# measure_board.net
KiCad netlist of a schematic drawn in EAGLE
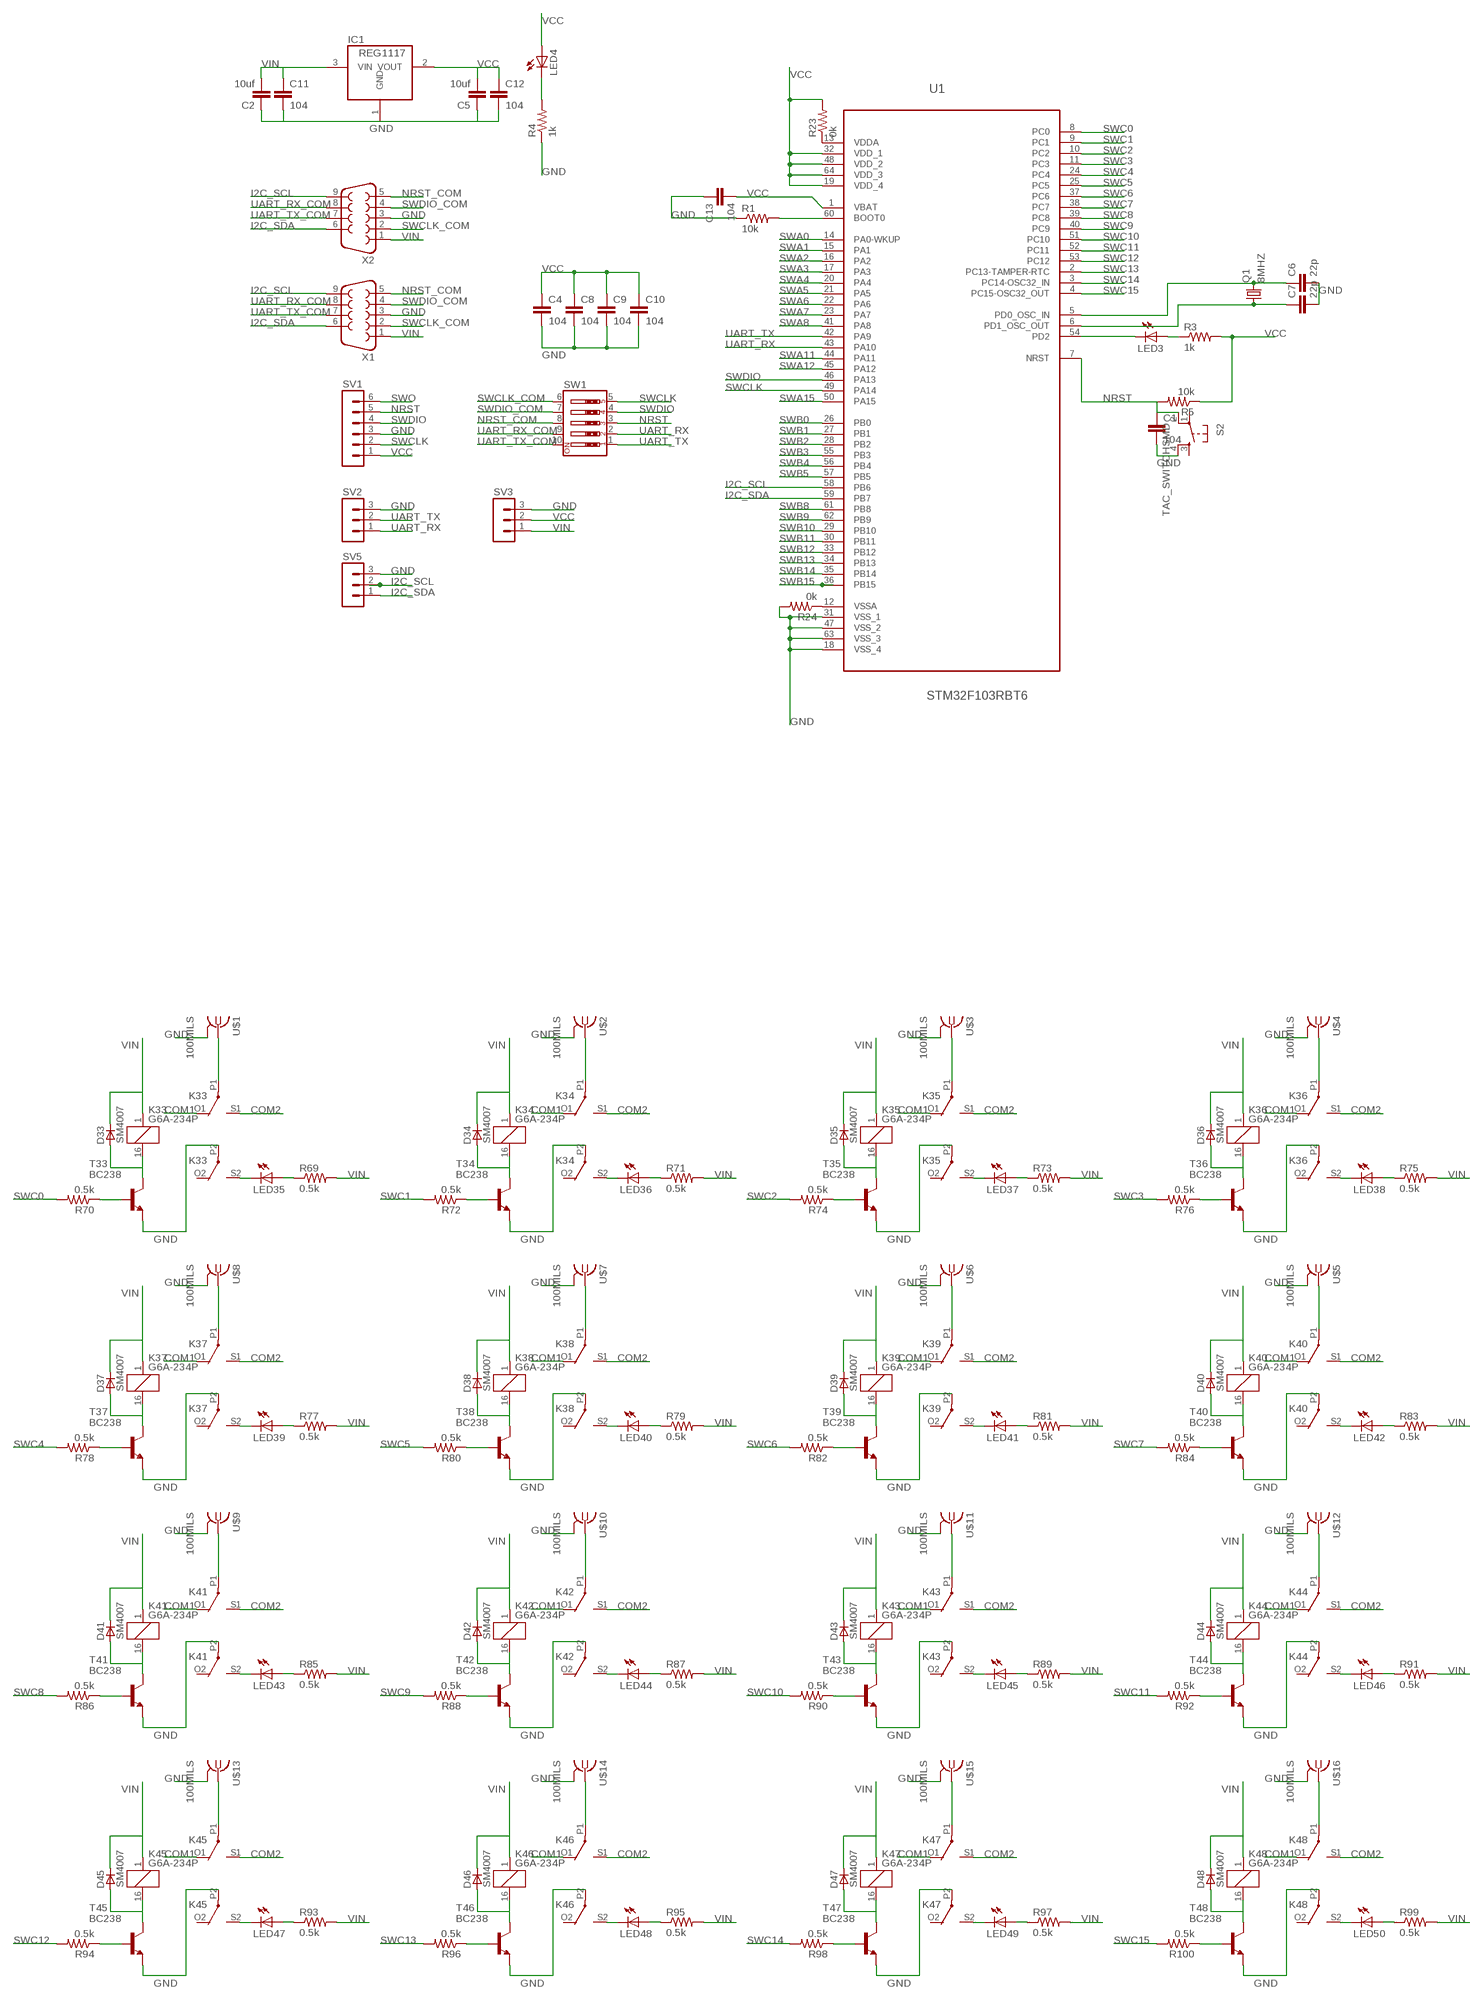
[diagram p0: schematic, sheet 1, part 1 of 2]
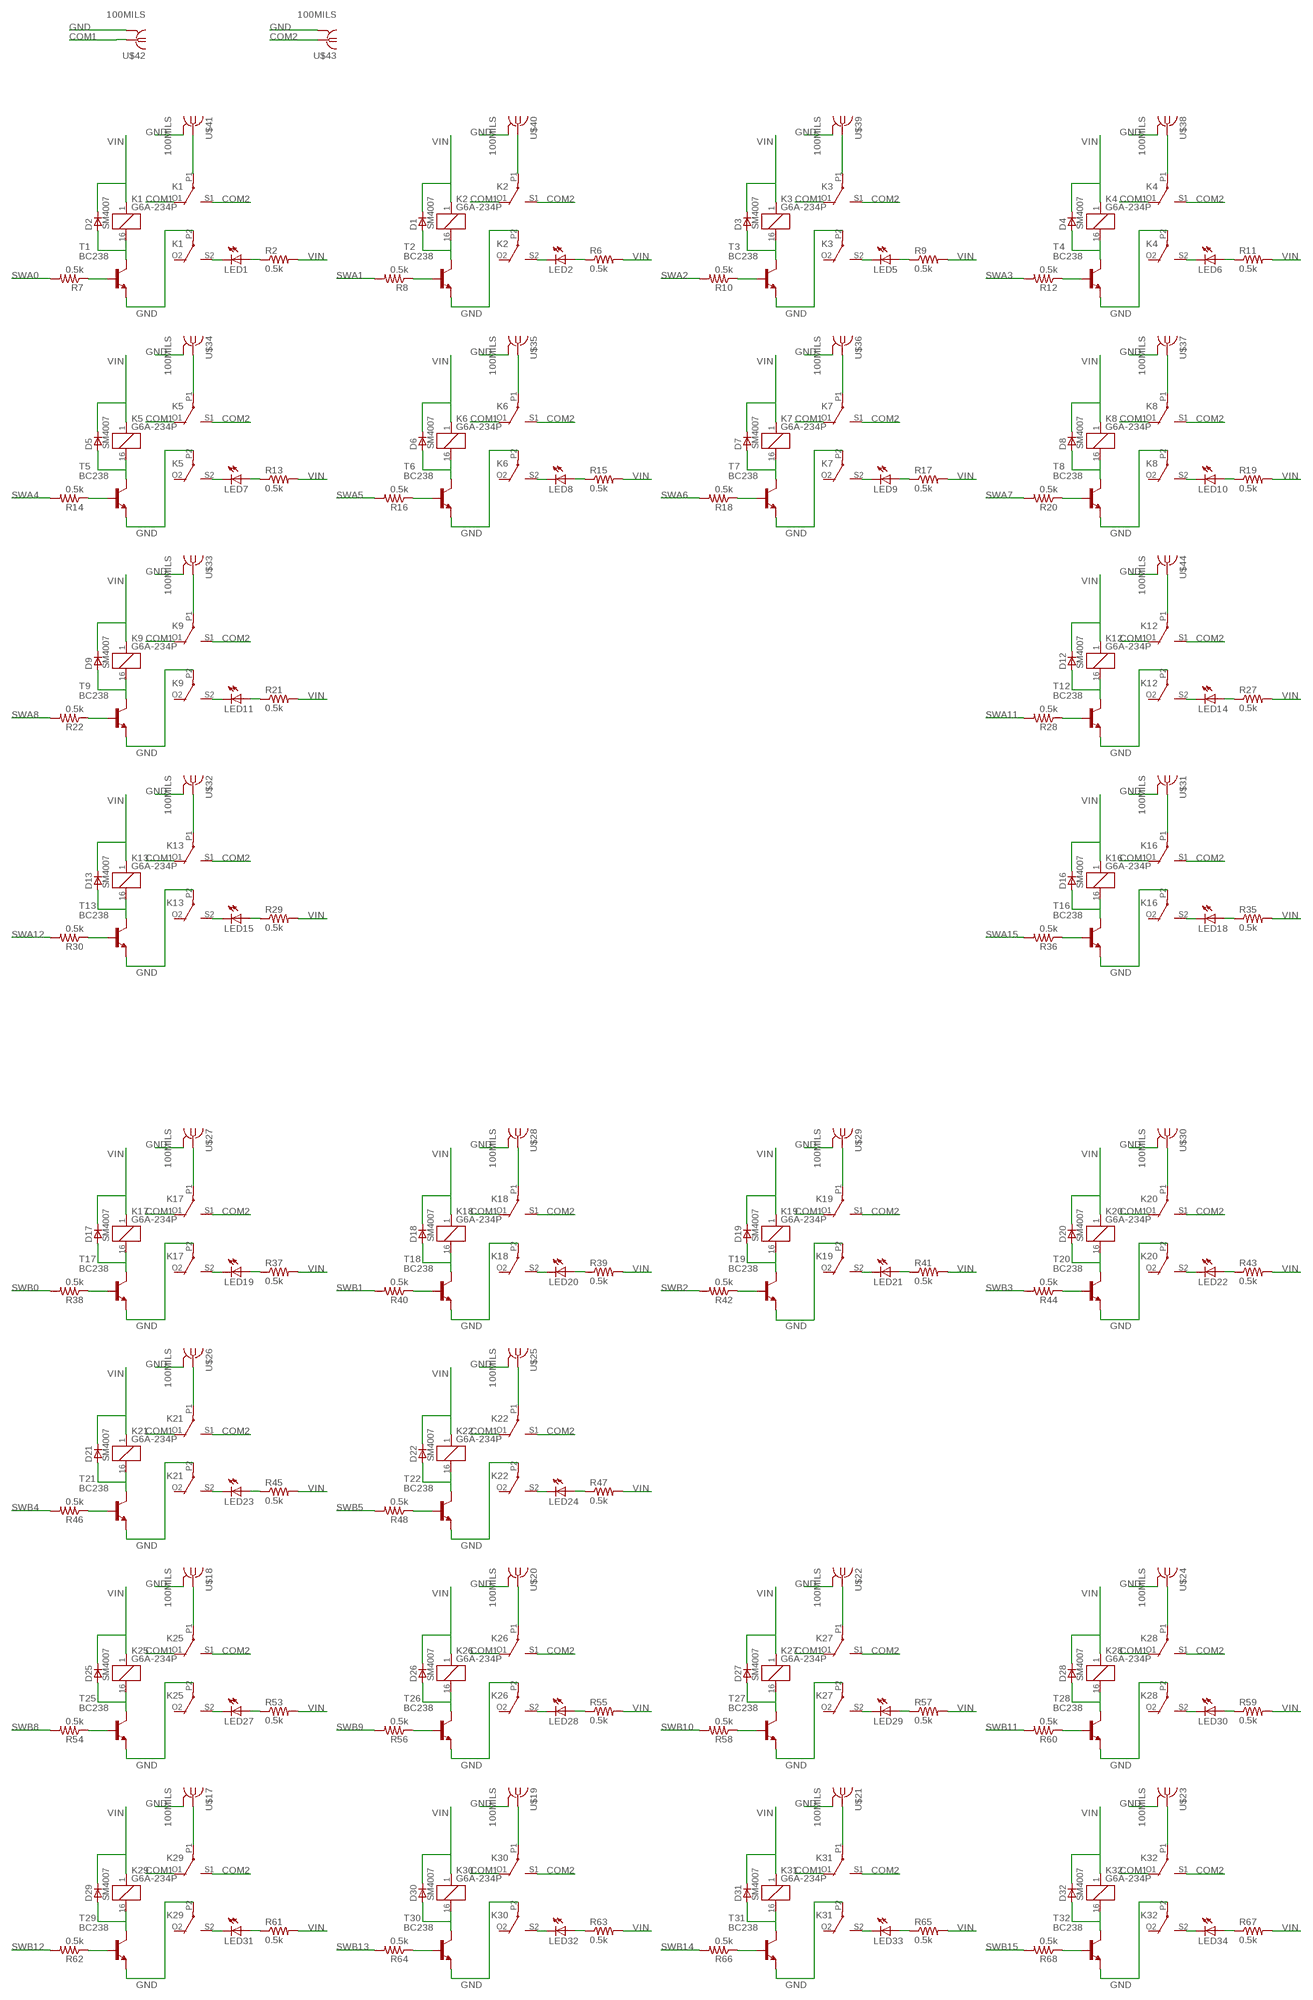
[diagram p1: schematic, sheet 1, part 2 of 2]

(export (version "E")
  (design (tool "Eeschema 10.0.6"))
  (components
    (comp (ref "C1")
      (value "104")
      (footprint "eagle-import:C0805")
      (libsource (lib "eagle-import") (part "resistor_C-EUC0805"))
    )
    (comp (ref "C2")
      (value "10uf")
      (footprint "eagle-import:C1206")
      (libsource (lib "eagle-import") (part "C-EUC1206"))
    )
    (comp (ref "C4")
      (value "104")
      (footprint "eagle-import:C0805")
      (libsource (lib "eagle-import") (part "resistor_C-EUC0805"))
    )
    (comp (ref "C5")
      (value "10uf")
      (footprint "eagle-import:C1206")
      (libsource (lib "eagle-import") (part "C-EUC1206"))
    )
    (comp (ref "C6")
      (value "22p")
      (footprint "eagle-import:C0805")
      (libsource (lib "eagle-import") (part "resistor_C-EUC0805"))
    )
    (comp (ref "C7")
      (value "22p")
      (footprint "eagle-import:C0805")
      (libsource (lib "eagle-import") (part "resistor_C-EUC0805"))
    )
    (comp (ref "C8")
      (value "104")
      (footprint "eagle-import:C0805")
      (libsource (lib "eagle-import") (part "resistor_C-EUC0805"))
    )
    (comp (ref "C9")
      (value "104")
      (footprint "eagle-import:C0805")
      (libsource (lib "eagle-import") (part "resistor_C-EUC0805"))
    )
    (comp (ref "C10")
      (value "104")
      (footprint "eagle-import:C0805")
      (libsource (lib "eagle-import") (part "resistor_C-EUC0805"))
    )
    (comp (ref "C11")
      (value "104")
      (footprint "eagle-import:C0805")
      (libsource (lib "eagle-import") (part "resistor_C-EUC0805"))
    )
    (comp (ref "C12")
      (value "104")
      (footprint "eagle-import:C0805")
      (libsource (lib "eagle-import") (part "resistor_C-EUC0805"))
    )
    (comp (ref "C13")
      (value "104")
      (footprint "eagle-import:C0805")
      (libsource (lib "eagle-import") (part "resistor_C-EUC0805"))
    )
    (comp (ref "D1")
      (value "SM4007")
      (footprint "eagle-import:MELF-MLL41_DO213AB")
      (libsource (lib "eagle-import") (part "SM4007"))
    )
    (comp (ref "D2")
      (value "SM4007")
      (footprint "eagle-import:MELF-MLL41_DO213AB")
      (libsource (lib "eagle-import") (part "SM4007"))
    )
    (comp (ref "D3")
      (value "SM4007")
      (footprint "eagle-import:MELF-MLL41_DO213AB")
      (libsource (lib "eagle-import") (part "SM4007"))
    )
    (comp (ref "D4")
      (value "SM4007")
      (footprint "eagle-import:MELF-MLL41_DO213AB")
      (libsource (lib "eagle-import") (part "SM4007"))
    )
    (comp (ref "D5")
      (value "SM4007")
      (footprint "eagle-import:MELF-MLL41_DO213AB")
      (libsource (lib "eagle-import") (part "SM4007"))
    )
    (comp (ref "D6")
      (value "SM4007")
      (footprint "eagle-import:MELF-MLL41_DO213AB")
      (libsource (lib "eagle-import") (part "SM4007"))
    )
    (comp (ref "D7")
      (value "SM4007")
      (footprint "eagle-import:MELF-MLL41_DO213AB")
      (libsource (lib "eagle-import") (part "SM4007"))
    )
    (comp (ref "D8")
      (value "SM4007")
      (footprint "eagle-import:MELF-MLL41_DO213AB")
      (libsource (lib "eagle-import") (part "SM4007"))
    )
    (comp (ref "D9")
      (value "SM4007")
      (footprint "eagle-import:MELF-MLL41_DO213AB")
      (libsource (lib "eagle-import") (part "SM4007"))
    )
    (comp (ref "D12")
      (value "SM4007")
      (footprint "eagle-import:MELF-MLL41_DO213AB")
      (libsource (lib "eagle-import") (part "SM4007"))
    )
    (comp (ref "D13")
      (value "SM4007")
      (footprint "eagle-import:MELF-MLL41_DO213AB")
      (libsource (lib "eagle-import") (part "SM4007"))
    )
    (comp (ref "D16")
      (value "SM4007")
      (footprint "eagle-import:MELF-MLL41_DO213AB")
      (libsource (lib "eagle-import") (part "SM4007"))
    )
    (comp (ref "D17")
      (value "SM4007")
      (footprint "eagle-import:MELF-MLL41_DO213AB")
      (libsource (lib "eagle-import") (part "SM4007"))
    )
    (comp (ref "D18")
      (value "SM4007")
      (footprint "eagle-import:MELF-MLL41_DO213AB")
      (libsource (lib "eagle-import") (part "SM4007"))
    )
    (comp (ref "D19")
      (value "SM4007")
      (footprint "eagle-import:MELF-MLL41_DO213AB")
      (libsource (lib "eagle-import") (part "SM4007"))
    )
    (comp (ref "D20")
      (value "SM4007")
      (footprint "eagle-import:MELF-MLL41_DO213AB")
      (libsource (lib "eagle-import") (part "SM4007"))
    )
    (comp (ref "D21")
      (value "SM4007")
      (footprint "eagle-import:MELF-MLL41_DO213AB")
      (libsource (lib "eagle-import") (part "SM4007"))
    )
    (comp (ref "D22")
      (value "SM4007")
      (footprint "eagle-import:MELF-MLL41_DO213AB")
      (libsource (lib "eagle-import") (part "SM4007"))
    )
    (comp (ref "D25")
      (value "SM4007")
      (footprint "eagle-import:MELF-MLL41_DO213AB")
      (libsource (lib "eagle-import") (part "SM4007"))
    )
    (comp (ref "D26")
      (value "SM4007")
      (footprint "eagle-import:MELF-MLL41_DO213AB")
      (libsource (lib "eagle-import") (part "SM4007"))
    )
    (comp (ref "D27")
      (value "SM4007")
      (footprint "eagle-import:MELF-MLL41_DO213AB")
      (libsource (lib "eagle-import") (part "SM4007"))
    )
    (comp (ref "D28")
      (value "SM4007")
      (footprint "eagle-import:MELF-MLL41_DO213AB")
      (libsource (lib "eagle-import") (part "SM4007"))
    )
    (comp (ref "D29")
      (value "SM4007")
      (footprint "eagle-import:MELF-MLL41_DO213AB")
      (libsource (lib "eagle-import") (part "SM4007"))
    )
    (comp (ref "D30")
      (value "SM4007")
      (footprint "eagle-import:MELF-MLL41_DO213AB")
      (libsource (lib "eagle-import") (part "SM4007"))
    )
    (comp (ref "D31")
      (value "SM4007")
      (footprint "eagle-import:MELF-MLL41_DO213AB")
      (libsource (lib "eagle-import") (part "SM4007"))
    )
    (comp (ref "D32")
      (value "SM4007")
      (footprint "eagle-import:MELF-MLL41_DO213AB")
      (libsource (lib "eagle-import") (part "SM4007"))
    )
    (comp (ref "D33")
      (value "SM4007")
      (footprint "eagle-import:MELF-MLL41_DO213AB")
      (libsource (lib "eagle-import") (part "SM4007"))
    )
    (comp (ref "D34")
      (value "SM4007")
      (footprint "eagle-import:MELF-MLL41_DO213AB")
      (libsource (lib "eagle-import") (part "SM4007"))
    )
    (comp (ref "D35")
      (value "SM4007")
      (footprint "eagle-import:MELF-MLL41_DO213AB")
      (libsource (lib "eagle-import") (part "SM4007"))
    )
    (comp (ref "D36")
      (value "SM4007")
      (footprint "eagle-import:MELF-MLL41_DO213AB")
      (libsource (lib "eagle-import") (part "SM4007"))
    )
    (comp (ref "D37")
      (value "SM4007")
      (footprint "eagle-import:MELF-MLL41_DO213AB")
      (libsource (lib "eagle-import") (part "SM4007"))
    )
    (comp (ref "D38")
      (value "SM4007")
      (footprint "eagle-import:MELF-MLL41_DO213AB")
      (libsource (lib "eagle-import") (part "SM4007"))
    )
    (comp (ref "D39")
      (value "SM4007")
      (footprint "eagle-import:MELF-MLL41_DO213AB")
      (libsource (lib "eagle-import") (part "SM4007"))
    )
    (comp (ref "D40")
      (value "SM4007")
      (footprint "eagle-import:MELF-MLL41_DO213AB")
      (libsource (lib "eagle-import") (part "SM4007"))
    )
    (comp (ref "D41")
      (value "SM4007")
      (footprint "eagle-import:MELF-MLL41_DO213AB")
      (libsource (lib "eagle-import") (part "SM4007"))
    )
    (comp (ref "D42")
      (value "SM4007")
      (footprint "eagle-import:MELF-MLL41_DO213AB")
      (libsource (lib "eagle-import") (part "SM4007"))
    )
    (comp (ref "D43")
      (value "SM4007")
      (footprint "eagle-import:MELF-MLL41_DO213AB")
      (libsource (lib "eagle-import") (part "SM4007"))
    )
    (comp (ref "D44")
      (value "SM4007")
      (footprint "eagle-import:MELF-MLL41_DO213AB")
      (libsource (lib "eagle-import") (part "SM4007"))
    )
    (comp (ref "D45")
      (value "SM4007")
      (footprint "eagle-import:MELF-MLL41_DO213AB")
      (libsource (lib "eagle-import") (part "SM4007"))
    )
    (comp (ref "D46")
      (value "SM4007")
      (footprint "eagle-import:MELF-MLL41_DO213AB")
      (libsource (lib "eagle-import") (part "SM4007"))
    )
    (comp (ref "D47")
      (value "SM4007")
      (footprint "eagle-import:MELF-MLL41_DO213AB")
      (libsource (lib "eagle-import") (part "SM4007"))
    )
    (comp (ref "D48")
      (value "SM4007")
      (footprint "eagle-import:MELF-MLL41_DO213AB")
      (libsource (lib "eagle-import") (part "SM4007"))
    )
    (comp (ref "IC1")
      (value "REG1117")
      (footprint "eagle-import:SOT223")
      (libsource (lib "eagle-import") (part "REG1117"))
    )
    (comp (ref "K1")
      (value "G6A-234P")
      (footprint "eagle-import:G6A-234P")
      (libsource (lib "eagle-import") (part "G6A-234P"))
    )
    (comp (ref "K2")
      (value "G6A-234P")
      (footprint "eagle-import:G6A-234P")
      (libsource (lib "eagle-import") (part "G6A-234P"))
    )
    (comp (ref "K3")
      (value "G6A-234P")
      (footprint "eagle-import:G6A-234P")
      (libsource (lib "eagle-import") (part "G6A-234P"))
    )
    (comp (ref "K4")
      (value "G6A-234P")
      (footprint "eagle-import:G6A-234P")
      (libsource (lib "eagle-import") (part "G6A-234P"))
    )
    (comp (ref "K5")
      (value "G6A-234P")
      (footprint "eagle-import:G6A-234P")
      (libsource (lib "eagle-import") (part "G6A-234P"))
    )
    (comp (ref "K6")
      (value "G6A-234P")
      (footprint "eagle-import:G6A-234P")
      (libsource (lib "eagle-import") (part "G6A-234P"))
    )
    (comp (ref "K7")
      (value "G6A-234P")
      (footprint "eagle-import:G6A-234P")
      (libsource (lib "eagle-import") (part "G6A-234P"))
    )
    (comp (ref "K8")
      (value "G6A-234P")
      (footprint "eagle-import:G6A-234P")
      (libsource (lib "eagle-import") (part "G6A-234P"))
    )
    (comp (ref "K9")
      (value "G6A-234P")
      (footprint "eagle-import:G6A-234P")
      (libsource (lib "eagle-import") (part "G6A-234P"))
    )
    (comp (ref "K12")
      (value "G6A-234P")
      (footprint "eagle-import:G6A-234P")
      (libsource (lib "eagle-import") (part "G6A-234P"))
    )
    (comp (ref "K13")
      (value "G6A-234P")
      (footprint "eagle-import:G6A-234P")
      (libsource (lib "eagle-import") (part "G6A-234P"))
    )
    (comp (ref "K16")
      (value "G6A-234P")
      (footprint "eagle-import:G6A-234P")
      (libsource (lib "eagle-import") (part "G6A-234P"))
    )
    (comp (ref "K17")
      (value "G6A-234P")
      (footprint "eagle-import:G6A-234P")
      (libsource (lib "eagle-import") (part "G6A-234P"))
    )
    (comp (ref "K18")
      (value "G6A-234P")
      (footprint "eagle-import:G6A-234P")
      (libsource (lib "eagle-import") (part "G6A-234P"))
    )
    (comp (ref "K19")
      (value "G6A-234P")
      (footprint "eagle-import:G6A-234P")
      (libsource (lib "eagle-import") (part "G6A-234P"))
    )
    (comp (ref "K20")
      (value "G6A-234P")
      (footprint "eagle-import:G6A-234P")
      (libsource (lib "eagle-import") (part "G6A-234P"))
    )
    (comp (ref "K21")
      (value "G6A-234P")
      (footprint "eagle-import:G6A-234P")
      (libsource (lib "eagle-import") (part "G6A-234P"))
    )
    (comp (ref "K22")
      (value "G6A-234P")
      (footprint "eagle-import:G6A-234P")
      (libsource (lib "eagle-import") (part "G6A-234P"))
    )
    (comp (ref "K25")
      (value "G6A-234P")
      (footprint "eagle-import:G6A-234P")
      (libsource (lib "eagle-import") (part "G6A-234P"))
    )
    (comp (ref "K26")
      (value "G6A-234P")
      (footprint "eagle-import:G6A-234P")
      (libsource (lib "eagle-import") (part "G6A-234P"))
    )
    (comp (ref "K27")
      (value "G6A-234P")
      (footprint "eagle-import:G6A-234P")
      (libsource (lib "eagle-import") (part "G6A-234P"))
    )
    (comp (ref "K28")
      (value "G6A-234P")
      (footprint "eagle-import:G6A-234P")
      (libsource (lib "eagle-import") (part "G6A-234P"))
    )
    (comp (ref "K29")
      (value "G6A-234P")
      (footprint "eagle-import:G6A-234P")
      (libsource (lib "eagle-import") (part "G6A-234P"))
    )
    (comp (ref "K30")
      (value "G6A-234P")
      (footprint "eagle-import:G6A-234P")
      (libsource (lib "eagle-import") (part "G6A-234P"))
    )
    (comp (ref "K31")
      (value "G6A-234P")
      (footprint "eagle-import:G6A-234P")
      (libsource (lib "eagle-import") (part "G6A-234P"))
    )
    (comp (ref "K32")
      (value "G6A-234P")
      (footprint "eagle-import:G6A-234P")
      (libsource (lib "eagle-import") (part "G6A-234P"))
    )
    (comp (ref "K33")
      (value "G6A-234P")
      (footprint "eagle-import:G6A-234P")
      (libsource (lib "eagle-import") (part "G6A-234P"))
    )
    (comp (ref "K34")
      (value "G6A-234P")
      (footprint "eagle-import:G6A-234P")
      (libsource (lib "eagle-import") (part "G6A-234P"))
    )
    (comp (ref "K35")
      (value "G6A-234P")
      (footprint "eagle-import:G6A-234P")
      (libsource (lib "eagle-import") (part "G6A-234P"))
    )
    (comp (ref "K36")
      (value "G6A-234P")
      (footprint "eagle-import:G6A-234P")
      (libsource (lib "eagle-import") (part "G6A-234P"))
    )
    (comp (ref "K37")
      (value "G6A-234P")
      (footprint "eagle-import:G6A-234P")
      (libsource (lib "eagle-import") (part "G6A-234P"))
    )
    (comp (ref "K38")
      (value "G6A-234P")
      (footprint "eagle-import:G6A-234P")
      (libsource (lib "eagle-import") (part "G6A-234P"))
    )
    (comp (ref "K39")
      (value "G6A-234P")
      (footprint "eagle-import:G6A-234P")
      (libsource (lib "eagle-import") (part "G6A-234P"))
    )
    (comp (ref "K40")
      (value "G6A-234P")
      (footprint "eagle-import:G6A-234P")
      (libsource (lib "eagle-import") (part "G6A-234P"))
    )
    (comp (ref "K41")
      (value "G6A-234P")
      (footprint "eagle-import:G6A-234P")
      (libsource (lib "eagle-import") (part "G6A-234P"))
    )
    (comp (ref "K42")
      (value "G6A-234P")
      (footprint "eagle-import:G6A-234P")
      (libsource (lib "eagle-import") (part "G6A-234P"))
    )
    (comp (ref "K43")
      (value "G6A-234P")
      (footprint "eagle-import:G6A-234P")
      (libsource (lib "eagle-import") (part "G6A-234P"))
    )
    (comp (ref "K44")
      (value "G6A-234P")
      (footprint "eagle-import:G6A-234P")
      (libsource (lib "eagle-import") (part "G6A-234P"))
    )
    (comp (ref "K45")
      (value "G6A-234P")
      (footprint "eagle-import:G6A-234P")
      (libsource (lib "eagle-import") (part "G6A-234P"))
    )
    (comp (ref "K46")
      (value "G6A-234P")
      (footprint "eagle-import:G6A-234P")
      (libsource (lib "eagle-import") (part "G6A-234P"))
    )
    (comp (ref "K47")
      (value "G6A-234P")
      (footprint "eagle-import:G6A-234P")
      (libsource (lib "eagle-import") (part "G6A-234P"))
    )
    (comp (ref "K48")
      (value "G6A-234P")
      (footprint "eagle-import:G6A-234P")
      (libsource (lib "eagle-import") (part "G6A-234P"))
    )
    (comp (ref "LED1")
      (value "LED3MM")
      (footprint "eagle-import:LED3MM")
      (libsource (lib "eagle-import") (part "LED3MM"))
    )
    (comp (ref "LED2")
      (value "LED3MM")
      (footprint "eagle-import:LED3MM")
      (libsource (lib "eagle-import") (part "LED3MM"))
    )
    (comp (ref "LED3")
      (value "LEDSML0805")
      (footprint "eagle-import:SML0805")
      (libsource (lib "eagle-import") (part "LEDSML0805"))
    )
    (comp (ref "LED4")
      (value "LEDSML0805")
      (footprint "eagle-import:SML0805")
      (libsource (lib "eagle-import") (part "LEDSML0805"))
    )
    (comp (ref "LED5")
      (value "LED3MM")
      (footprint "eagle-import:LED3MM")
      (libsource (lib "eagle-import") (part "LED3MM"))
    )
    (comp (ref "LED6")
      (value "LED3MM")
      (footprint "eagle-import:LED3MM")
      (libsource (lib "eagle-import") (part "LED3MM"))
    )
    (comp (ref "LED7")
      (value "LED3MM")
      (footprint "eagle-import:LED3MM")
      (libsource (lib "eagle-import") (part "LED3MM"))
    )
    (comp (ref "LED8")
      (value "LED3MM")
      (footprint "eagle-import:LED3MM")
      (libsource (lib "eagle-import") (part "LED3MM"))
    )
    (comp (ref "LED9")
      (value "LED3MM")
      (footprint "eagle-import:LED3MM")
      (libsource (lib "eagle-import") (part "LED3MM"))
    )
    (comp (ref "LED10")
      (value "LED3MM")
      (footprint "eagle-import:LED3MM")
      (libsource (lib "eagle-import") (part "LED3MM"))
    )
    (comp (ref "LED11")
      (value "LED3MM")
      (footprint "eagle-import:LED3MM")
      (libsource (lib "eagle-import") (part "LED3MM"))
    )
    (comp (ref "LED14")
      (value "LED3MM")
      (footprint "eagle-import:LED3MM")
      (libsource (lib "eagle-import") (part "LED3MM"))
    )
    (comp (ref "LED15")
      (value "LED3MM")
      (footprint "eagle-import:LED3MM")
      (libsource (lib "eagle-import") (part "LED3MM"))
    )
    (comp (ref "LED18")
      (value "LED3MM")
      (footprint "eagle-import:LED3MM")
      (libsource (lib "eagle-import") (part "LED3MM"))
    )
    (comp (ref "LED19")
      (value "LED3MM")
      (footprint "eagle-import:LED3MM")
      (libsource (lib "eagle-import") (part "LED3MM"))
    )
    (comp (ref "LED20")
      (value "LED3MM")
      (footprint "eagle-import:LED3MM")
      (libsource (lib "eagle-import") (part "LED3MM"))
    )
    (comp (ref "LED21")
      (value "LED3MM")
      (footprint "eagle-import:LED3MM")
      (libsource (lib "eagle-import") (part "LED3MM"))
    )
    (comp (ref "LED22")
      (value "LED3MM")
      (footprint "eagle-import:LED3MM")
      (libsource (lib "eagle-import") (part "LED3MM"))
    )
    (comp (ref "LED23")
      (value "LED3MM")
      (footprint "eagle-import:LED3MM")
      (libsource (lib "eagle-import") (part "LED3MM"))
    )
    (comp (ref "LED24")
      (value "LED3MM")
      (footprint "eagle-import:LED3MM")
      (libsource (lib "eagle-import") (part "LED3MM"))
    )
    (comp (ref "LED27")
      (value "LED3MM")
      (footprint "eagle-import:LED3MM")
      (libsource (lib "eagle-import") (part "LED3MM"))
    )
    (comp (ref "LED28")
      (value "LED3MM")
      (footprint "eagle-import:LED3MM")
      (libsource (lib "eagle-import") (part "LED3MM"))
    )
    (comp (ref "LED29")
      (value "LED3MM")
      (footprint "eagle-import:LED3MM")
      (libsource (lib "eagle-import") (part "LED3MM"))
    )
    (comp (ref "LED30")
      (value "LED3MM")
      (footprint "eagle-import:LED3MM")
      (libsource (lib "eagle-import") (part "LED3MM"))
    )
    (comp (ref "LED31")
      (value "LED3MM")
      (footprint "eagle-import:LED3MM")
      (libsource (lib "eagle-import") (part "LED3MM"))
    )
    (comp (ref "LED32")
      (value "LED3MM")
      (footprint "eagle-import:LED3MM")
      (libsource (lib "eagle-import") (part "LED3MM"))
    )
    (comp (ref "LED33")
      (value "LED3MM")
      (footprint "eagle-import:LED3MM")
      (libsource (lib "eagle-import") (part "LED3MM"))
    )
    (comp (ref "LED34")
      (value "LED3MM")
      (footprint "eagle-import:LED3MM")
      (libsource (lib "eagle-import") (part "LED3MM"))
    )
    (comp (ref "LED35")
      (value "LED3MM")
      (footprint "eagle-import:LED3MM")
      (libsource (lib "eagle-import") (part "LED3MM"))
    )
    (comp (ref "LED36")
      (value "LED3MM")
      (footprint "eagle-import:LED3MM")
      (libsource (lib "eagle-import") (part "LED3MM"))
    )
    (comp (ref "LED37")
      (value "LED3MM")
      (footprint "eagle-import:LED3MM")
      (libsource (lib "eagle-import") (part "LED3MM"))
    )
    (comp (ref "LED38")
      (value "LED3MM")
      (footprint "eagle-import:LED3MM")
      (libsource (lib "eagle-import") (part "LED3MM"))
    )
    (comp (ref "LED39")
      (value "LED3MM")
      (footprint "eagle-import:LED3MM")
      (libsource (lib "eagle-import") (part "LED3MM"))
    )
    (comp (ref "LED40")
      (value "LED3MM")
      (footprint "eagle-import:LED3MM")
      (libsource (lib "eagle-import") (part "LED3MM"))
    )
    (comp (ref "LED41")
      (value "LED3MM")
      (footprint "eagle-import:LED3MM")
      (libsource (lib "eagle-import") (part "LED3MM"))
    )
    (comp (ref "LED42")
      (value "LED3MM")
      (footprint "eagle-import:LED3MM")
      (libsource (lib "eagle-import") (part "LED3MM"))
    )
    (comp (ref "LED43")
      (value "LED3MM")
      (footprint "eagle-import:LED3MM")
      (libsource (lib "eagle-import") (part "LED3MM"))
    )
    (comp (ref "LED44")
      (value "LED3MM")
      (footprint "eagle-import:LED3MM")
      (libsource (lib "eagle-import") (part "LED3MM"))
    )
    (comp (ref "LED45")
      (value "LED3MM")
      (footprint "eagle-import:LED3MM")
      (libsource (lib "eagle-import") (part "LED3MM"))
    )
    (comp (ref "LED46")
      (value "LED3MM")
      (footprint "eagle-import:LED3MM")
      (libsource (lib "eagle-import") (part "LED3MM"))
    )
    (comp (ref "LED47")
      (value "LED3MM")
      (footprint "eagle-import:LED3MM")
      (libsource (lib "eagle-import") (part "LED3MM"))
    )
    (comp (ref "LED48")
      (value "LED3MM")
      (footprint "eagle-import:LED3MM")
      (libsource (lib "eagle-import") (part "LED3MM"))
    )
    (comp (ref "LED49")
      (value "LED3MM")
      (footprint "eagle-import:LED3MM")
      (libsource (lib "eagle-import") (part "LED3MM"))
    )
    (comp (ref "LED50")
      (value "LED3MM")
      (footprint "eagle-import:LED3MM")
      (libsource (lib "eagle-import") (part "LED3MM"))
    )
    (comp (ref "Q1")
      (value "8MHZ")
      (footprint "eagle-import:HC49U70")
      (libsource (lib "eagle-import") (part "CRYSTALHC49U70"))
    )
    (comp (ref "R1")
      (value "10k")
      (footprint "eagle-import:M0805")
      (libsource (lib "eagle-import") (part "R-US_M0805"))
    )
    (comp (ref "R2")
      (value "0.5k")
      (footprint "eagle-import:M0805")
      (libsource (lib "eagle-import") (part "R-US_M0805"))
    )
    (comp (ref "R3")
      (value "1k")
      (footprint "eagle-import:M0805")
      (libsource (lib "eagle-import") (part "R-US_M0805"))
    )
    (comp (ref "R4")
      (value "1k")
      (footprint "eagle-import:M0805")
      (libsource (lib "eagle-import") (part "R-US_M0805"))
    )
    (comp (ref "R5")
      (value "10k")
      (footprint "eagle-import:M0805")
      (libsource (lib "eagle-import") (part "R-US_M0805"))
    )
    (comp (ref "R6")
      (value "0.5k")
      (footprint "eagle-import:M0805")
      (libsource (lib "eagle-import") (part "R-US_M0805"))
    )
    (comp (ref "R7")
      (value "0.5k")
      (footprint "eagle-import:M0805")
      (libsource (lib "eagle-import") (part "R-US_M0805"))
    )
    (comp (ref "R8")
      (value "0.5k")
      (footprint "eagle-import:M0805")
      (libsource (lib "eagle-import") (part "R-US_M0805"))
    )
    (comp (ref "R9")
      (value "0.5k")
      (footprint "eagle-import:M0805")
      (libsource (lib "eagle-import") (part "R-US_M0805"))
    )
    (comp (ref "R10")
      (value "0.5k")
      (footprint "eagle-import:M0805")
      (libsource (lib "eagle-import") (part "R-US_M0805"))
    )
    (comp (ref "R11")
      (value "0.5k")
      (footprint "eagle-import:M0805")
      (libsource (lib "eagle-import") (part "R-US_M0805"))
    )
    (comp (ref "R12")
      (value "0.5k")
      (footprint "eagle-import:M0805")
      (libsource (lib "eagle-import") (part "R-US_M0805"))
    )
    (comp (ref "R13")
      (value "0.5k")
      (footprint "eagle-import:M0805")
      (libsource (lib "eagle-import") (part "R-US_M0805"))
    )
    (comp (ref "R14")
      (value "0.5k")
      (footprint "eagle-import:M0805")
      (libsource (lib "eagle-import") (part "R-US_M0805"))
    )
    (comp (ref "R15")
      (value "0.5k")
      (footprint "eagle-import:M0805")
      (libsource (lib "eagle-import") (part "R-US_M0805"))
    )
    (comp (ref "R16")
      (value "0.5k")
      (footprint "eagle-import:M0805")
      (libsource (lib "eagle-import") (part "R-US_M0805"))
    )
    (comp (ref "R17")
      (value "0.5k")
      (footprint "eagle-import:M0805")
      (libsource (lib "eagle-import") (part "R-US_M0805"))
    )
    (comp (ref "R18")
      (value "0.5k")
      (footprint "eagle-import:M0805")
      (libsource (lib "eagle-import") (part "R-US_M0805"))
    )
    (comp (ref "R19")
      (value "0.5k")
      (footprint "eagle-import:M0805")
      (libsource (lib "eagle-import") (part "R-US_M0805"))
    )
    (comp (ref "R20")
      (value "0.5k")
      (footprint "eagle-import:M0805")
      (libsource (lib "eagle-import") (part "R-US_M0805"))
    )
    (comp (ref "R21")
      (value "0.5k")
      (footprint "eagle-import:M0805")
      (libsource (lib "eagle-import") (part "R-US_M0805"))
    )
    (comp (ref "R22")
      (value "0.5k")
      (footprint "eagle-import:M0805")
      (libsource (lib "eagle-import") (part "R-US_M0805"))
    )
    (comp (ref "R23")
      (value "0k")
      (footprint "eagle-import:M0805")
      (libsource (lib "eagle-import") (part "R-US_M0805"))
    )
    (comp (ref "R24")
      (value "0k")
      (footprint "eagle-import:M0805")
      (libsource (lib "eagle-import") (part "R-US_M0805"))
    )
    (comp (ref "R27")
      (value "0.5k")
      (footprint "eagle-import:M0805")
      (libsource (lib "eagle-import") (part "R-US_M0805"))
    )
    (comp (ref "R28")
      (value "0.5k")
      (footprint "eagle-import:M0805")
      (libsource (lib "eagle-import") (part "R-US_M0805"))
    )
    (comp (ref "R29")
      (value "0.5k")
      (footprint "eagle-import:M0805")
      (libsource (lib "eagle-import") (part "R-US_M0805"))
    )
    (comp (ref "R30")
      (value "0.5k")
      (footprint "eagle-import:M0805")
      (libsource (lib "eagle-import") (part "R-US_M0805"))
    )
    (comp (ref "R35")
      (value "0.5k")
      (footprint "eagle-import:M0805")
      (libsource (lib "eagle-import") (part "R-US_M0805"))
    )
    (comp (ref "R36")
      (value "0.5k")
      (footprint "eagle-import:M0805")
      (libsource (lib "eagle-import") (part "R-US_M0805"))
    )
    (comp (ref "R37")
      (value "0.5k")
      (footprint "eagle-import:M0805")
      (libsource (lib "eagle-import") (part "R-US_M0805"))
    )
    (comp (ref "R38")
      (value "0.5k")
      (footprint "eagle-import:M0805")
      (libsource (lib "eagle-import") (part "R-US_M0805"))
    )
    (comp (ref "R39")
      (value "0.5k")
      (footprint "eagle-import:M0805")
      (libsource (lib "eagle-import") (part "R-US_M0805"))
    )
    (comp (ref "R40")
      (value "0.5k")
      (footprint "eagle-import:M0805")
      (libsource (lib "eagle-import") (part "R-US_M0805"))
    )
    (comp (ref "R41")
      (value "0.5k")
      (footprint "eagle-import:M0805")
      (libsource (lib "eagle-import") (part "R-US_M0805"))
    )
    (comp (ref "R42")
      (value "0.5k")
      (footprint "eagle-import:M0805")
      (libsource (lib "eagle-import") (part "R-US_M0805"))
    )
    (comp (ref "R43")
      (value "0.5k")
      (footprint "eagle-import:M0805")
      (libsource (lib "eagle-import") (part "R-US_M0805"))
    )
    (comp (ref "R44")
      (value "0.5k")
      (footprint "eagle-import:M0805")
      (libsource (lib "eagle-import") (part "R-US_M0805"))
    )
    (comp (ref "R45")
      (value "0.5k")
      (footprint "eagle-import:M0805")
      (libsource (lib "eagle-import") (part "R-US_M0805"))
    )
    (comp (ref "R46")
      (value "0.5k")
      (footprint "eagle-import:M0805")
      (libsource (lib "eagle-import") (part "R-US_M0805"))
    )
    (comp (ref "R47")
      (value "0.5k")
      (footprint "eagle-import:M0805")
      (libsource (lib "eagle-import") (part "R-US_M0805"))
    )
    (comp (ref "R48")
      (value "0.5k")
      (footprint "eagle-import:M0805")
      (libsource (lib "eagle-import") (part "R-US_M0805"))
    )
    (comp (ref "R53")
      (value "0.5k")
      (footprint "eagle-import:M0805")
      (libsource (lib "eagle-import") (part "R-US_M0805"))
    )
    (comp (ref "R54")
      (value "0.5k")
      (footprint "eagle-import:M0805")
      (libsource (lib "eagle-import") (part "R-US_M0805"))
    )
    (comp (ref "R55")
      (value "0.5k")
      (footprint "eagle-import:M0805")
      (libsource (lib "eagle-import") (part "R-US_M0805"))
    )
    (comp (ref "R56")
      (value "0.5k")
      (footprint "eagle-import:M0805")
      (libsource (lib "eagle-import") (part "R-US_M0805"))
    )
    (comp (ref "R57")
      (value "0.5k")
      (footprint "eagle-import:M0805")
      (libsource (lib "eagle-import") (part "R-US_M0805"))
    )
    (comp (ref "R58")
      (value "0.5k")
      (footprint "eagle-import:M0805")
      (libsource (lib "eagle-import") (part "R-US_M0805"))
    )
    (comp (ref "R59")
      (value "0.5k")
      (footprint "eagle-import:M0805")
      (libsource (lib "eagle-import") (part "R-US_M0805"))
    )
    (comp (ref "R60")
      (value "0.5k")
      (footprint "eagle-import:M0805")
      (libsource (lib "eagle-import") (part "R-US_M0805"))
    )
    (comp (ref "R61")
      (value "0.5k")
      (footprint "eagle-import:M0805")
      (libsource (lib "eagle-import") (part "R-US_M0805"))
    )
    (comp (ref "R62")
      (value "0.5k")
      (footprint "eagle-import:M0805")
      (libsource (lib "eagle-import") (part "R-US_M0805"))
    )
    (comp (ref "R63")
      (value "0.5k")
      (footprint "eagle-import:M0805")
      (libsource (lib "eagle-import") (part "R-US_M0805"))
    )
    (comp (ref "R64")
      (value "0.5k")
      (footprint "eagle-import:M0805")
      (libsource (lib "eagle-import") (part "R-US_M0805"))
    )
    (comp (ref "R65")
      (value "0.5k")
      (footprint "eagle-import:M0805")
      (libsource (lib "eagle-import") (part "R-US_M0805"))
    )
    (comp (ref "R66")
      (value "0.5k")
      (footprint "eagle-import:M0805")
      (libsource (lib "eagle-import") (part "R-US_M0805"))
    )
    (comp (ref "R67")
      (value "0.5k")
      (footprint "eagle-import:M0805")
      (libsource (lib "eagle-import") (part "R-US_M0805"))
    )
    (comp (ref "R68")
      (value "0.5k")
      (footprint "eagle-import:M0805")
      (libsource (lib "eagle-import") (part "R-US_M0805"))
    )
    (comp (ref "R69")
      (value "0.5k")
      (footprint "eagle-import:M0805")
      (libsource (lib "eagle-import") (part "R-US_M0805"))
    )
    (comp (ref "R70")
      (value "0.5k")
      (footprint "eagle-import:M0805")
      (libsource (lib "eagle-import") (part "R-US_M0805"))
    )
    (comp (ref "R71")
      (value "0.5k")
      (footprint "eagle-import:M0805")
      (libsource (lib "eagle-import") (part "R-US_M0805"))
    )
    (comp (ref "R72")
      (value "0.5k")
      (footprint "eagle-import:M0805")
      (libsource (lib "eagle-import") (part "R-US_M0805"))
    )
    (comp (ref "R73")
      (value "0.5k")
      (footprint "eagle-import:M0805")
      (libsource (lib "eagle-import") (part "R-US_M0805"))
    )
    (comp (ref "R74")
      (value "0.5k")
      (footprint "eagle-import:M0805")
      (libsource (lib "eagle-import") (part "R-US_M0805"))
    )
    (comp (ref "R75")
      (value "0.5k")
      (footprint "eagle-import:M0805")
      (libsource (lib "eagle-import") (part "R-US_M0805"))
    )
    (comp (ref "R76")
      (value "0.5k")
      (footprint "eagle-import:M0805")
      (libsource (lib "eagle-import") (part "R-US_M0805"))
    )
    (comp (ref "R77")
      (value "0.5k")
      (footprint "eagle-import:M0805")
      (libsource (lib "eagle-import") (part "R-US_M0805"))
    )
    (comp (ref "R78")
      (value "0.5k")
      (footprint "eagle-import:M0805")
      (libsource (lib "eagle-import") (part "R-US_M0805"))
    )
    (comp (ref "R79")
      (value "0.5k")
      (footprint "eagle-import:M0805")
      (libsource (lib "eagle-import") (part "R-US_M0805"))
    )
    (comp (ref "R80")
      (value "0.5k")
      (footprint "eagle-import:M0805")
      (libsource (lib "eagle-import") (part "R-US_M0805"))
    )
    (comp (ref "R81")
      (value "0.5k")
      (footprint "eagle-import:M0805")
      (libsource (lib "eagle-import") (part "R-US_M0805"))
    )
    (comp (ref "R82")
      (value "0.5k")
      (footprint "eagle-import:M0805")
      (libsource (lib "eagle-import") (part "R-US_M0805"))
    )
    (comp (ref "R83")
      (value "0.5k")
      (footprint "eagle-import:M0805")
      (libsource (lib "eagle-import") (part "R-US_M0805"))
    )
    (comp (ref "R84")
      (value "0.5k")
      (footprint "eagle-import:M0805")
      (libsource (lib "eagle-import") (part "R-US_M0805"))
    )
    (comp (ref "R85")
      (value "0.5k")
      (footprint "eagle-import:M0805")
      (libsource (lib "eagle-import") (part "R-US_M0805"))
    )
    (comp (ref "R86")
      (value "0.5k")
      (footprint "eagle-import:M0805")
      (libsource (lib "eagle-import") (part "R-US_M0805"))
    )
    (comp (ref "R87")
      (value "0.5k")
      (footprint "eagle-import:M0805")
      (libsource (lib "eagle-import") (part "R-US_M0805"))
    )
    (comp (ref "R88")
      (value "0.5k")
      (footprint "eagle-import:M0805")
      (libsource (lib "eagle-import") (part "R-US_M0805"))
    )
    (comp (ref "R89")
      (value "0.5k")
      (footprint "eagle-import:M0805")
      (libsource (lib "eagle-import") (part "R-US_M0805"))
    )
    (comp (ref "R90")
      (value "0.5k")
      (footprint "eagle-import:M0805")
      (libsource (lib "eagle-import") (part "R-US_M0805"))
    )
    (comp (ref "R91")
      (value "0.5k")
      (footprint "eagle-import:M0805")
      (libsource (lib "eagle-import") (part "R-US_M0805"))
    )
    (comp (ref "R92")
      (value "0.5k")
      (footprint "eagle-import:M0805")
      (libsource (lib "eagle-import") (part "R-US_M0805"))
    )
    (comp (ref "R93")
      (value "0.5k")
      (footprint "eagle-import:M0805")
      (libsource (lib "eagle-import") (part "R-US_M0805"))
    )
    (comp (ref "R94")
      (value "0.5k")
      (footprint "eagle-import:M0805")
      (libsource (lib "eagle-import") (part "R-US_M0805"))
    )
    (comp (ref "R95")
      (value "0.5k")
      (footprint "eagle-import:M0805")
      (libsource (lib "eagle-import") (part "R-US_M0805"))
    )
    (comp (ref "R96")
      (value "0.5k")
      (footprint "eagle-import:M0805")
      (libsource (lib "eagle-import") (part "R-US_M0805"))
    )
    (comp (ref "R97")
      (value "0.5k")
      (footprint "eagle-import:M0805")
      (libsource (lib "eagle-import") (part "R-US_M0805"))
    )
    (comp (ref "R98")
      (value "0.5k")
      (footprint "eagle-import:M0805")
      (libsource (lib "eagle-import") (part "R-US_M0805"))
    )
    (comp (ref "R99")
      (value "0.5k")
      (footprint "eagle-import:M0805")
      (libsource (lib "eagle-import") (part "R-US_M0805"))
    )
    (comp (ref "R100")
      (value "0.5k")
      (footprint "eagle-import:M0805")
      (libsource (lib "eagle-import") (part "R-US_M0805"))
    )
    (comp (ref "S2")
      (value "TAC_SWITCHSMD")
      (footprint "eagle-import:TACTILE-SWITCH-SMD")
      (libsource (lib "eagle-import") (part "TAC_SWITCHSMD"))
    )
    (comp (ref "SV1")
      (value "MA06-1")
      (footprint "eagle-import:MA06-1")
      (libsource (lib "eagle-import") (part "MA06-1"))
    )
    (comp (ref "SV2")
      (value "MA03-1")
      (footprint "eagle-import:MA03-1")
      (libsource (lib "eagle-import") (part "MA03-1"))
    )
    (comp (ref "SV3")
      (value "MA03-1")
      (footprint "eagle-import:MA03-1")
      (libsource (lib "eagle-import") (part "MA03-1"))
    )
    (comp (ref "SV5")
      (value "MA03-1")
      (footprint "eagle-import:MA03-1")
      (libsource (lib "eagle-import") (part "MA03-1"))
    )
    (comp (ref "SW1")
      (value "SW_DIP-5")
      (footprint "eagle-import:EDG-05")
      (libsource (lib "eagle-import") (part "SW_DIP-5"))
    )
    (comp (ref "T1")
      (value "BC238")
      (footprint "eagle-import:TO92")
      (libsource (lib "eagle-import") (part "BC238"))
    )
    (comp (ref "T2")
      (value "BC238")
      (footprint "eagle-import:TO92")
      (libsource (lib "eagle-import") (part "BC238"))
    )
    (comp (ref "T3")
      (value "BC238")
      (footprint "eagle-import:TO92")
      (libsource (lib "eagle-import") (part "BC238"))
    )
    (comp (ref "T4")
      (value "BC238")
      (footprint "eagle-import:TO92")
      (libsource (lib "eagle-import") (part "BC238"))
    )
    (comp (ref "T5")
      (value "BC238")
      (footprint "eagle-import:TO92")
      (libsource (lib "eagle-import") (part "BC238"))
    )
    (comp (ref "T6")
      (value "BC238")
      (footprint "eagle-import:TO92")
      (libsource (lib "eagle-import") (part "BC238"))
    )
    (comp (ref "T7")
      (value "BC238")
      (footprint "eagle-import:TO92")
      (libsource (lib "eagle-import") (part "BC238"))
    )
    (comp (ref "T8")
      (value "BC238")
      (footprint "eagle-import:TO92")
      (libsource (lib "eagle-import") (part "BC238"))
    )
    (comp (ref "T9")
      (value "BC238")
      (footprint "eagle-import:TO92")
      (libsource (lib "eagle-import") (part "BC238"))
    )
    (comp (ref "T12")
      (value "BC238")
      (footprint "eagle-import:TO92")
      (libsource (lib "eagle-import") (part "BC238"))
    )
    (comp (ref "T13")
      (value "BC238")
      (footprint "eagle-import:TO92")
      (libsource (lib "eagle-import") (part "BC238"))
    )
    (comp (ref "T16")
      (value "BC238")
      (footprint "eagle-import:TO92")
      (libsource (lib "eagle-import") (part "BC238"))
    )
    (comp (ref "T17")
      (value "BC238")
      (footprint "eagle-import:TO92")
      (libsource (lib "eagle-import") (part "BC238"))
    )
    (comp (ref "T18")
      (value "BC238")
      (footprint "eagle-import:TO92")
      (libsource (lib "eagle-import") (part "BC238"))
    )
    (comp (ref "T19")
      (value "BC238")
      (footprint "eagle-import:TO92")
      (libsource (lib "eagle-import") (part "BC238"))
    )
    (comp (ref "T20")
      (value "BC238")
      (footprint "eagle-import:TO92")
      (libsource (lib "eagle-import") (part "BC238"))
    )
    (comp (ref "T21")
      (value "BC238")
      (footprint "eagle-import:TO92")
      (libsource (lib "eagle-import") (part "BC238"))
    )
    (comp (ref "T22")
      (value "BC238")
      (footprint "eagle-import:TO92")
      (libsource (lib "eagle-import") (part "BC238"))
    )
    (comp (ref "T25")
      (value "BC238")
      (footprint "eagle-import:TO92")
      (libsource (lib "eagle-import") (part "BC238"))
    )
    (comp (ref "T26")
      (value "BC238")
      (footprint "eagle-import:TO92")
      (libsource (lib "eagle-import") (part "BC238"))
    )
    (comp (ref "T27")
      (value "BC238")
      (footprint "eagle-import:TO92")
      (libsource (lib "eagle-import") (part "BC238"))
    )
    (comp (ref "T28")
      (value "BC238")
      (footprint "eagle-import:TO92")
      (libsource (lib "eagle-import") (part "BC238"))
    )
    (comp (ref "T29")
      (value "BC238")
      (footprint "eagle-import:TO92")
      (libsource (lib "eagle-import") (part "BC238"))
    )
    (comp (ref "T30")
      (value "BC238")
      (footprint "eagle-import:TO92")
      (libsource (lib "eagle-import") (part "BC238"))
    )
    (comp (ref "T31")
      (value "BC238")
      (footprint "eagle-import:TO92")
      (libsource (lib "eagle-import") (part "BC238"))
    )
    (comp (ref "T32")
      (value "BC238")
      (footprint "eagle-import:TO92")
      (libsource (lib "eagle-import") (part "BC238"))
    )
    (comp (ref "T33")
      (value "BC238")
      (footprint "eagle-import:TO92")
      (libsource (lib "eagle-import") (part "BC238"))
    )
    (comp (ref "T34")
      (value "BC238")
      (footprint "eagle-import:TO92")
      (libsource (lib "eagle-import") (part "BC238"))
    )
    (comp (ref "T35")
      (value "BC238")
      (footprint "eagle-import:TO92")
      (libsource (lib "eagle-import") (part "BC238"))
    )
    (comp (ref "T36")
      (value "BC238")
      (footprint "eagle-import:TO92")
      (libsource (lib "eagle-import") (part "BC238"))
    )
    (comp (ref "T37")
      (value "BC238")
      (footprint "eagle-import:TO92")
      (libsource (lib "eagle-import") (part "BC238"))
    )
    (comp (ref "T38")
      (value "BC238")
      (footprint "eagle-import:TO92")
      (libsource (lib "eagle-import") (part "BC238"))
    )
    (comp (ref "T39")
      (value "BC238")
      (footprint "eagle-import:TO92")
      (libsource (lib "eagle-import") (part "BC238"))
    )
    (comp (ref "T40")
      (value "BC238")
      (footprint "eagle-import:TO92")
      (libsource (lib "eagle-import") (part "BC238"))
    )
    (comp (ref "T41")
      (value "BC238")
      (footprint "eagle-import:TO92")
      (libsource (lib "eagle-import") (part "BC238"))
    )
    (comp (ref "T42")
      (value "BC238")
      (footprint "eagle-import:TO92")
      (libsource (lib "eagle-import") (part "BC238"))
    )
    (comp (ref "T43")
      (value "BC238")
      (footprint "eagle-import:TO92")
      (libsource (lib "eagle-import") (part "BC238"))
    )
    (comp (ref "T44")
      (value "BC238")
      (footprint "eagle-import:TO92")
      (libsource (lib "eagle-import") (part "BC238"))
    )
    (comp (ref "T45")
      (value "BC238")
      (footprint "eagle-import:TO92")
      (libsource (lib "eagle-import") (part "BC238"))
    )
    (comp (ref "T46")
      (value "BC238")
      (footprint "eagle-import:TO92")
      (libsource (lib "eagle-import") (part "BC238"))
    )
    (comp (ref "T47")
      (value "BC238")
      (footprint "eagle-import:TO92")
      (libsource (lib "eagle-import") (part "BC238"))
    )
    (comp (ref "T48")
      (value "BC238")
      (footprint "eagle-import:TO92")
      (libsource (lib "eagle-import") (part "BC238"))
    )
    (comp (ref "U$1")
      (value "100MILS")
      (footprint "eagle-import:100MIL")
      (libsource (lib "eagle-import") (part "100MILS"))
    )
    (comp (ref "U$2")
      (value "100MILS")
      (footprint "eagle-import:100MIL")
      (libsource (lib "eagle-import") (part "100MILS"))
    )
    (comp (ref "U$3")
      (value "100MILS")
      (footprint "eagle-import:100MIL")
      (libsource (lib "eagle-import") (part "100MILS"))
    )
    (comp (ref "U$4")
      (value "100MILS")
      (footprint "eagle-import:100MIL")
      (libsource (lib "eagle-import") (part "100MILS"))
    )
    (comp (ref "U$5")
      (value "100MILS")
      (footprint "eagle-import:100MIL")
      (libsource (lib "eagle-import") (part "100MILS"))
    )
    (comp (ref "U$6")
      (value "100MILS")
      (footprint "eagle-import:100MIL")
      (libsource (lib "eagle-import") (part "100MILS"))
    )
    (comp (ref "U$7")
      (value "100MILS")
      (footprint "eagle-import:100MIL")
      (libsource (lib "eagle-import") (part "100MILS"))
    )
    (comp (ref "U$8")
      (value "100MILS")
      (footprint "eagle-import:100MIL")
      (libsource (lib "eagle-import") (part "100MILS"))
    )
    (comp (ref "U$9")
      (value "100MILS")
      (footprint "eagle-import:100MIL")
      (libsource (lib "eagle-import") (part "100MILS"))
    )
    (comp (ref "U$10")
      (value "100MILS")
      (footprint "eagle-import:100MIL")
      (libsource (lib "eagle-import") (part "100MILS"))
    )
    (comp (ref "U$11")
      (value "100MILS")
      (footprint "eagle-import:100MIL")
      (libsource (lib "eagle-import") (part "100MILS"))
    )
    (comp (ref "U$12")
      (value "100MILS")
      (footprint "eagle-import:100MIL")
      (libsource (lib "eagle-import") (part "100MILS"))
    )
    (comp (ref "U$13")
      (value "100MILS")
      (footprint "eagle-import:100MIL")
      (libsource (lib "eagle-import") (part "100MILS"))
    )
    (comp (ref "U$14")
      (value "100MILS")
      (footprint "eagle-import:100MIL")
      (libsource (lib "eagle-import") (part "100MILS"))
    )
    (comp (ref "U$15")
      (value "100MILS")
      (footprint "eagle-import:100MIL")
      (libsource (lib "eagle-import") (part "100MILS"))
    )
    (comp (ref "U$16")
      (value "100MILS")
      (footprint "eagle-import:100MIL")
      (libsource (lib "eagle-import") (part "100MILS"))
    )
    (comp (ref "U$17")
      (value "100MILS")
      (footprint "eagle-import:100MIL")
      (libsource (lib "eagle-import") (part "100MILS"))
    )
    (comp (ref "U$18")
      (value "100MILS")
      (footprint "eagle-import:100MIL")
      (libsource (lib "eagle-import") (part "100MILS"))
    )
    (comp (ref "U$19")
      (value "100MILS")
      (footprint "eagle-import:100MIL")
      (libsource (lib "eagle-import") (part "100MILS"))
    )
    (comp (ref "U$20")
      (value "100MILS")
      (footprint "eagle-import:100MIL")
      (libsource (lib "eagle-import") (part "100MILS"))
    )
    (comp (ref "U$21")
      (value "100MILS")
      (footprint "eagle-import:100MIL")
      (libsource (lib "eagle-import") (part "100MILS"))
    )
    (comp (ref "U$22")
      (value "100MILS")
      (footprint "eagle-import:100MIL")
      (libsource (lib "eagle-import") (part "100MILS"))
    )
    (comp (ref "U$23")
      (value "100MILS")
      (footprint "eagle-import:100MIL")
      (libsource (lib "eagle-import") (part "100MILS"))
    )
    (comp (ref "U$24")
      (value "100MILS")
      (footprint "eagle-import:100MIL")
      (libsource (lib "eagle-import") (part "100MILS"))
    )
    (comp (ref "U$25")
      (value "100MILS")
      (footprint "eagle-import:100MIL")
      (libsource (lib "eagle-import") (part "100MILS"))
    )
    (comp (ref "U$26")
      (value "100MILS")
      (footprint "eagle-import:100MIL")
      (libsource (lib "eagle-import") (part "100MILS"))
    )
    (comp (ref "U$27")
      (value "100MILS")
      (footprint "eagle-import:100MIL")
      (libsource (lib "eagle-import") (part "100MILS"))
    )
    (comp (ref "U$28")
      (value "100MILS")
      (footprint "eagle-import:100MIL")
      (libsource (lib "eagle-import") (part "100MILS"))
    )
    (comp (ref "U$29")
      (value "100MILS")
      (footprint "eagle-import:100MIL")
      (libsource (lib "eagle-import") (part "100MILS"))
    )
    (comp (ref "U$30")
      (value "100MILS")
      (footprint "eagle-import:100MIL")
      (libsource (lib "eagle-import") (part "100MILS"))
    )
    (comp (ref "U$31")
      (value "100MILS")
      (footprint "eagle-import:100MIL")
      (libsource (lib "eagle-import") (part "100MILS"))
    )
    (comp (ref "U$32")
      (value "100MILS")
      (footprint "eagle-import:100MIL")
      (libsource (lib "eagle-import") (part "100MILS"))
    )
    (comp (ref "U$33")
      (value "100MILS")
      (footprint "eagle-import:100MIL")
      (libsource (lib "eagle-import") (part "100MILS"))
    )
    (comp (ref "U$34")
      (value "100MILS")
      (footprint "eagle-import:100MIL")
      (libsource (lib "eagle-import") (part "100MILS"))
    )
    (comp (ref "U$35")
      (value "100MILS")
      (footprint "eagle-import:100MIL")
      (libsource (lib "eagle-import") (part "100MILS"))
    )
    (comp (ref "U$36")
      (value "100MILS")
      (footprint "eagle-import:100MIL")
      (libsource (lib "eagle-import") (part "100MILS"))
    )
    (comp (ref "U$37")
      (value "100MILS")
      (footprint "eagle-import:100MIL")
      (libsource (lib "eagle-import") (part "100MILS"))
    )
    (comp (ref "U$38")
      (value "100MILS")
      (footprint "eagle-import:100MIL")
      (libsource (lib "eagle-import") (part "100MILS"))
    )
    (comp (ref "U$39")
      (value "100MILS")
      (footprint "eagle-import:100MIL")
      (libsource (lib "eagle-import") (part "100MILS"))
    )
    (comp (ref "U$40")
      (value "100MILS")
      (footprint "eagle-import:100MIL")
      (libsource (lib "eagle-import") (part "100MILS"))
    )
    (comp (ref "U$41")
      (value "100MILS")
      (footprint "eagle-import:100MIL")
      (libsource (lib "eagle-import") (part "100MILS"))
    )
    (comp (ref "U$42")
      (value "100MILS")
      (footprint "eagle-import:100MIL")
      (libsource (lib "eagle-import") (part "100MILS"))
    )
    (comp (ref "U$43")
      (value "100MILS")
      (footprint "eagle-import:100MIL")
      (libsource (lib "eagle-import") (part "100MILS"))
    )
    (comp (ref "U$44")
      (value "100MILS")
      (footprint "eagle-import:100MIL")
      (libsource (lib "eagle-import") (part "100MILS"))
    )
    (comp (ref "U1")
      (value "STM32F103RBT6")
      (footprint "eagle-import:QFP50P1200X1200X160-64N")
      (libsource (lib "eagle-import") (part "STM32F103RBT6"))
    )
    (comp (ref "X1")
      (value "F09HP")
      (footprint "eagle-import:F09HP")
      (libsource (lib "eagle-import") (part "F09HP"))
    )
    (comp (ref "X2")
      (value "F09HP")
      (footprint "eagle-import:F09HP")
      (libsource (lib "eagle-import") (part "F09HP"))
    )
  )
  (nets
    (net (code "1") (name "/COM1") (class "Default")
      (node (ref "K1") (pin "O1") (pinfunction "O_O1") (pintype "passive"))
      (node (ref "K12") (pin "O1") (pinfunction "O_O1") (pintype "passive"))
      (node (ref "K13") (pin "O1") (pinfunction "O_O1") (pintype "passive"))
      (node (ref "K16") (pin "O1") (pinfunction "O_O1") (pintype "passive"))
      (node (ref "K17") (pin "O1") (pinfunction "O_O1") (pintype "passive"))
      (node (ref "K18") (pin "O1") (pinfunction "O_O1") (pintype "passive"))
      (node (ref "K19") (pin "O1") (pinfunction "O_O1") (pintype "passive"))
      (node (ref "K2") (pin "O1") (pinfunction "O_O1") (pintype "passive"))
      (node (ref "K20") (pin "O1") (pinfunction "O_O1") (pintype "passive"))
      (node (ref "K21") (pin "O1") (pinfunction "O_O1") (pintype "passive"))
      (node (ref "K22") (pin "O1") (pinfunction "O_O1") (pintype "passive"))
      (node (ref "K25") (pin "O1") (pinfunction "O_O1") (pintype "passive"))
      (node (ref "K26") (pin "O1") (pinfunction "O_O1") (pintype "passive"))
      (node (ref "K27") (pin "O1") (pinfunction "O_O1") (pintype "passive"))
      (node (ref "K28") (pin "O1") (pinfunction "O_O1") (pintype "passive"))
      (node (ref "K29") (pin "O1") (pinfunction "O_O1") (pintype "passive"))
      (node (ref "K3") (pin "O1") (pinfunction "O_O1") (pintype "passive"))
      (node (ref "K30") (pin "O1") (pinfunction "O_O1") (pintype "passive"))
      (node (ref "K31") (pin "O1") (pinfunction "O_O1") (pintype "passive"))
      (node (ref "K32") (pin "O1") (pinfunction "O_O1") (pintype "passive"))
      (node (ref "K33") (pin "O1") (pinfunction "O_O1") (pintype "passive"))
      (node (ref "K34") (pin "O1") (pinfunction "O_O1") (pintype "passive"))
      (node (ref "K35") (pin "O1") (pinfunction "O_O1") (pintype "passive"))
      (node (ref "K36") (pin "O1") (pinfunction "O_O1") (pintype "passive"))
      (node (ref "K37") (pin "O1") (pinfunction "O_O1") (pintype "passive"))
      (node (ref "K38") (pin "O1") (pinfunction "O_O1") (pintype "passive"))
      (node (ref "K39") (pin "O1") (pinfunction "O_O1") (pintype "passive"))
      (node (ref "K4") (pin "O1") (pinfunction "O_O1") (pintype "passive"))
      (node (ref "K40") (pin "O1") (pinfunction "O_O1") (pintype "passive"))
      (node (ref "K41") (pin "O1") (pinfunction "O_O1") (pintype "passive"))
      (node (ref "K42") (pin "O1") (pinfunction "O_O1") (pintype "passive"))
      (node (ref "K43") (pin "O1") (pinfunction "O_O1") (pintype "passive"))
      (node (ref "K44") (pin "O1") (pinfunction "O_O1") (pintype "passive"))
      (node (ref "K45") (pin "O1") (pinfunction "O_O1") (pintype "passive"))
      (node (ref "K46") (pin "O1") (pinfunction "O_O1") (pintype "passive"))
      (node (ref "K47") (pin "O1") (pinfunction "O_O1") (pintype "passive"))
      (node (ref "K48") (pin "O1") (pinfunction "O_O1") (pintype "passive"))
      (node (ref "K5") (pin "O1") (pinfunction "O_O1") (pintype "passive"))
      (node (ref "K6") (pin "O1") (pinfunction "O_O1") (pintype "passive"))
      (node (ref "K7") (pin "O1") (pinfunction "O_O1") (pintype "passive"))
      (node (ref "K8") (pin "O1") (pinfunction "O_O1") (pintype "passive"))
      (node (ref "K9") (pin "O1") (pinfunction "O_O1") (pintype "passive"))
      (node (ref "U$42") (pin "P$1") (pinfunction "1_P$1") (pintype "passive"))
    )
    (net (code "2") (name "/COM2") (class "Default")
      (node (ref "K1") (pin "S1") (pinfunction "S_S1") (pintype "passive"))
      (node (ref "K12") (pin "S1") (pinfunction "S_S1") (pintype "passive"))
      (node (ref "K13") (pin "S1") (pinfunction "S_S1") (pintype "passive"))
      (node (ref "K16") (pin "S1") (pinfunction "S_S1") (pintype "passive"))
      (node (ref "K17") (pin "S1") (pinfunction "S_S1") (pintype "passive"))
      (node (ref "K18") (pin "S1") (pinfunction "S_S1") (pintype "passive"))
      (node (ref "K19") (pin "S1") (pinfunction "S_S1") (pintype "passive"))
      (node (ref "K2") (pin "S1") (pinfunction "S_S1") (pintype "passive"))
      (node (ref "K20") (pin "S1") (pinfunction "S_S1") (pintype "passive"))
      (node (ref "K21") (pin "S1") (pinfunction "S_S1") (pintype "passive"))
      (node (ref "K22") (pin "S1") (pinfunction "S_S1") (pintype "passive"))
      (node (ref "K25") (pin "S1") (pinfunction "S_S1") (pintype "passive"))
      (node (ref "K26") (pin "S1") (pinfunction "S_S1") (pintype "passive"))
      (node (ref "K27") (pin "S1") (pinfunction "S_S1") (pintype "passive"))
      (node (ref "K28") (pin "S1") (pinfunction "S_S1") (pintype "passive"))
      (node (ref "K29") (pin "S1") (pinfunction "S_S1") (pintype "passive"))
      (node (ref "K3") (pin "S1") (pinfunction "S_S1") (pintype "passive"))
      (node (ref "K30") (pin "S1") (pinfunction "S_S1") (pintype "passive"))
      (node (ref "K31") (pin "S1") (pinfunction "S_S1") (pintype "passive"))
      (node (ref "K32") (pin "S1") (pinfunction "S_S1") (pintype "passive"))
      (node (ref "K33") (pin "S1") (pinfunction "S_S1") (pintype "passive"))
      (node (ref "K34") (pin "S1") (pinfunction "S_S1") (pintype "passive"))
      (node (ref "K35") (pin "S1") (pinfunction "S_S1") (pintype "passive"))
      (node (ref "K36") (pin "S1") (pinfunction "S_S1") (pintype "passive"))
      (node (ref "K37") (pin "S1") (pinfunction "S_S1") (pintype "passive"))
      (node (ref "K38") (pin "S1") (pinfunction "S_S1") (pintype "passive"))
      (node (ref "K39") (pin "S1") (pinfunction "S_S1") (pintype "passive"))
      (node (ref "K4") (pin "S1") (pinfunction "S_S1") (pintype "passive"))
      (node (ref "K40") (pin "S1") (pinfunction "S_S1") (pintype "passive"))
      (node (ref "K41") (pin "S1") (pinfunction "S_S1") (pintype "passive"))
      (node (ref "K42") (pin "S1") (pinfunction "S_S1") (pintype "passive"))
      (node (ref "K43") (pin "S1") (pinfunction "S_S1") (pintype "passive"))
      (node (ref "K44") (pin "S1") (pinfunction "S_S1") (pintype "passive"))
      (node (ref "K45") (pin "S1") (pinfunction "S_S1") (pintype "passive"))
      (node (ref "K46") (pin "S1") (pinfunction "S_S1") (pintype "passive"))
      (node (ref "K47") (pin "S1") (pinfunction "S_S1") (pintype "passive"))
      (node (ref "K48") (pin "S1") (pinfunction "S_S1") (pintype "passive"))
      (node (ref "K5") (pin "S1") (pinfunction "S_S1") (pintype "passive"))
      (node (ref "K6") (pin "S1") (pinfunction "S_S1") (pintype "passive"))
      (node (ref "K7") (pin "S1") (pinfunction "S_S1") (pintype "passive"))
      (node (ref "K8") (pin "S1") (pinfunction "S_S1") (pintype "passive"))
      (node (ref "K9") (pin "S1") (pinfunction "S_S1") (pintype "passive"))
      (node (ref "U$43") (pin "P$1") (pinfunction "1_P$1") (pintype "passive"))
    )
    (net (code "3") (name "/GND") (class "Default")
      (node (ref "C1") (pin "2") (pinfunction "2_2") (pintype "passive"))
      (node (ref "C10") (pin "2") (pinfunction "2_2") (pintype "passive"))
      (node (ref "C11") (pin "2") (pinfunction "2_2") (pintype "passive"))
      (node (ref "C12") (pin "2") (pinfunction "2_2") (pintype "passive"))
      (node (ref "C13") (pin "1") (pinfunction "1_1") (pintype "passive"))
      (node (ref "C2") (pin "1") (pinfunction "1_1") (pintype "passive"))
      (node (ref "C4") (pin "2") (pinfunction "2_2") (pintype "passive"))
      (node (ref "C5") (pin "1") (pinfunction "1_1") (pintype "passive"))
      (node (ref "C6") (pin "2") (pinfunction "2_2") (pintype "passive"))
      (node (ref "C7") (pin "2") (pinfunction "2_2") (pintype "passive"))
      (node (ref "C8") (pin "2") (pinfunction "2_2") (pintype "passive"))
      (node (ref "C9") (pin "2") (pinfunction "2_2") (pintype "passive"))
      (node (ref "IC1") (pin "1") (pinfunction "GND_1") (pintype "power_in"))
      (node (ref "K1") (pin "P2") (pinfunction "P_P2") (pintype "passive"))
      (node (ref "K12") (pin "P2") (pinfunction "P_P2") (pintype "passive"))
      (node (ref "K13") (pin "P2") (pinfunction "P_P2") (pintype "passive"))
      (node (ref "K16") (pin "P2") (pinfunction "P_P2") (pintype "passive"))
      (node (ref "K17") (pin "P2") (pinfunction "P_P2") (pintype "passive"))
      (node (ref "K18") (pin "P2") (pinfunction "P_P2") (pintype "passive"))
      (node (ref "K19") (pin "P2") (pinfunction "P_P2") (pintype "passive"))
      (node (ref "K2") (pin "P2") (pinfunction "P_P2") (pintype "passive"))
      (node (ref "K20") (pin "P2") (pinfunction "P_P2") (pintype "passive"))
      (node (ref "K21") (pin "P2") (pinfunction "P_P2") (pintype "passive"))
      (node (ref "K22") (pin "P2") (pinfunction "P_P2") (pintype "passive"))
      (node (ref "K25") (pin "P2") (pinfunction "P_P2") (pintype "passive"))
      (node (ref "K26") (pin "P2") (pinfunction "P_P2") (pintype "passive"))
      (node (ref "K27") (pin "P2") (pinfunction "P_P2") (pintype "passive"))
      (node (ref "K28") (pin "P2") (pinfunction "P_P2") (pintype "passive"))
      (node (ref "K29") (pin "P2") (pinfunction "P_P2") (pintype "passive"))
      (node (ref "K3") (pin "P2") (pinfunction "P_P2") (pintype "passive"))
      (node (ref "K30") (pin "P2") (pinfunction "P_P2") (pintype "passive"))
      (node (ref "K31") (pin "P2") (pinfunction "P_P2") (pintype "passive"))
      (node (ref "K32") (pin "P2") (pinfunction "P_P2") (pintype "passive"))
      (node (ref "K33") (pin "P2") (pinfunction "P_P2") (pintype "passive"))
      (node (ref "K34") (pin "P2") (pinfunction "P_P2") (pintype "passive"))
      (node (ref "K35") (pin "P2") (pinfunction "P_P2") (pintype "passive"))
      (node (ref "K36") (pin "P2") (pinfunction "P_P2") (pintype "passive"))
      (node (ref "K37") (pin "P2") (pinfunction "P_P2") (pintype "passive"))
      (node (ref "K38") (pin "P2") (pinfunction "P_P2") (pintype "passive"))
      (node (ref "K39") (pin "P2") (pinfunction "P_P2") (pintype "passive"))
      (node (ref "K4") (pin "P2") (pinfunction "P_P2") (pintype "passive"))
      (node (ref "K40") (pin "P2") (pinfunction "P_P2") (pintype "passive"))
      (node (ref "K41") (pin "P2") (pinfunction "P_P2") (pintype "passive"))
      (node (ref "K42") (pin "P2") (pinfunction "P_P2") (pintype "passive"))
      (node (ref "K43") (pin "P2") (pinfunction "P_P2") (pintype "passive"))
      (node (ref "K44") (pin "P2") (pinfunction "P_P2") (pintype "passive"))
      (node (ref "K45") (pin "P2") (pinfunction "P_P2") (pintype "passive"))
      (node (ref "K46") (pin "P2") (pinfunction "P_P2") (pintype "passive"))
      (node (ref "K47") (pin "P2") (pinfunction "P_P2") (pintype "passive"))
      (node (ref "K48") (pin "P2") (pinfunction "P_P2") (pintype "passive"))
      (node (ref "K5") (pin "P2") (pinfunction "P_P2") (pintype "passive"))
      (node (ref "K6") (pin "P2") (pinfunction "P_P2") (pintype "passive"))
      (node (ref "K7") (pin "P2") (pinfunction "P_P2") (pintype "passive"))
      (node (ref "K8") (pin "P2") (pinfunction "P_P2") (pintype "passive"))
      (node (ref "K9") (pin "P2") (pinfunction "P_P2") (pintype "passive"))
      (node (ref "R1") (pin "1") (pinfunction "1_1") (pintype "passive"))
      (node (ref "R24") (pin "2") (pinfunction "2_2") (pintype "passive"))
      (node (ref "R4") (pin "1") (pinfunction "1_1") (pintype "passive"))
      (node (ref "S2") (pin "4") (pinfunction "4_4") (pintype "passive"))
      (node (ref "SV1") (pin "3") (pinfunction "3_3") (pintype "passive"))
      (node (ref "SV2") (pin "3") (pinfunction "3_3") (pintype "passive"))
      (node (ref "SV3") (pin "3") (pinfunction "3_3") (pintype "passive"))
      (node (ref "SV5") (pin "3") (pinfunction "3_3") (pintype "passive"))
      (node (ref "T1") (pin "1") (pinfunction "E_1") (pintype "passive"))
      (node (ref "T12") (pin "1") (pinfunction "E_1") (pintype "passive"))
      (node (ref "T13") (pin "1") (pinfunction "E_1") (pintype "passive"))
      (node (ref "T16") (pin "1") (pinfunction "E_1") (pintype "passive"))
      (node (ref "T17") (pin "1") (pinfunction "E_1") (pintype "passive"))
      (node (ref "T18") (pin "1") (pinfunction "E_1") (pintype "passive"))
      (node (ref "T19") (pin "1") (pinfunction "E_1") (pintype "passive"))
      (node (ref "T2") (pin "1") (pinfunction "E_1") (pintype "passive"))
      (node (ref "T20") (pin "1") (pinfunction "E_1") (pintype "passive"))
      (node (ref "T21") (pin "1") (pinfunction "E_1") (pintype "passive"))
      (node (ref "T22") (pin "1") (pinfunction "E_1") (pintype "passive"))
      (node (ref "T25") (pin "1") (pinfunction "E_1") (pintype "passive"))
      (node (ref "T26") (pin "1") (pinfunction "E_1") (pintype "passive"))
      (node (ref "T27") (pin "1") (pinfunction "E_1") (pintype "passive"))
      (node (ref "T28") (pin "1") (pinfunction "E_1") (pintype "passive"))
      (node (ref "T29") (pin "1") (pinfunction "E_1") (pintype "passive"))
      (node (ref "T3") (pin "1") (pinfunction "E_1") (pintype "passive"))
      (node (ref "T30") (pin "1") (pinfunction "E_1") (pintype "passive"))
      (node (ref "T31") (pin "1") (pinfunction "E_1") (pintype "passive"))
      (node (ref "T32") (pin "1") (pinfunction "E_1") (pintype "passive"))
      (node (ref "T33") (pin "1") (pinfunction "E_1") (pintype "passive"))
      (node (ref "T34") (pin "1") (pinfunction "E_1") (pintype "passive"))
      (node (ref "T35") (pin "1") (pinfunction "E_1") (pintype "passive"))
      (node (ref "T36") (pin "1") (pinfunction "E_1") (pintype "passive"))
      (node (ref "T37") (pin "1") (pinfunction "E_1") (pintype "passive"))
      (node (ref "T38") (pin "1") (pinfunction "E_1") (pintype "passive"))
      (node (ref "T39") (pin "1") (pinfunction "E_1") (pintype "passive"))
      (node (ref "T4") (pin "1") (pinfunction "E_1") (pintype "passive"))
      (node (ref "T40") (pin "1") (pinfunction "E_1") (pintype "passive"))
      (node (ref "T41") (pin "1") (pinfunction "E_1") (pintype "passive"))
      (node (ref "T42") (pin "1") (pinfunction "E_1") (pintype "passive"))
      (node (ref "T43") (pin "1") (pinfunction "E_1") (pintype "passive"))
      (node (ref "T44") (pin "1") (pinfunction "E_1") (pintype "passive"))
      (node (ref "T45") (pin "1") (pinfunction "E_1") (pintype "passive"))
      (node (ref "T46") (pin "1") (pinfunction "E_1") (pintype "passive"))
      (node (ref "T47") (pin "1") (pinfunction "E_1") (pintype "passive"))
      (node (ref "T48") (pin "1") (pinfunction "E_1") (pintype "passive"))
      (node (ref "T5") (pin "1") (pinfunction "E_1") (pintype "passive"))
      (node (ref "T6") (pin "1") (pinfunction "E_1") (pintype "passive"))
      (node (ref "T7") (pin "1") (pinfunction "E_1") (pintype "passive"))
      (node (ref "T8") (pin "1") (pinfunction "E_1") (pintype "passive"))
      (node (ref "T9") (pin "1") (pinfunction "E_1") (pintype "passive"))
      (node (ref "U$1") (pin "P$2") (pinfunction "GND_P$2") (pintype "passive"))
      (node (ref "U$1") (pin "P$3") (pinfunction "GND_P$3") (pintype "passive"))
      (node (ref "U$1") (pin "P$4") (pinfunction "GND_P$4") (pintype "passive"))
      (node (ref "U$1") (pin "P$5") (pinfunction "GND_P$5") (pintype "passive"))
      (node (ref "U$10") (pin "P$2") (pinfunction "GND_P$2") (pintype "passive"))
      (node (ref "U$10") (pin "P$3") (pinfunction "GND_P$3") (pintype "passive"))
      (node (ref "U$10") (pin "P$4") (pinfunction "GND_P$4") (pintype "passive"))
      (node (ref "U$10") (pin "P$5") (pinfunction "GND_P$5") (pintype "passive"))
      (node (ref "U$11") (pin "P$2") (pinfunction "GND_P$2") (pintype "passive"))
      (node (ref "U$11") (pin "P$3") (pinfunction "GND_P$3") (pintype "passive"))
      (node (ref "U$11") (pin "P$4") (pinfunction "GND_P$4") (pintype "passive"))
      (node (ref "U$11") (pin "P$5") (pinfunction "GND_P$5") (pintype "passive"))
      (node (ref "U$12") (pin "P$2") (pinfunction "GND_P$2") (pintype "passive"))
      (node (ref "U$12") (pin "P$3") (pinfunction "GND_P$3") (pintype "passive"))
      (node (ref "U$12") (pin "P$4") (pinfunction "GND_P$4") (pintype "passive"))
      (node (ref "U$12") (pin "P$5") (pinfunction "GND_P$5") (pintype "passive"))
      (node (ref "U$13") (pin "P$2") (pinfunction "GND_P$2") (pintype "passive"))
      (node (ref "U$13") (pin "P$3") (pinfunction "GND_P$3") (pintype "passive"))
      (node (ref "U$13") (pin "P$4") (pinfunction "GND_P$4") (pintype "passive"))
      (node (ref "U$13") (pin "P$5") (pinfunction "GND_P$5") (pintype "passive"))
      (node (ref "U$14") (pin "P$2") (pinfunction "GND_P$2") (pintype "passive"))
      (node (ref "U$14") (pin "P$3") (pinfunction "GND_P$3") (pintype "passive"))
      (node (ref "U$14") (pin "P$4") (pinfunction "GND_P$4") (pintype "passive"))
      (node (ref "U$14") (pin "P$5") (pinfunction "GND_P$5") (pintype "passive"))
      (node (ref "U$15") (pin "P$2") (pinfunction "GND_P$2") (pintype "passive"))
      (node (ref "U$15") (pin "P$3") (pinfunction "GND_P$3") (pintype "passive"))
      (node (ref "U$15") (pin "P$4") (pinfunction "GND_P$4") (pintype "passive"))
      (node (ref "U$15") (pin "P$5") (pinfunction "GND_P$5") (pintype "passive"))
      (node (ref "U$16") (pin "P$2") (pinfunction "GND_P$2") (pintype "passive"))
      (node (ref "U$16") (pin "P$3") (pinfunction "GND_P$3") (pintype "passive"))
      (node (ref "U$16") (pin "P$4") (pinfunction "GND_P$4") (pintype "passive"))
      (node (ref "U$16") (pin "P$5") (pinfunction "GND_P$5") (pintype "passive"))
      (node (ref "U$17") (pin "P$2") (pinfunction "GND_P$2") (pintype "passive"))
      (node (ref "U$17") (pin "P$3") (pinfunction "GND_P$3") (pintype "passive"))
      (node (ref "U$17") (pin "P$4") (pinfunction "GND_P$4") (pintype "passive"))
      (node (ref "U$17") (pin "P$5") (pinfunction "GND_P$5") (pintype "passive"))
      (node (ref "U$18") (pin "P$2") (pinfunction "GND_P$2") (pintype "passive"))
      (node (ref "U$18") (pin "P$3") (pinfunction "GND_P$3") (pintype "passive"))
      (node (ref "U$18") (pin "P$4") (pinfunction "GND_P$4") (pintype "passive"))
      (node (ref "U$18") (pin "P$5") (pinfunction "GND_P$5") (pintype "passive"))
      (node (ref "U$19") (pin "P$2") (pinfunction "GND_P$2") (pintype "passive"))
      (node (ref "U$19") (pin "P$3") (pinfunction "GND_P$3") (pintype "passive"))
      (node (ref "U$19") (pin "P$4") (pinfunction "GND_P$4") (pintype "passive"))
      (node (ref "U$19") (pin "P$5") (pinfunction "GND_P$5") (pintype "passive"))
      (node (ref "U$2") (pin "P$2") (pinfunction "GND_P$2") (pintype "passive"))
      (node (ref "U$2") (pin "P$3") (pinfunction "GND_P$3") (pintype "passive"))
      (node (ref "U$2") (pin "P$4") (pinfunction "GND_P$4") (pintype "passive"))
      (node (ref "U$2") (pin "P$5") (pinfunction "GND_P$5") (pintype "passive"))
      (node (ref "U$20") (pin "P$2") (pinfunction "GND_P$2") (pintype "passive"))
      (node (ref "U$20") (pin "P$3") (pinfunction "GND_P$3") (pintype "passive"))
      (node (ref "U$20") (pin "P$4") (pinfunction "GND_P$4") (pintype "passive"))
      (node (ref "U$20") (pin "P$5") (pinfunction "GND_P$5") (pintype "passive"))
      (node (ref "U$21") (pin "P$2") (pinfunction "GND_P$2") (pintype "passive"))
      (node (ref "U$21") (pin "P$3") (pinfunction "GND_P$3") (pintype "passive"))
      (node (ref "U$21") (pin "P$4") (pinfunction "GND_P$4") (pintype "passive"))
      (node (ref "U$21") (pin "P$5") (pinfunction "GND_P$5") (pintype "passive"))
      (node (ref "U$22") (pin "P$2") (pinfunction "GND_P$2") (pintype "passive"))
      (node (ref "U$22") (pin "P$3") (pinfunction "GND_P$3") (pintype "passive"))
      (node (ref "U$22") (pin "P$4") (pinfunction "GND_P$4") (pintype "passive"))
      (node (ref "U$22") (pin "P$5") (pinfunction "GND_P$5") (pintype "passive"))
      (node (ref "U$23") (pin "P$2") (pinfunction "GND_P$2") (pintype "passive"))
      (node (ref "U$23") (pin "P$3") (pinfunction "GND_P$3") (pintype "passive"))
      (node (ref "U$23") (pin "P$4") (pinfunction "GND_P$4") (pintype "passive"))
      (node (ref "U$23") (pin "P$5") (pinfunction "GND_P$5") (pintype "passive"))
      (node (ref "U$24") (pin "P$2") (pinfunction "GND_P$2") (pintype "passive"))
      (node (ref "U$24") (pin "P$3") (pinfunction "GND_P$3") (pintype "passive"))
      (node (ref "U$24") (pin "P$4") (pinfunction "GND_P$4") (pintype "passive"))
      (node (ref "U$24") (pin "P$5") (pinfunction "GND_P$5") (pintype "passive"))
      (node (ref "U$25") (pin "P$2") (pinfunction "GND_P$2") (pintype "passive"))
      (node (ref "U$25") (pin "P$3") (pinfunction "GND_P$3") (pintype "passive"))
      (node (ref "U$25") (pin "P$4") (pinfunction "GND_P$4") (pintype "passive"))
      (node (ref "U$25") (pin "P$5") (pinfunction "GND_P$5") (pintype "passive"))
      (node (ref "U$26") (pin "P$2") (pinfunction "GND_P$2") (pintype "passive"))
      (node (ref "U$26") (pin "P$3") (pinfunction "GND_P$3") (pintype "passive"))
      (node (ref "U$26") (pin "P$4") (pinfunction "GND_P$4") (pintype "passive"))
      (node (ref "U$26") (pin "P$5") (pinfunction "GND_P$5") (pintype "passive"))
      (node (ref "U$27") (pin "P$2") (pinfunction "GND_P$2") (pintype "passive"))
      (node (ref "U$27") (pin "P$3") (pinfunction "GND_P$3") (pintype "passive"))
      (node (ref "U$27") (pin "P$4") (pinfunction "GND_P$4") (pintype "passive"))
      (node (ref "U$27") (pin "P$5") (pinfunction "GND_P$5") (pintype "passive"))
      (node (ref "U$28") (pin "P$2") (pinfunction "GND_P$2") (pintype "passive"))
      (node (ref "U$28") (pin "P$3") (pinfunction "GND_P$3") (pintype "passive"))
      (node (ref "U$28") (pin "P$4") (pinfunction "GND_P$4") (pintype "passive"))
      (node (ref "U$28") (pin "P$5") (pinfunction "GND_P$5") (pintype "passive"))
      (node (ref "U$29") (pin "P$2") (pinfunction "GND_P$2") (pintype "passive"))
      (node (ref "U$29") (pin "P$3") (pinfunction "GND_P$3") (pintype "passive"))
      (node (ref "U$29") (pin "P$4") (pinfunction "GND_P$4") (pintype "passive"))
      (node (ref "U$29") (pin "P$5") (pinfunction "GND_P$5") (pintype "passive"))
      (node (ref "U$3") (pin "P$2") (pinfunction "GND_P$2") (pintype "passive"))
      (node (ref "U$3") (pin "P$3") (pinfunction "GND_P$3") (pintype "passive"))
      (node (ref "U$3") (pin "P$4") (pinfunction "GND_P$4") (pintype "passive"))
      (node (ref "U$3") (pin "P$5") (pinfunction "GND_P$5") (pintype "passive"))
      (node (ref "U$30") (pin "P$2") (pinfunction "GND_P$2") (pintype "passive"))
      (node (ref "U$30") (pin "P$3") (pinfunction "GND_P$3") (pintype "passive"))
      (node (ref "U$30") (pin "P$4") (pinfunction "GND_P$4") (pintype "passive"))
      (node (ref "U$30") (pin "P$5") (pinfunction "GND_P$5") (pintype "passive"))
      (node (ref "U$31") (pin "P$2") (pinfunction "GND_P$2") (pintype "passive"))
      (node (ref "U$31") (pin "P$3") (pinfunction "GND_P$3") (pintype "passive"))
      (node (ref "U$31") (pin "P$4") (pinfunction "GND_P$4") (pintype "passive"))
      (node (ref "U$31") (pin "P$5") (pinfunction "GND_P$5") (pintype "passive"))
      (node (ref "U$32") (pin "P$2") (pinfunction "GND_P$2") (pintype "passive"))
      (node (ref "U$32") (pin "P$3") (pinfunction "GND_P$3") (pintype "passive"))
      (node (ref "U$32") (pin "P$4") (pinfunction "GND_P$4") (pintype "passive"))
      (node (ref "U$32") (pin "P$5") (pinfunction "GND_P$5") (pintype "passive"))
      (node (ref "U$33") (pin "P$2") (pinfunction "GND_P$2") (pintype "passive"))
      (node (ref "U$33") (pin "P$3") (pinfunction "GND_P$3") (pintype "passive"))
      (node (ref "U$33") (pin "P$4") (pinfunction "GND_P$4") (pintype "passive"))
      (node (ref "U$33") (pin "P$5") (pinfunction "GND_P$5") (pintype "passive"))
      (node (ref "U$34") (pin "P$2") (pinfunction "GND_P$2") (pintype "passive"))
      (node (ref "U$34") (pin "P$3") (pinfunction "GND_P$3") (pintype "passive"))
      (node (ref "U$34") (pin "P$4") (pinfunction "GND_P$4") (pintype "passive"))
      (node (ref "U$34") (pin "P$5") (pinfunction "GND_P$5") (pintype "passive"))
      (node (ref "U$35") (pin "P$2") (pinfunction "GND_P$2") (pintype "passive"))
      (node (ref "U$35") (pin "P$3") (pinfunction "GND_P$3") (pintype "passive"))
      (node (ref "U$35") (pin "P$4") (pinfunction "GND_P$4") (pintype "passive"))
      (node (ref "U$35") (pin "P$5") (pinfunction "GND_P$5") (pintype "passive"))
      (node (ref "U$36") (pin "P$2") (pinfunction "GND_P$2") (pintype "passive"))
      (node (ref "U$36") (pin "P$3") (pinfunction "GND_P$3") (pintype "passive"))
      (node (ref "U$36") (pin "P$4") (pinfunction "GND_P$4") (pintype "passive"))
      (node (ref "U$36") (pin "P$5") (pinfunction "GND_P$5") (pintype "passive"))
      (node (ref "U$37") (pin "P$2") (pinfunction "GND_P$2") (pintype "passive"))
      (node (ref "U$37") (pin "P$3") (pinfunction "GND_P$3") (pintype "passive"))
      (node (ref "U$37") (pin "P$4") (pinfunction "GND_P$4") (pintype "passive"))
      (node (ref "U$37") (pin "P$5") (pinfunction "GND_P$5") (pintype "passive"))
      (node (ref "U$38") (pin "P$2") (pinfunction "GND_P$2") (pintype "passive"))
      (node (ref "U$38") (pin "P$3") (pinfunction "GND_P$3") (pintype "passive"))
      (node (ref "U$38") (pin "P$4") (pinfunction "GND_P$4") (pintype "passive"))
      (node (ref "U$38") (pin "P$5") (pinfunction "GND_P$5") (pintype "passive"))
      (node (ref "U$39") (pin "P$2") (pinfunction "GND_P$2") (pintype "passive"))
      (node (ref "U$39") (pin "P$3") (pinfunction "GND_P$3") (pintype "passive"))
      (node (ref "U$39") (pin "P$4") (pinfunction "GND_P$4") (pintype "passive"))
      (node (ref "U$39") (pin "P$5") (pinfunction "GND_P$5") (pintype "passive"))
      (node (ref "U$4") (pin "P$2") (pinfunction "GND_P$2") (pintype "passive"))
      (node (ref "U$4") (pin "P$3") (pinfunction "GND_P$3") (pintype "passive"))
      (node (ref "U$4") (pin "P$4") (pinfunction "GND_P$4") (pintype "passive"))
      (node (ref "U$4") (pin "P$5") (pinfunction "GND_P$5") (pintype "passive"))
      (node (ref "U$40") (pin "P$2") (pinfunction "GND_P$2") (pintype "passive"))
      (node (ref "U$40") (pin "P$3") (pinfunction "GND_P$3") (pintype "passive"))
      (node (ref "U$40") (pin "P$4") (pinfunction "GND_P$4") (pintype "passive"))
      (node (ref "U$40") (pin "P$5") (pinfunction "GND_P$5") (pintype "passive"))
      (node (ref "U$41") (pin "P$2") (pinfunction "GND_P$2") (pintype "passive"))
      (node (ref "U$41") (pin "P$3") (pinfunction "GND_P$3") (pintype "passive"))
      (node (ref "U$41") (pin "P$4") (pinfunction "GND_P$4") (pintype "passive"))
      (node (ref "U$41") (pin "P$5") (pinfunction "GND_P$5") (pintype "passive"))
      (node (ref "U$42") (pin "P$2") (pinfunction "GND_P$2") (pintype "passive"))
      (node (ref "U$42") (pin "P$3") (pinfunction "GND_P$3") (pintype "passive"))
      (node (ref "U$42") (pin "P$4") (pinfunction "GND_P$4") (pintype "passive"))
      (node (ref "U$42") (pin "P$5") (pinfunction "GND_P$5") (pintype "passive"))
      (node (ref "U$43") (pin "P$2") (pinfunction "GND_P$2") (pintype "passive"))
      (node (ref "U$43") (pin "P$3") (pinfunction "GND_P$3") (pintype "passive"))
      (node (ref "U$43") (pin "P$4") (pinfunction "GND_P$4") (pintype "passive"))
      (node (ref "U$43") (pin "P$5") (pinfunction "GND_P$5") (pintype "passive"))
      (node (ref "U$44") (pin "P$2") (pinfunction "GND_P$2") (pintype "passive"))
      (node (ref "U$44") (pin "P$3") (pinfunction "GND_P$3") (pintype "passive"))
      (node (ref "U$44") (pin "P$4") (pinfunction "GND_P$4") (pintype "passive"))
      (node (ref "U$44") (pin "P$5") (pinfunction "GND_P$5") (pintype "passive"))
      (node (ref "U$5") (pin "P$2") (pinfunction "GND_P$2") (pintype "passive"))
      (node (ref "U$5") (pin "P$3") (pinfunction "GND_P$3") (pintype "passive"))
      (node (ref "U$5") (pin "P$4") (pinfunction "GND_P$4") (pintype "passive"))
      (node (ref "U$5") (pin "P$5") (pinfunction "GND_P$5") (pintype "passive"))
      (node (ref "U$6") (pin "P$2") (pinfunction "GND_P$2") (pintype "passive"))
      (node (ref "U$6") (pin "P$3") (pinfunction "GND_P$3") (pintype "passive"))
      (node (ref "U$6") (pin "P$4") (pinfunction "GND_P$4") (pintype "passive"))
      (node (ref "U$6") (pin "P$5") (pinfunction "GND_P$5") (pintype "passive"))
      (node (ref "U$7") (pin "P$2") (pinfunction "GND_P$2") (pintype "passive"))
      (node (ref "U$7") (pin "P$3") (pinfunction "GND_P$3") (pintype "passive"))
      (node (ref "U$7") (pin "P$4") (pinfunction "GND_P$4") (pintype "passive"))
      (node (ref "U$7") (pin "P$5") (pinfunction "GND_P$5") (pintype "passive"))
      (node (ref "U$8") (pin "P$2") (pinfunction "GND_P$2") (pintype "passive"))
      (node (ref "U$8") (pin "P$3") (pinfunction "GND_P$3") (pintype "passive"))
      (node (ref "U$8") (pin "P$4") (pinfunction "GND_P$4") (pintype "passive"))
      (node (ref "U$8") (pin "P$5") (pinfunction "GND_P$5") (pintype "passive"))
      (node (ref "U$9") (pin "P$2") (pinfunction "GND_P$2") (pintype "passive"))
      (node (ref "U$9") (pin "P$3") (pinfunction "GND_P$3") (pintype "passive"))
      (node (ref "U$9") (pin "P$4") (pinfunction "GND_P$4") (pintype "passive"))
      (node (ref "U$9") (pin "P$5") (pinfunction "GND_P$5") (pintype "passive"))
      (node (ref "U1") (pin "18") (pinfunction "VSS_4_18") (pintype "passive"))
      (node (ref "U1") (pin "31") (pinfunction "VSS_1_31") (pintype "passive"))
      (node (ref "U1") (pin "47") (pinfunction "VSS_2_47") (pintype "passive"))
      (node (ref "U1") (pin "63") (pinfunction "VSS_3_63") (pintype "passive"))
      (node (ref "X1") (pin "3") (pinfunction "3_3") (pintype "passive"))
      (node (ref "X2") (pin "3") (pinfunction "3_3") (pintype "passive"))
    )
    (net (code "4") (name "/I2C_SCL") (class "Default")
      (node (ref "SV5") (pin "2") (pinfunction "2_2") (pintype "passive"))
      (node (ref "U1") (pin "58") (pinfunction "PB6_58") (pintype "bidirectional"))
      (node (ref "X1") (pin "9") (pinfunction "9_9") (pintype "passive"))
      (node (ref "X2") (pin "9") (pinfunction "9_9") (pintype "passive"))
    )
    (net (code "5") (name "/I2C_SDA") (class "Default")
      (node (ref "SV5") (pin "1") (pinfunction "1_1") (pintype "passive"))
      (node (ref "U1") (pin "59") (pinfunction "PB7_59") (pintype "bidirectional"))
      (node (ref "X1") (pin "6") (pinfunction "6_6") (pintype "passive"))
      (node (ref "X2") (pin "6") (pinfunction "6_6") (pintype "passive"))
    )
    (net (code "6") (name "/NRST") (class "Default")
      (node (ref "C1") (pin "1") (pinfunction "1_1") (pintype "passive"))
      (node (ref "R5") (pin "2") (pinfunction "2_2") (pintype "passive"))
      (node (ref "S2") (pin "2") (pinfunction "2_2") (pintype "passive"))
      (node (ref "SV1") (pin "5") (pinfunction "5_5") (pintype "passive"))
      (node (ref "SW1") (pin "3") (pinfunction "3_3") (pintype "passive"))
      (node (ref "U1") (pin "7") (pinfunction "NRST_7") (pintype "bidirectional"))
    )
    (net (code "7") (name "/NRST_COM") (class "Default")
      (node (ref "SW1") (pin "8") (pinfunction "8_8") (pintype "passive"))
      (node (ref "X1") (pin "5") (pinfunction "5_5") (pintype "passive"))
      (node (ref "X2") (pin "5") (pinfunction "5_5") (pintype "passive"))
    )
    (net (code "8") (name "/SWA0") (class "Default")
      (node (ref "R7") (pin "2") (pinfunction "2_2") (pintype "passive"))
      (node (ref "U1") (pin "14") (pinfunction "PA0-WKUP_14") (pintype "bidirectional"))
    )
    (net (code "9") (name "/SWA1") (class "Default")
      (node (ref "R8") (pin "2") (pinfunction "2_2") (pintype "passive"))
      (node (ref "U1") (pin "15") (pinfunction "PA1_15") (pintype "bidirectional"))
    )
    (net (code "10") (name "/SWA2") (class "Default")
      (node (ref "R10") (pin "2") (pinfunction "2_2") (pintype "passive"))
      (node (ref "U1") (pin "16") (pinfunction "PA2_16") (pintype "bidirectional"))
    )
    (net (code "11") (name "/SWA3") (class "Default")
      (node (ref "R12") (pin "2") (pinfunction "2_2") (pintype "passive"))
      (node (ref "U1") (pin "17") (pinfunction "PA3_17") (pintype "bidirectional"))
    )
    (net (code "12") (name "/SWA4") (class "Default")
      (node (ref "R14") (pin "2") (pinfunction "2_2") (pintype "passive"))
      (node (ref "U1") (pin "20") (pinfunction "PA4_20") (pintype "bidirectional"))
    )
    (net (code "13") (name "/SWA5") (class "Default")
      (node (ref "R16") (pin "2") (pinfunction "2_2") (pintype "passive"))
      (node (ref "U1") (pin "21") (pinfunction "PA5_21") (pintype "bidirectional"))
    )
    (net (code "14") (name "/SWA6") (class "Default")
      (node (ref "R18") (pin "2") (pinfunction "2_2") (pintype "passive"))
      (node (ref "U1") (pin "22") (pinfunction "PA6_22") (pintype "bidirectional"))
    )
    (net (code "15") (name "/SWA7") (class "Default")
      (node (ref "R20") (pin "2") (pinfunction "2_2") (pintype "passive"))
      (node (ref "U1") (pin "23") (pinfunction "PA7_23") (pintype "bidirectional"))
    )
    (net (code "16") (name "/SWA8") (class "Default")
      (node (ref "R22") (pin "2") (pinfunction "2_2") (pintype "passive"))
      (node (ref "U1") (pin "41") (pinfunction "PA8_41") (pintype "bidirectional"))
    )
    (net (code "17") (name "/SWA11") (class "Default")
      (node (ref "R28") (pin "2") (pinfunction "2_2") (pintype "passive"))
      (node (ref "U1") (pin "44") (pinfunction "PA11_44") (pintype "bidirectional"))
    )
    (net (code "18") (name "/SWA12") (class "Default")
      (node (ref "R30") (pin "2") (pinfunction "2_2") (pintype "passive"))
      (node (ref "U1") (pin "45") (pinfunction "PA12_45") (pintype "bidirectional"))
    )
    (net (code "19") (name "/SWA15") (class "Default")
      (node (ref "R36") (pin "2") (pinfunction "2_2") (pintype "passive"))
      (node (ref "U1") (pin "50") (pinfunction "PA15_50") (pintype "bidirectional"))
    )
    (net (code "20") (name "/SWB0") (class "Default")
      (node (ref "R38") (pin "2") (pinfunction "2_2") (pintype "passive"))
      (node (ref "U1") (pin "26") (pinfunction "PB0_26") (pintype "bidirectional"))
    )
    (net (code "21") (name "/SWB1") (class "Default")
      (node (ref "R40") (pin "2") (pinfunction "2_2") (pintype "passive"))
      (node (ref "U1") (pin "27") (pinfunction "PB1_27") (pintype "bidirectional"))
    )
    (net (code "22") (name "/SWB2") (class "Default")
      (node (ref "R42") (pin "2") (pinfunction "2_2") (pintype "passive"))
      (node (ref "U1") (pin "28") (pinfunction "PB2_28") (pintype "bidirectional"))
    )
    (net (code "23") (name "/SWB3") (class "Default")
      (node (ref "R44") (pin "2") (pinfunction "2_2") (pintype "passive"))
      (node (ref "U1") (pin "55") (pinfunction "PB3_55") (pintype "bidirectional"))
    )
    (net (code "24") (name "/SWB4") (class "Default")
      (node (ref "R46") (pin "2") (pinfunction "2_2") (pintype "passive"))
      (node (ref "U1") (pin "56") (pinfunction "PB4_56") (pintype "bidirectional"))
    )
    (net (code "25") (name "/SWB5") (class "Default")
      (node (ref "R48") (pin "2") (pinfunction "2_2") (pintype "passive"))
      (node (ref "U1") (pin "57") (pinfunction "PB5_57") (pintype "bidirectional"))
    )
    (net (code "26") (name "/SWB8") (class "Default")
      (node (ref "R54") (pin "2") (pinfunction "2_2") (pintype "passive"))
      (node (ref "U1") (pin "61") (pinfunction "PB8_61") (pintype "bidirectional"))
    )
    (net (code "27") (name "/SWB9") (class "Default")
      (node (ref "R56") (pin "2") (pinfunction "2_2") (pintype "passive"))
      (node (ref "U1") (pin "62") (pinfunction "PB9_62") (pintype "bidirectional"))
    )
    (net (code "28") (name "/SWB10") (class "Default")
      (node (ref "R58") (pin "2") (pinfunction "2_2") (pintype "passive"))
      (node (ref "U1") (pin "29") (pinfunction "PB10_29") (pintype "bidirectional"))
    )
    (net (code "29") (name "/SWB11") (class "Default")
      (node (ref "R60") (pin "2") (pinfunction "2_2") (pintype "passive"))
      (node (ref "U1") (pin "30") (pinfunction "PB11_30") (pintype "bidirectional"))
    )
    (net (code "30") (name "/SWB12") (class "Default")
      (node (ref "R62") (pin "2") (pinfunction "2_2") (pintype "passive"))
      (node (ref "U1") (pin "33") (pinfunction "PB12_33") (pintype "bidirectional"))
    )
    (net (code "31") (name "/SWB13") (class "Default")
      (node (ref "R64") (pin "2") (pinfunction "2_2") (pintype "passive"))
      (node (ref "U1") (pin "34") (pinfunction "PB13_34") (pintype "bidirectional"))
    )
    (net (code "32") (name "/SWB14") (class "Default")
      (node (ref "R66") (pin "2") (pinfunction "2_2") (pintype "passive"))
      (node (ref "U1") (pin "35") (pinfunction "PB14_35") (pintype "bidirectional"))
    )
    (net (code "33") (name "/SWB15") (class "Default")
      (node (ref "R68") (pin "2") (pinfunction "2_2") (pintype "passive"))
      (node (ref "U1") (pin "36") (pinfunction "PB15_36") (pintype "bidirectional"))
    )
    (net (code "34") (name "/SWC0") (class "Default")
      (node (ref "R70") (pin "2") (pinfunction "2_2") (pintype "passive"))
      (node (ref "U1") (pin "8") (pinfunction "PC0_8") (pintype "bidirectional"))
    )
    (net (code "35") (name "/SWC1") (class "Default")
      (node (ref "R72") (pin "2") (pinfunction "2_2") (pintype "passive"))
      (node (ref "U1") (pin "9") (pinfunction "PC1_9") (pintype "bidirectional"))
    )
    (net (code "36") (name "/SWC2") (class "Default")
      (node (ref "R74") (pin "2") (pinfunction "2_2") (pintype "passive"))
      (node (ref "U1") (pin "10") (pinfunction "PC2_10") (pintype "bidirectional"))
    )
    (net (code "37") (name "/SWC3") (class "Default")
      (node (ref "R76") (pin "2") (pinfunction "2_2") (pintype "passive"))
      (node (ref "U1") (pin "11") (pinfunction "PC3_11") (pintype "bidirectional"))
    )
    (net (code "38") (name "/SWC4") (class "Default")
      (node (ref "R78") (pin "2") (pinfunction "2_2") (pintype "passive"))
      (node (ref "U1") (pin "24") (pinfunction "PC4_24") (pintype "bidirectional"))
    )
    (net (code "39") (name "/SWC5") (class "Default")
      (node (ref "R80") (pin "2") (pinfunction "2_2") (pintype "passive"))
      (node (ref "U1") (pin "25") (pinfunction "PC5_25") (pintype "bidirectional"))
    )
    (net (code "40") (name "/SWC6") (class "Default")
      (node (ref "R82") (pin "2") (pinfunction "2_2") (pintype "passive"))
      (node (ref "U1") (pin "37") (pinfunction "PC6_37") (pintype "bidirectional"))
    )
    (net (code "41") (name "/SWC7") (class "Default")
      (node (ref "R84") (pin "2") (pinfunction "2_2") (pintype "passive"))
      (node (ref "U1") (pin "38") (pinfunction "PC7_38") (pintype "bidirectional"))
    )
    (net (code "42") (name "/SWC8") (class "Default")
      (node (ref "R86") (pin "2") (pinfunction "2_2") (pintype "passive"))
      (node (ref "U1") (pin "39") (pinfunction "PC8_39") (pintype "bidirectional"))
    )
    (net (code "43") (name "/SWC9") (class "Default")
      (node (ref "R88") (pin "2") (pinfunction "2_2") (pintype "passive"))
      (node (ref "U1") (pin "40") (pinfunction "PC9_40") (pintype "bidirectional"))
    )
    (net (code "44") (name "/SWC10") (class "Default")
      (node (ref "R90") (pin "2") (pinfunction "2_2") (pintype "passive"))
      (node (ref "U1") (pin "51") (pinfunction "PC10_51") (pintype "bidirectional"))
    )
    (net (code "45") (name "/SWC11") (class "Default")
      (node (ref "R92") (pin "2") (pinfunction "2_2") (pintype "passive"))
      (node (ref "U1") (pin "52") (pinfunction "PC11_52") (pintype "bidirectional"))
    )
    (net (code "46") (name "/SWC12") (class "Default")
      (node (ref "R94") (pin "2") (pinfunction "2_2") (pintype "passive"))
      (node (ref "U1") (pin "53") (pinfunction "PC12_53") (pintype "bidirectional"))
    )
    (net (code "47") (name "/SWC13") (class "Default")
      (node (ref "R96") (pin "2") (pinfunction "2_2") (pintype "passive"))
      (node (ref "U1") (pin "2") (pinfunction "PC13-TAMPER-RTC_2") (pintype "bidirectional"))
    )
    (net (code "48") (name "/SWC14") (class "Default")
      (node (ref "R98") (pin "2") (pinfunction "2_2") (pintype "passive"))
      (node (ref "U1") (pin "3") (pinfunction "PC14-OSC32_IN_3") (pintype "bidirectional"))
    )
    (net (code "49") (name "/SWC15") (class "Default")
      (node (ref "R100") (pin "2") (pinfunction "2_2") (pintype "passive"))
      (node (ref "U1") (pin "4") (pinfunction "PC15-OSC32_OUT_4") (pintype "bidirectional"))
    )
    (net (code "50") (name "/SWCLK") (class "Default")
      (node (ref "SV1") (pin "2") (pinfunction "2_2") (pintype "passive"))
      (node (ref "SW1") (pin "5") (pinfunction "5_5") (pintype "passive"))
      (node (ref "U1") (pin "49") (pinfunction "PA14_49") (pintype "bidirectional"))
    )
    (net (code "51") (name "/SWCLK_COM") (class "Default")
      (node (ref "SW1") (pin "6") (pinfunction "6_6") (pintype "passive"))
      (node (ref "X1") (pin "2") (pinfunction "2_2") (pintype "passive"))
      (node (ref "X2") (pin "2") (pinfunction "2_2") (pintype "passive"))
    )
    (net (code "52") (name "/SWDIO") (class "Default")
      (node (ref "SV1") (pin "4") (pinfunction "4_4") (pintype "passive"))
      (node (ref "SW1") (pin "4") (pinfunction "4_4") (pintype "passive"))
      (node (ref "U1") (pin "46") (pinfunction "PA13_46") (pintype "bidirectional"))
    )
    (net (code "53") (name "/SWDIO_COM") (class "Default")
      (node (ref "SW1") (pin "7") (pinfunction "7_7") (pintype "passive"))
      (node (ref "X1") (pin "4") (pinfunction "4_4") (pintype "passive"))
      (node (ref "X2") (pin "4") (pinfunction "4_4") (pintype "passive"))
    )
    (net (code "54") (name "/SWO") (class "Default")
      (node (ref "SV1") (pin "6") (pinfunction "6_6") (pintype "passive"))
    )
    (net (code "55") (name "/UART_RX") (class "Default")
      (node (ref "SV2") (pin "1") (pinfunction "1_1") (pintype "passive"))
      (node (ref "SW1") (pin "2") (pinfunction "2_2") (pintype "passive"))
      (node (ref "U1") (pin "43") (pinfunction "PA10_43") (pintype "bidirectional"))
    )
    (net (code "56") (name "/UART_RX_COM") (class "Default")
      (node (ref "SW1") (pin "9") (pinfunction "9_9") (pintype "passive"))
      (node (ref "X1") (pin "8") (pinfunction "8_8") (pintype "passive"))
      (node (ref "X2") (pin "8") (pinfunction "8_8") (pintype "passive"))
    )
    (net (code "57") (name "/UART_TX") (class "Default")
      (node (ref "SV2") (pin "2") (pinfunction "2_2") (pintype "passive"))
      (node (ref "SW1") (pin "1") (pinfunction "1_1") (pintype "passive"))
      (node (ref "U1") (pin "42") (pinfunction "PA9_42") (pintype "bidirectional"))
    )
    (net (code "58") (name "/UART_TX_COM") (class "Default")
      (node (ref "SW1") (pin "10") (pinfunction "10_10") (pintype "passive"))
      (node (ref "X1") (pin "7") (pinfunction "7_7") (pintype "passive"))
      (node (ref "X2") (pin "7") (pinfunction "7_7") (pintype "passive"))
    )
    (net (code "59") (name "/VCC") (class "Default")
      (node (ref "C10") (pin "1") (pinfunction "1_1") (pintype "passive"))
      (node (ref "C12") (pin "1") (pinfunction "1_1") (pintype "passive"))
      (node (ref "C13") (pin "2") (pinfunction "2_2") (pintype "passive"))
      (node (ref "C4") (pin "1") (pinfunction "1_1") (pintype "passive"))
      (node (ref "C5") (pin "2") (pinfunction "2_2") (pintype "passive"))
      (node (ref "C8") (pin "1") (pinfunction "1_1") (pintype "passive"))
      (node (ref "C9") (pin "1") (pinfunction "1_1") (pintype "passive"))
      (node (ref "IC1") (pin "2") (pinfunction "VOUT_2") (pintype "output"))
      (node (ref "LED4") (pin "A") (pinfunction "A_A") (pintype "passive"))
      (node (ref "R23") (pin "2") (pinfunction "2_2") (pintype "passive"))
      (node (ref "R3") (pin "2") (pinfunction "2_2") (pintype "passive"))
      (node (ref "R5") (pin "1") (pinfunction "1_1") (pintype "passive"))
      (node (ref "SV1") (pin "1") (pinfunction "1_1") (pintype "passive"))
      (node (ref "SV3") (pin "2") (pinfunction "2_2") (pintype "passive"))
      (node (ref "U1") (pin "1") (pinfunction "VBAT_1") (pintype "input"))
      (node (ref "U1") (pin "19") (pinfunction "VDD_4_19") (pintype "power_in"))
      (node (ref "U1") (pin "32") (pinfunction "VDD_1_32") (pintype "power_in"))
      (node (ref "U1") (pin "48") (pinfunction "VDD_2_48") (pintype "power_in"))
      (node (ref "U1") (pin "64") (pinfunction "VDD_3_64") (pintype "power_in"))
    )
    (net (code "60") (name "/VIN") (class "Default")
      (node (ref "C11") (pin "1") (pinfunction "1_1") (pintype "passive"))
      (node (ref "C2") (pin "2") (pinfunction "2_2") (pintype "passive"))
      (node (ref "D1") (pin "C") (pinfunction "C_C") (pintype "passive"))
      (node (ref "D12") (pin "C") (pinfunction "C_C") (pintype "passive"))
      (node (ref "D13") (pin "C") (pinfunction "C_C") (pintype "passive"))
      (node (ref "D16") (pin "C") (pinfunction "C_C") (pintype "passive"))
      (node (ref "D17") (pin "C") (pinfunction "C_C") (pintype "passive"))
      (node (ref "D18") (pin "C") (pinfunction "C_C") (pintype "passive"))
      (node (ref "D19") (pin "C") (pinfunction "C_C") (pintype "passive"))
      (node (ref "D2") (pin "C") (pinfunction "C_C") (pintype "passive"))
      (node (ref "D20") (pin "C") (pinfunction "C_C") (pintype "passive"))
      (node (ref "D21") (pin "C") (pinfunction "C_C") (pintype "passive"))
      (node (ref "D22") (pin "C") (pinfunction "C_C") (pintype "passive"))
      (node (ref "D25") (pin "C") (pinfunction "C_C") (pintype "passive"))
      (node (ref "D26") (pin "C") (pinfunction "C_C") (pintype "passive"))
      (node (ref "D27") (pin "C") (pinfunction "C_C") (pintype "passive"))
      (node (ref "D28") (pin "C") (pinfunction "C_C") (pintype "passive"))
      (node (ref "D29") (pin "C") (pinfunction "C_C") (pintype "passive"))
      (node (ref "D3") (pin "C") (pinfunction "C_C") (pintype "passive"))
      (node (ref "D30") (pin "C") (pinfunction "C_C") (pintype "passive"))
      (node (ref "D31") (pin "C") (pinfunction "C_C") (pintype "passive"))
      (node (ref "D32") (pin "C") (pinfunction "C_C") (pintype "passive"))
      (node (ref "D33") (pin "C") (pinfunction "C_C") (pintype "passive"))
      (node (ref "D34") (pin "C") (pinfunction "C_C") (pintype "passive"))
      (node (ref "D35") (pin "C") (pinfunction "C_C") (pintype "passive"))
      (node (ref "D36") (pin "C") (pinfunction "C_C") (pintype "passive"))
      (node (ref "D37") (pin "C") (pinfunction "C_C") (pintype "passive"))
      (node (ref "D38") (pin "C") (pinfunction "C_C") (pintype "passive"))
      (node (ref "D39") (pin "C") (pinfunction "C_C") (pintype "passive"))
      (node (ref "D4") (pin "C") (pinfunction "C_C") (pintype "passive"))
      (node (ref "D40") (pin "C") (pinfunction "C_C") (pintype "passive"))
      (node (ref "D41") (pin "C") (pinfunction "C_C") (pintype "passive"))
      (node (ref "D42") (pin "C") (pinfunction "C_C") (pintype "passive"))
      (node (ref "D43") (pin "C") (pinfunction "C_C") (pintype "passive"))
      (node (ref "D44") (pin "C") (pinfunction "C_C") (pintype "passive"))
      (node (ref "D45") (pin "C") (pinfunction "C_C") (pintype "passive"))
      (node (ref "D46") (pin "C") (pinfunction "C_C") (pintype "passive"))
      (node (ref "D47") (pin "C") (pinfunction "C_C") (pintype "passive"))
      (node (ref "D48") (pin "C") (pinfunction "C_C") (pintype "passive"))
      (node (ref "D5") (pin "C") (pinfunction "C_C") (pintype "passive"))
      (node (ref "D6") (pin "C") (pinfunction "C_C") (pintype "passive"))
      (node (ref "D7") (pin "C") (pinfunction "C_C") (pintype "passive"))
      (node (ref "D8") (pin "C") (pinfunction "C_C") (pintype "passive"))
      (node (ref "D9") (pin "C") (pinfunction "C_C") (pintype "passive"))
      (node (ref "IC1") (pin "3") (pinfunction "VIN_3") (pintype "input"))
      (node (ref "K1") (pin "1") (pinfunction "1_1") (pintype "passive"))
      (node (ref "K12") (pin "1") (pinfunction "1_1") (pintype "passive"))
      (node (ref "K13") (pin "1") (pinfunction "1_1") (pintype "passive"))
      (node (ref "K16") (pin "1") (pinfunction "1_1") (pintype "passive"))
      (node (ref "K17") (pin "1") (pinfunction "1_1") (pintype "passive"))
      (node (ref "K18") (pin "1") (pinfunction "1_1") (pintype "passive"))
      (node (ref "K19") (pin "1") (pinfunction "1_1") (pintype "passive"))
      (node (ref "K2") (pin "1") (pinfunction "1_1") (pintype "passive"))
      (node (ref "K20") (pin "1") (pinfunction "1_1") (pintype "passive"))
      (node (ref "K21") (pin "1") (pinfunction "1_1") (pintype "passive"))
      (node (ref "K22") (pin "1") (pinfunction "1_1") (pintype "passive"))
      (node (ref "K25") (pin "1") (pinfunction "1_1") (pintype "passive"))
      (node (ref "K26") (pin "1") (pinfunction "1_1") (pintype "passive"))
      (node (ref "K27") (pin "1") (pinfunction "1_1") (pintype "passive"))
      (node (ref "K28") (pin "1") (pinfunction "1_1") (pintype "passive"))
      (node (ref "K29") (pin "1") (pinfunction "1_1") (pintype "passive"))
      (node (ref "K3") (pin "1") (pinfunction "1_1") (pintype "passive"))
      (node (ref "K30") (pin "1") (pinfunction "1_1") (pintype "passive"))
      (node (ref "K31") (pin "1") (pinfunction "1_1") (pintype "passive"))
      (node (ref "K32") (pin "1") (pinfunction "1_1") (pintype "passive"))
      (node (ref "K33") (pin "1") (pinfunction "1_1") (pintype "passive"))
      (node (ref "K34") (pin "1") (pinfunction "1_1") (pintype "passive"))
      (node (ref "K35") (pin "1") (pinfunction "1_1") (pintype "passive"))
      (node (ref "K36") (pin "1") (pinfunction "1_1") (pintype "passive"))
      (node (ref "K37") (pin "1") (pinfunction "1_1") (pintype "passive"))
      (node (ref "K38") (pin "1") (pinfunction "1_1") (pintype "passive"))
      (node (ref "K39") (pin "1") (pinfunction "1_1") (pintype "passive"))
      (node (ref "K4") (pin "1") (pinfunction "1_1") (pintype "passive"))
      (node (ref "K40") (pin "1") (pinfunction "1_1") (pintype "passive"))
      (node (ref "K41") (pin "1") (pinfunction "1_1") (pintype "passive"))
      (node (ref "K42") (pin "1") (pinfunction "1_1") (pintype "passive"))
      (node (ref "K43") (pin "1") (pinfunction "1_1") (pintype "passive"))
      (node (ref "K44") (pin "1") (pinfunction "1_1") (pintype "passive"))
      (node (ref "K45") (pin "1") (pinfunction "1_1") (pintype "passive"))
      (node (ref "K46") (pin "1") (pinfunction "1_1") (pintype "passive"))
      (node (ref "K47") (pin "1") (pinfunction "1_1") (pintype "passive"))
      (node (ref "K48") (pin "1") (pinfunction "1_1") (pintype "passive"))
      (node (ref "K5") (pin "1") (pinfunction "1_1") (pintype "passive"))
      (node (ref "K6") (pin "1") (pinfunction "1_1") (pintype "passive"))
      (node (ref "K7") (pin "1") (pinfunction "1_1") (pintype "passive"))
      (node (ref "K8") (pin "1") (pinfunction "1_1") (pintype "passive"))
      (node (ref "K9") (pin "1") (pinfunction "1_1") (pintype "passive"))
      (node (ref "R11") (pin "2") (pinfunction "2_2") (pintype "passive"))
      (node (ref "R13") (pin "2") (pinfunction "2_2") (pintype "passive"))
      (node (ref "R15") (pin "2") (pinfunction "2_2") (pintype "passive"))
      (node (ref "R17") (pin "2") (pinfunction "2_2") (pintype "passive"))
      (node (ref "R19") (pin "2") (pinfunction "2_2") (pintype "passive"))
      (node (ref "R2") (pin "2") (pinfunction "2_2") (pintype "passive"))
      (node (ref "R21") (pin "2") (pinfunction "2_2") (pintype "passive"))
      (node (ref "R27") (pin "2") (pinfunction "2_2") (pintype "passive"))
      (node (ref "R29") (pin "2") (pinfunction "2_2") (pintype "passive"))
      (node (ref "R35") (pin "2") (pinfunction "2_2") (pintype "passive"))
      (node (ref "R37") (pin "2") (pinfunction "2_2") (pintype "passive"))
      (node (ref "R39") (pin "2") (pinfunction "2_2") (pintype "passive"))
      (node (ref "R41") (pin "2") (pinfunction "2_2") (pintype "passive"))
      (node (ref "R43") (pin "2") (pinfunction "2_2") (pintype "passive"))
      (node (ref "R45") (pin "2") (pinfunction "2_2") (pintype "passive"))
      (node (ref "R47") (pin "2") (pinfunction "2_2") (pintype "passive"))
      (node (ref "R53") (pin "2") (pinfunction "2_2") (pintype "passive"))
      (node (ref "R55") (pin "2") (pinfunction "2_2") (pintype "passive"))
      (node (ref "R57") (pin "2") (pinfunction "2_2") (pintype "passive"))
      (node (ref "R59") (pin "2") (pinfunction "2_2") (pintype "passive"))
      (node (ref "R6") (pin "2") (pinfunction "2_2") (pintype "passive"))
      (node (ref "R61") (pin "2") (pinfunction "2_2") (pintype "passive"))
      (node (ref "R63") (pin "2") (pinfunction "2_2") (pintype "passive"))
      (node (ref "R65") (pin "2") (pinfunction "2_2") (pintype "passive"))
      (node (ref "R67") (pin "2") (pinfunction "2_2") (pintype "passive"))
      (node (ref "R69") (pin "2") (pinfunction "2_2") (pintype "passive"))
      (node (ref "R71") (pin "2") (pinfunction "2_2") (pintype "passive"))
      (node (ref "R73") (pin "2") (pinfunction "2_2") (pintype "passive"))
      (node (ref "R75") (pin "2") (pinfunction "2_2") (pintype "passive"))
      (node (ref "R77") (pin "2") (pinfunction "2_2") (pintype "passive"))
      (node (ref "R79") (pin "2") (pinfunction "2_2") (pintype "passive"))
      (node (ref "R81") (pin "2") (pinfunction "2_2") (pintype "passive"))
      (node (ref "R83") (pin "2") (pinfunction "2_2") (pintype "passive"))
      (node (ref "R85") (pin "2") (pinfunction "2_2") (pintype "passive"))
      (node (ref "R87") (pin "2") (pinfunction "2_2") (pintype "passive"))
      (node (ref "R89") (pin "2") (pinfunction "2_2") (pintype "passive"))
      (node (ref "R9") (pin "2") (pinfunction "2_2") (pintype "passive"))
      (node (ref "R91") (pin "2") (pinfunction "2_2") (pintype "passive"))
      (node (ref "R93") (pin "2") (pinfunction "2_2") (pintype "passive"))
      (node (ref "R95") (pin "2") (pinfunction "2_2") (pintype "passive"))
      (node (ref "R97") (pin "2") (pinfunction "2_2") (pintype "passive"))
      (node (ref "R99") (pin "2") (pinfunction "2_2") (pintype "passive"))
      (node (ref "SV3") (pin "1") (pinfunction "1_1") (pintype "passive"))
      (node (ref "X1") (pin "1") (pinfunction "1_1") (pintype "passive"))
      (node (ref "X2") (pin "1") (pinfunction "1_1") (pintype "passive"))
    )
    (net (code "61") (name "Net-(K1A-2)") (class "Default")
      (node (ref "D2") (pin "A") (pinfunction "A_A") (pintype "passive"))
      (node (ref "K1") (pin "16") (pinfunction "2_16") (pintype "passive"))
      (node (ref "T1") (pin "3") (pinfunction "C_3") (pintype "passive"))
    )
    (net (code "62") (name "Net-(K1B-P)") (class "Default")
      (node (ref "K1") (pin "P1") (pinfunction "P_P1") (pintype "passive"))
      (node (ref "U$41") (pin "P$1") (pinfunction "1_P$1") (pintype "passive"))
    )
    (net (code "63") (name "Net-(K1C-S)") (class "Default")
      (node (ref "K1") (pin "S2") (pinfunction "S_S2") (pintype "passive"))
      (node (ref "LED1") (pin "K") (pinfunction "C_K") (pintype "passive"))
    )
    (net (code "64") (name "Net-(K2A-2)") (class "Default")
      (node (ref "D1") (pin "A") (pinfunction "A_A") (pintype "passive"))
      (node (ref "K2") (pin "16") (pinfunction "2_16") (pintype "passive"))
      (node (ref "T2") (pin "3") (pinfunction "C_3") (pintype "passive"))
    )
    (net (code "65") (name "Net-(K2B-P)") (class "Default")
      (node (ref "K2") (pin "P1") (pinfunction "P_P1") (pintype "passive"))
      (node (ref "U$40") (pin "P$1") (pinfunction "1_P$1") (pintype "passive"))
    )
    (net (code "66") (name "Net-(K2C-S)") (class "Default")
      (node (ref "K2") (pin "S2") (pinfunction "S_S2") (pintype "passive"))
      (node (ref "LED2") (pin "K") (pinfunction "C_K") (pintype "passive"))
    )
    (net (code "67") (name "Net-(K3A-2)") (class "Default")
      (node (ref "D3") (pin "A") (pinfunction "A_A") (pintype "passive"))
      (node (ref "K3") (pin "16") (pinfunction "2_16") (pintype "passive"))
      (node (ref "T3") (pin "3") (pinfunction "C_3") (pintype "passive"))
    )
    (net (code "68") (name "Net-(K3B-P)") (class "Default")
      (node (ref "K3") (pin "P1") (pinfunction "P_P1") (pintype "passive"))
      (node (ref "U$39") (pin "P$1") (pinfunction "1_P$1") (pintype "passive"))
    )
    (net (code "69") (name "Net-(K3C-S)") (class "Default")
      (node (ref "K3") (pin "S2") (pinfunction "S_S2") (pintype "passive"))
      (node (ref "LED5") (pin "K") (pinfunction "C_K") (pintype "passive"))
    )
    (net (code "70") (name "Net-(K4A-2)") (class "Default")
      (node (ref "D4") (pin "A") (pinfunction "A_A") (pintype "passive"))
      (node (ref "K4") (pin "16") (pinfunction "2_16") (pintype "passive"))
      (node (ref "T4") (pin "3") (pinfunction "C_3") (pintype "passive"))
    )
    (net (code "71") (name "Net-(K4B-P)") (class "Default")
      (node (ref "K4") (pin "P1") (pinfunction "P_P1") (pintype "passive"))
      (node (ref "U$38") (pin "P$1") (pinfunction "1_P$1") (pintype "passive"))
    )
    (net (code "72") (name "Net-(K4C-S)") (class "Default")
      (node (ref "K4") (pin "S2") (pinfunction "S_S2") (pintype "passive"))
      (node (ref "LED6") (pin "K") (pinfunction "C_K") (pintype "passive"))
    )
    (net (code "73") (name "Net-(K5A-2)") (class "Default")
      (node (ref "D5") (pin "A") (pinfunction "A_A") (pintype "passive"))
      (node (ref "K5") (pin "16") (pinfunction "2_16") (pintype "passive"))
      (node (ref "T5") (pin "3") (pinfunction "C_3") (pintype "passive"))
    )
    (net (code "74") (name "Net-(K5B-P)") (class "Default")
      (node (ref "K5") (pin "P1") (pinfunction "P_P1") (pintype "passive"))
      (node (ref "U$34") (pin "P$1") (pinfunction "1_P$1") (pintype "passive"))
    )
    (net (code "75") (name "Net-(K5C-S)") (class "Default")
      (node (ref "K5") (pin "S2") (pinfunction "S_S2") (pintype "passive"))
      (node (ref "LED7") (pin "K") (pinfunction "C_K") (pintype "passive"))
    )
    (net (code "76") (name "Net-(K6A-2)") (class "Default")
      (node (ref "D6") (pin "A") (pinfunction "A_A") (pintype "passive"))
      (node (ref "K6") (pin "16") (pinfunction "2_16") (pintype "passive"))
      (node (ref "T6") (pin "3") (pinfunction "C_3") (pintype "passive"))
    )
    (net (code "77") (name "Net-(K6B-P)") (class "Default")
      (node (ref "K6") (pin "P1") (pinfunction "P_P1") (pintype "passive"))
      (node (ref "U$35") (pin "P$1") (pinfunction "1_P$1") (pintype "passive"))
    )
    (net (code "78") (name "Net-(K6C-S)") (class "Default")
      (node (ref "K6") (pin "S2") (pinfunction "S_S2") (pintype "passive"))
      (node (ref "LED8") (pin "K") (pinfunction "C_K") (pintype "passive"))
    )
    (net (code "79") (name "Net-(K7A-2)") (class "Default")
      (node (ref "D7") (pin "A") (pinfunction "A_A") (pintype "passive"))
      (node (ref "K7") (pin "16") (pinfunction "2_16") (pintype "passive"))
      (node (ref "T7") (pin "3") (pinfunction "C_3") (pintype "passive"))
    )
    (net (code "80") (name "Net-(K7B-P)") (class "Default")
      (node (ref "K7") (pin "P1") (pinfunction "P_P1") (pintype "passive"))
      (node (ref "U$36") (pin "P$1") (pinfunction "1_P$1") (pintype "passive"))
    )
    (net (code "81") (name "Net-(K7C-S)") (class "Default")
      (node (ref "K7") (pin "S2") (pinfunction "S_S2") (pintype "passive"))
      (node (ref "LED9") (pin "K") (pinfunction "C_K") (pintype "passive"))
    )
    (net (code "82") (name "Net-(K8A-2)") (class "Default")
      (node (ref "D8") (pin "A") (pinfunction "A_A") (pintype "passive"))
      (node (ref "K8") (pin "16") (pinfunction "2_16") (pintype "passive"))
      (node (ref "T8") (pin "3") (pinfunction "C_3") (pintype "passive"))
    )
    (net (code "83") (name "Net-(K8B-P)") (class "Default")
      (node (ref "K8") (pin "P1") (pinfunction "P_P1") (pintype "passive"))
      (node (ref "U$37") (pin "P$1") (pinfunction "1_P$1") (pintype "passive"))
    )
    (net (code "84") (name "Net-(K8C-S)") (class "Default")
      (node (ref "K8") (pin "S2") (pinfunction "S_S2") (pintype "passive"))
      (node (ref "LED10") (pin "K") (pinfunction "C_K") (pintype "passive"))
    )
    (net (code "85") (name "Net-(K9A-2)") (class "Default")
      (node (ref "D9") (pin "A") (pinfunction "A_A") (pintype "passive"))
      (node (ref "K9") (pin "16") (pinfunction "2_16") (pintype "passive"))
      (node (ref "T9") (pin "3") (pinfunction "C_3") (pintype "passive"))
    )
    (net (code "86") (name "Net-(K9B-P)") (class "Default")
      (node (ref "K9") (pin "P1") (pinfunction "P_P1") (pintype "passive"))
      (node (ref "U$33") (pin "P$1") (pinfunction "1_P$1") (pintype "passive"))
    )
    (net (code "87") (name "Net-(K9C-S)") (class "Default")
      (node (ref "K9") (pin "S2") (pinfunction "S_S2") (pintype "passive"))
      (node (ref "LED11") (pin "K") (pinfunction "C_K") (pintype "passive"))
    )
    (net (code "88") (name "Net-(K12A-2)") (class "Default")
      (node (ref "D12") (pin "A") (pinfunction "A_A") (pintype "passive"))
      (node (ref "K12") (pin "16") (pinfunction "2_16") (pintype "passive"))
      (node (ref "T12") (pin "3") (pinfunction "C_3") (pintype "passive"))
    )
    (net (code "89") (name "Net-(K12B-P)") (class "Default")
      (node (ref "K12") (pin "P1") (pinfunction "P_P1") (pintype "passive"))
      (node (ref "U$44") (pin "P$1") (pinfunction "1_P$1") (pintype "passive"))
    )
    (net (code "90") (name "Net-(K12C-S)") (class "Default")
      (node (ref "K12") (pin "S2") (pinfunction "S_S2") (pintype "passive"))
      (node (ref "LED14") (pin "K") (pinfunction "C_K") (pintype "passive"))
    )
    (net (code "91") (name "Net-(K13A-2)") (class "Default")
      (node (ref "D13") (pin "A") (pinfunction "A_A") (pintype "passive"))
      (node (ref "K13") (pin "16") (pinfunction "2_16") (pintype "passive"))
      (node (ref "T13") (pin "3") (pinfunction "C_3") (pintype "passive"))
    )
    (net (code "92") (name "Net-(K13B-P)") (class "Default")
      (node (ref "K13") (pin "P1") (pinfunction "P_P1") (pintype "passive"))
      (node (ref "U$32") (pin "P$1") (pinfunction "1_P$1") (pintype "passive"))
    )
    (net (code "93") (name "Net-(K13C-S)") (class "Default")
      (node (ref "K13") (pin "S2") (pinfunction "S_S2") (pintype "passive"))
      (node (ref "LED15") (pin "K") (pinfunction "C_K") (pintype "passive"))
    )
    (net (code "94") (name "Net-(K16A-2)") (class "Default")
      (node (ref "D16") (pin "A") (pinfunction "A_A") (pintype "passive"))
      (node (ref "K16") (pin "16") (pinfunction "2_16") (pintype "passive"))
      (node (ref "T16") (pin "3") (pinfunction "C_3") (pintype "passive"))
    )
    (net (code "95") (name "Net-(K16B-P)") (class "Default")
      (node (ref "K16") (pin "P1") (pinfunction "P_P1") (pintype "passive"))
      (node (ref "U$31") (pin "P$1") (pinfunction "1_P$1") (pintype "passive"))
    )
    (net (code "96") (name "Net-(K16C-S)") (class "Default")
      (node (ref "K16") (pin "S2") (pinfunction "S_S2") (pintype "passive"))
      (node (ref "LED18") (pin "K") (pinfunction "C_K") (pintype "passive"))
    )
    (net (code "97") (name "Net-(K17A-2)") (class "Default")
      (node (ref "D17") (pin "A") (pinfunction "A_A") (pintype "passive"))
      (node (ref "K17") (pin "16") (pinfunction "2_16") (pintype "passive"))
      (node (ref "T17") (pin "3") (pinfunction "C_3") (pintype "passive"))
    )
    (net (code "98") (name "Net-(K17B-P)") (class "Default")
      (node (ref "K17") (pin "P1") (pinfunction "P_P1") (pintype "passive"))
      (node (ref "U$27") (pin "P$1") (pinfunction "1_P$1") (pintype "passive"))
    )
    (net (code "99") (name "Net-(K17C-S)") (class "Default")
      (node (ref "K17") (pin "S2") (pinfunction "S_S2") (pintype "passive"))
      (node (ref "LED19") (pin "K") (pinfunction "C_K") (pintype "passive"))
    )
    (net (code "100") (name "Net-(K18A-2)") (class "Default")
      (node (ref "D18") (pin "A") (pinfunction "A_A") (pintype "passive"))
      (node (ref "K18") (pin "16") (pinfunction "2_16") (pintype "passive"))
      (node (ref "T18") (pin "3") (pinfunction "C_3") (pintype "passive"))
    )
    (net (code "101") (name "Net-(K18B-P)") (class "Default")
      (node (ref "K18") (pin "P1") (pinfunction "P_P1") (pintype "passive"))
      (node (ref "U$28") (pin "P$1") (pinfunction "1_P$1") (pintype "passive"))
    )
    (net (code "102") (name "Net-(K18C-S)") (class "Default")
      (node (ref "K18") (pin "S2") (pinfunction "S_S2") (pintype "passive"))
      (node (ref "LED20") (pin "K") (pinfunction "C_K") (pintype "passive"))
    )
    (net (code "103") (name "Net-(K19A-2)") (class "Default")
      (node (ref "D19") (pin "A") (pinfunction "A_A") (pintype "passive"))
      (node (ref "K19") (pin "16") (pinfunction "2_16") (pintype "passive"))
      (node (ref "T19") (pin "3") (pinfunction "C_3") (pintype "passive"))
    )
    (net (code "104") (name "Net-(K19B-P)") (class "Default")
      (node (ref "K19") (pin "P1") (pinfunction "P_P1") (pintype "passive"))
      (node (ref "U$29") (pin "P$1") (pinfunction "1_P$1") (pintype "passive"))
    )
    (net (code "105") (name "Net-(K19C-S)") (class "Default")
      (node (ref "K19") (pin "S2") (pinfunction "S_S2") (pintype "passive"))
      (node (ref "LED21") (pin "K") (pinfunction "C_K") (pintype "passive"))
    )
    (net (code "106") (name "Net-(K20A-2)") (class "Default")
      (node (ref "D20") (pin "A") (pinfunction "A_A") (pintype "passive"))
      (node (ref "K20") (pin "16") (pinfunction "2_16") (pintype "passive"))
      (node (ref "T20") (pin "3") (pinfunction "C_3") (pintype "passive"))
    )
    (net (code "107") (name "Net-(K20B-P)") (class "Default")
      (node (ref "K20") (pin "P1") (pinfunction "P_P1") (pintype "passive"))
      (node (ref "U$30") (pin "P$1") (pinfunction "1_P$1") (pintype "passive"))
    )
    (net (code "108") (name "Net-(K20C-S)") (class "Default")
      (node (ref "K20") (pin "S2") (pinfunction "S_S2") (pintype "passive"))
      (node (ref "LED22") (pin "K") (pinfunction "C_K") (pintype "passive"))
    )
    (net (code "109") (name "Net-(K21A-2)") (class "Default")
      (node (ref "D21") (pin "A") (pinfunction "A_A") (pintype "passive"))
      (node (ref "K21") (pin "16") (pinfunction "2_16") (pintype "passive"))
      (node (ref "T21") (pin "3") (pinfunction "C_3") (pintype "passive"))
    )
    (net (code "110") (name "Net-(K21B-P)") (class "Default")
      (node (ref "K21") (pin "P1") (pinfunction "P_P1") (pintype "passive"))
      (node (ref "U$26") (pin "P$1") (pinfunction "1_P$1") (pintype "passive"))
    )
    (net (code "111") (name "Net-(K21C-S)") (class "Default")
      (node (ref "K21") (pin "S2") (pinfunction "S_S2") (pintype "passive"))
      (node (ref "LED23") (pin "K") (pinfunction "C_K") (pintype "passive"))
    )
    (net (code "112") (name "Net-(K22A-2)") (class "Default")
      (node (ref "D22") (pin "A") (pinfunction "A_A") (pintype "passive"))
      (node (ref "K22") (pin "16") (pinfunction "2_16") (pintype "passive"))
      (node (ref "T22") (pin "3") (pinfunction "C_3") (pintype "passive"))
    )
    (net (code "113") (name "Net-(K22B-P)") (class "Default")
      (node (ref "K22") (pin "P1") (pinfunction "P_P1") (pintype "passive"))
      (node (ref "U$25") (pin "P$1") (pinfunction "1_P$1") (pintype "passive"))
    )
    (net (code "114") (name "Net-(K22C-S)") (class "Default")
      (node (ref "K22") (pin "S2") (pinfunction "S_S2") (pintype "passive"))
      (node (ref "LED24") (pin "K") (pinfunction "C_K") (pintype "passive"))
    )
    (net (code "115") (name "Net-(K25A-2)") (class "Default")
      (node (ref "D25") (pin "A") (pinfunction "A_A") (pintype "passive"))
      (node (ref "K25") (pin "16") (pinfunction "2_16") (pintype "passive"))
      (node (ref "T25") (pin "3") (pinfunction "C_3") (pintype "passive"))
    )
    (net (code "116") (name "Net-(K25B-P)") (class "Default")
      (node (ref "K25") (pin "P1") (pinfunction "P_P1") (pintype "passive"))
      (node (ref "U$18") (pin "P$1") (pinfunction "1_P$1") (pintype "passive"))
    )
    (net (code "117") (name "Net-(K25C-S)") (class "Default")
      (node (ref "K25") (pin "S2") (pinfunction "S_S2") (pintype "passive"))
      (node (ref "LED27") (pin "K") (pinfunction "C_K") (pintype "passive"))
    )
    (net (code "118") (name "Net-(K26A-2)") (class "Default")
      (node (ref "D26") (pin "A") (pinfunction "A_A") (pintype "passive"))
      (node (ref "K26") (pin "16") (pinfunction "2_16") (pintype "passive"))
      (node (ref "T26") (pin "3") (pinfunction "C_3") (pintype "passive"))
    )
    (net (code "119") (name "Net-(K26B-P)") (class "Default")
      (node (ref "K26") (pin "P1") (pinfunction "P_P1") (pintype "passive"))
      (node (ref "U$20") (pin "P$1") (pinfunction "1_P$1") (pintype "passive"))
    )
    (net (code "120") (name "Net-(K26C-S)") (class "Default")
      (node (ref "K26") (pin "S2") (pinfunction "S_S2") (pintype "passive"))
      (node (ref "LED28") (pin "K") (pinfunction "C_K") (pintype "passive"))
    )
    (net (code "121") (name "Net-(K27A-2)") (class "Default")
      (node (ref "D27") (pin "A") (pinfunction "A_A") (pintype "passive"))
      (node (ref "K27") (pin "16") (pinfunction "2_16") (pintype "passive"))
      (node (ref "T27") (pin "3") (pinfunction "C_3") (pintype "passive"))
    )
    (net (code "122") (name "Net-(K27B-P)") (class "Default")
      (node (ref "K27") (pin "P1") (pinfunction "P_P1") (pintype "passive"))
      (node (ref "U$22") (pin "P$1") (pinfunction "1_P$1") (pintype "passive"))
    )
    (net (code "123") (name "Net-(K27C-S)") (class "Default")
      (node (ref "K27") (pin "S2") (pinfunction "S_S2") (pintype "passive"))
      (node (ref "LED29") (pin "K") (pinfunction "C_K") (pintype "passive"))
    )
    (net (code "124") (name "Net-(K28A-2)") (class "Default")
      (node (ref "D28") (pin "A") (pinfunction "A_A") (pintype "passive"))
      (node (ref "K28") (pin "16") (pinfunction "2_16") (pintype "passive"))
      (node (ref "T28") (pin "3") (pinfunction "C_3") (pintype "passive"))
    )
    (net (code "125") (name "Net-(K28B-P)") (class "Default")
      (node (ref "K28") (pin "P1") (pinfunction "P_P1") (pintype "passive"))
      (node (ref "U$24") (pin "P$1") (pinfunction "1_P$1") (pintype "passive"))
    )
    (net (code "126") (name "Net-(K28C-S)") (class "Default")
      (node (ref "K28") (pin "S2") (pinfunction "S_S2") (pintype "passive"))
      (node (ref "LED30") (pin "K") (pinfunction "C_K") (pintype "passive"))
    )
    (net (code "127") (name "Net-(K29A-2)") (class "Default")
      (node (ref "D29") (pin "A") (pinfunction "A_A") (pintype "passive"))
      (node (ref "K29") (pin "16") (pinfunction "2_16") (pintype "passive"))
      (node (ref "T29") (pin "3") (pinfunction "C_3") (pintype "passive"))
    )
    (net (code "128") (name "Net-(K29B-P)") (class "Default")
      (node (ref "K29") (pin "P1") (pinfunction "P_P1") (pintype "passive"))
      (node (ref "U$17") (pin "P$1") (pinfunction "1_P$1") (pintype "passive"))
    )
    (net (code "129") (name "Net-(K29C-S)") (class "Default")
      (node (ref "K29") (pin "S2") (pinfunction "S_S2") (pintype "passive"))
      (node (ref "LED31") (pin "K") (pinfunction "C_K") (pintype "passive"))
    )
    (net (code "130") (name "Net-(K30A-2)") (class "Default")
      (node (ref "D30") (pin "A") (pinfunction "A_A") (pintype "passive"))
      (node (ref "K30") (pin "16") (pinfunction "2_16") (pintype "passive"))
      (node (ref "T30") (pin "3") (pinfunction "C_3") (pintype "passive"))
    )
    (net (code "131") (name "Net-(K30B-P)") (class "Default")
      (node (ref "K30") (pin "P1") (pinfunction "P_P1") (pintype "passive"))
      (node (ref "U$19") (pin "P$1") (pinfunction "1_P$1") (pintype "passive"))
    )
    (net (code "132") (name "Net-(K30C-S)") (class "Default")
      (node (ref "K30") (pin "S2") (pinfunction "S_S2") (pintype "passive"))
      (node (ref "LED32") (pin "K") (pinfunction "C_K") (pintype "passive"))
    )
    (net (code "133") (name "Net-(K31A-2)") (class "Default")
      (node (ref "D31") (pin "A") (pinfunction "A_A") (pintype "passive"))
      (node (ref "K31") (pin "16") (pinfunction "2_16") (pintype "passive"))
      (node (ref "T31") (pin "3") (pinfunction "C_3") (pintype "passive"))
    )
    (net (code "134") (name "Net-(K31B-P)") (class "Default")
      (node (ref "K31") (pin "P1") (pinfunction "P_P1") (pintype "passive"))
      (node (ref "U$21") (pin "P$1") (pinfunction "1_P$1") (pintype "passive"))
    )
    (net (code "135") (name "Net-(K31C-S)") (class "Default")
      (node (ref "K31") (pin "S2") (pinfunction "S_S2") (pintype "passive"))
      (node (ref "LED33") (pin "K") (pinfunction "C_K") (pintype "passive"))
    )
    (net (code "136") (name "Net-(K32A-2)") (class "Default")
      (node (ref "D32") (pin "A") (pinfunction "A_A") (pintype "passive"))
      (node (ref "K32") (pin "16") (pinfunction "2_16") (pintype "passive"))
      (node (ref "T32") (pin "3") (pinfunction "C_3") (pintype "passive"))
    )
    (net (code "137") (name "Net-(K32B-P)") (class "Default")
      (node (ref "K32") (pin "P1") (pinfunction "P_P1") (pintype "passive"))
      (node (ref "U$23") (pin "P$1") (pinfunction "1_P$1") (pintype "passive"))
    )
    (net (code "138") (name "Net-(K32C-S)") (class "Default")
      (node (ref "K32") (pin "S2") (pinfunction "S_S2") (pintype "passive"))
      (node (ref "LED34") (pin "K") (pinfunction "C_K") (pintype "passive"))
    )
    (net (code "139") (name "Net-(K33A-2)") (class "Default")
      (node (ref "D33") (pin "A") (pinfunction "A_A") (pintype "passive"))
      (node (ref "K33") (pin "16") (pinfunction "2_16") (pintype "passive"))
      (node (ref "T33") (pin "3") (pinfunction "C_3") (pintype "passive"))
    )
    (net (code "140") (name "Net-(K33B-P)") (class "Default")
      (node (ref "K33") (pin "P1") (pinfunction "P_P1") (pintype "passive"))
      (node (ref "U$1") (pin "P$1") (pinfunction "1_P$1") (pintype "passive"))
    )
    (net (code "141") (name "Net-(K33C-S)") (class "Default")
      (node (ref "K33") (pin "S2") (pinfunction "S_S2") (pintype "passive"))
      (node (ref "LED35") (pin "K") (pinfunction "C_K") (pintype "passive"))
    )
    (net (code "142") (name "Net-(K34A-2)") (class "Default")
      (node (ref "D34") (pin "A") (pinfunction "A_A") (pintype "passive"))
      (node (ref "K34") (pin "16") (pinfunction "2_16") (pintype "passive"))
      (node (ref "T34") (pin "3") (pinfunction "C_3") (pintype "passive"))
    )
    (net (code "143") (name "Net-(K34B-P)") (class "Default")
      (node (ref "K34") (pin "P1") (pinfunction "P_P1") (pintype "passive"))
      (node (ref "U$2") (pin "P$1") (pinfunction "1_P$1") (pintype "passive"))
    )
    (net (code "144") (name "Net-(K34C-S)") (class "Default")
      (node (ref "K34") (pin "S2") (pinfunction "S_S2") (pintype "passive"))
      (node (ref "LED36") (pin "K") (pinfunction "C_K") (pintype "passive"))
    )
    (net (code "145") (name "Net-(K35A-2)") (class "Default")
      (node (ref "D35") (pin "A") (pinfunction "A_A") (pintype "passive"))
      (node (ref "K35") (pin "16") (pinfunction "2_16") (pintype "passive"))
      (node (ref "T35") (pin "3") (pinfunction "C_3") (pintype "passive"))
    )
    (net (code "146") (name "Net-(K35B-P)") (class "Default")
      (node (ref "K35") (pin "P1") (pinfunction "P_P1") (pintype "passive"))
      (node (ref "U$3") (pin "P$1") (pinfunction "1_P$1") (pintype "passive"))
    )
    (net (code "147") (name "Net-(K35C-S)") (class "Default")
      (node (ref "K35") (pin "S2") (pinfunction "S_S2") (pintype "passive"))
      (node (ref "LED37") (pin "K") (pinfunction "C_K") (pintype "passive"))
    )
    (net (code "148") (name "Net-(K36A-2)") (class "Default")
      (node (ref "D36") (pin "A") (pinfunction "A_A") (pintype "passive"))
      (node (ref "K36") (pin "16") (pinfunction "2_16") (pintype "passive"))
      (node (ref "T36") (pin "3") (pinfunction "C_3") (pintype "passive"))
    )
    (net (code "149") (name "Net-(K36B-P)") (class "Default")
      (node (ref "K36") (pin "P1") (pinfunction "P_P1") (pintype "passive"))
      (node (ref "U$4") (pin "P$1") (pinfunction "1_P$1") (pintype "passive"))
    )
    (net (code "150") (name "Net-(K36C-S)") (class "Default")
      (node (ref "K36") (pin "S2") (pinfunction "S_S2") (pintype "passive"))
      (node (ref "LED38") (pin "K") (pinfunction "C_K") (pintype "passive"))
    )
    (net (code "151") (name "Net-(K37A-2)") (class "Default")
      (node (ref "D37") (pin "A") (pinfunction "A_A") (pintype "passive"))
      (node (ref "K37") (pin "16") (pinfunction "2_16") (pintype "passive"))
      (node (ref "T37") (pin "3") (pinfunction "C_3") (pintype "passive"))
    )
    (net (code "152") (name "Net-(K37B-P)") (class "Default")
      (node (ref "K37") (pin "P1") (pinfunction "P_P1") (pintype "passive"))
      (node (ref "U$8") (pin "P$1") (pinfunction "1_P$1") (pintype "passive"))
    )
    (net (code "153") (name "Net-(K37C-S)") (class "Default")
      (node (ref "K37") (pin "S2") (pinfunction "S_S2") (pintype "passive"))
      (node (ref "LED39") (pin "K") (pinfunction "C_K") (pintype "passive"))
    )
    (net (code "154") (name "Net-(K38A-2)") (class "Default")
      (node (ref "D38") (pin "A") (pinfunction "A_A") (pintype "passive"))
      (node (ref "K38") (pin "16") (pinfunction "2_16") (pintype "passive"))
      (node (ref "T38") (pin "3") (pinfunction "C_3") (pintype "passive"))
    )
    (net (code "155") (name "Net-(K38B-P)") (class "Default")
      (node (ref "K38") (pin "P1") (pinfunction "P_P1") (pintype "passive"))
      (node (ref "U$7") (pin "P$1") (pinfunction "1_P$1") (pintype "passive"))
    )
    (net (code "156") (name "Net-(K38C-S)") (class "Default")
      (node (ref "K38") (pin "S2") (pinfunction "S_S2") (pintype "passive"))
      (node (ref "LED40") (pin "K") (pinfunction "C_K") (pintype "passive"))
    )
    (net (code "157") (name "Net-(K39A-2)") (class "Default")
      (node (ref "D39") (pin "A") (pinfunction "A_A") (pintype "passive"))
      (node (ref "K39") (pin "16") (pinfunction "2_16") (pintype "passive"))
      (node (ref "T39") (pin "3") (pinfunction "C_3") (pintype "passive"))
    )
    (net (code "158") (name "Net-(K39B-P)") (class "Default")
      (node (ref "K39") (pin "P1") (pinfunction "P_P1") (pintype "passive"))
      (node (ref "U$6") (pin "P$1") (pinfunction "1_P$1") (pintype "passive"))
    )
    (net (code "159") (name "Net-(K39C-S)") (class "Default")
      (node (ref "K39") (pin "S2") (pinfunction "S_S2") (pintype "passive"))
      (node (ref "LED41") (pin "K") (pinfunction "C_K") (pintype "passive"))
    )
    (net (code "160") (name "Net-(K40A-2)") (class "Default")
      (node (ref "D40") (pin "A") (pinfunction "A_A") (pintype "passive"))
      (node (ref "K40") (pin "16") (pinfunction "2_16") (pintype "passive"))
      (node (ref "T40") (pin "3") (pinfunction "C_3") (pintype "passive"))
    )
    (net (code "161") (name "Net-(K40B-P)") (class "Default")
      (node (ref "K40") (pin "P1") (pinfunction "P_P1") (pintype "passive"))
      (node (ref "U$5") (pin "P$1") (pinfunction "1_P$1") (pintype "passive"))
    )
    (net (code "162") (name "Net-(K40C-S)") (class "Default")
      (node (ref "K40") (pin "S2") (pinfunction "S_S2") (pintype "passive"))
      (node (ref "LED42") (pin "K") (pinfunction "C_K") (pintype "passive"))
    )
    (net (code "163") (name "Net-(K41A-2)") (class "Default")
      (node (ref "D41") (pin "A") (pinfunction "A_A") (pintype "passive"))
      (node (ref "K41") (pin "16") (pinfunction "2_16") (pintype "passive"))
      (node (ref "T41") (pin "3") (pinfunction "C_3") (pintype "passive"))
    )
    (net (code "164") (name "Net-(K41B-P)") (class "Default")
      (node (ref "K41") (pin "P1") (pinfunction "P_P1") (pintype "passive"))
      (node (ref "U$9") (pin "P$1") (pinfunction "1_P$1") (pintype "passive"))
    )
    (net (code "165") (name "Net-(K41C-S)") (class "Default")
      (node (ref "K41") (pin "S2") (pinfunction "S_S2") (pintype "passive"))
      (node (ref "LED43") (pin "K") (pinfunction "C_K") (pintype "passive"))
    )
    (net (code "166") (name "Net-(K42A-2)") (class "Default")
      (node (ref "D42") (pin "A") (pinfunction "A_A") (pintype "passive"))
      (node (ref "K42") (pin "16") (pinfunction "2_16") (pintype "passive"))
      (node (ref "T42") (pin "3") (pinfunction "C_3") (pintype "passive"))
    )
    (net (code "167") (name "Net-(K42B-P)") (class "Default")
      (node (ref "K42") (pin "P1") (pinfunction "P_P1") (pintype "passive"))
      (node (ref "U$10") (pin "P$1") (pinfunction "1_P$1") (pintype "passive"))
    )
    (net (code "168") (name "Net-(K42C-S)") (class "Default")
      (node (ref "K42") (pin "S2") (pinfunction "S_S2") (pintype "passive"))
      (node (ref "LED44") (pin "K") (pinfunction "C_K") (pintype "passive"))
    )
    (net (code "169") (name "Net-(K43A-2)") (class "Default")
      (node (ref "D43") (pin "A") (pinfunction "A_A") (pintype "passive"))
      (node (ref "K43") (pin "16") (pinfunction "2_16") (pintype "passive"))
      (node (ref "T43") (pin "3") (pinfunction "C_3") (pintype "passive"))
    )
    (net (code "170") (name "Net-(K43B-P)") (class "Default")
      (node (ref "K43") (pin "P1") (pinfunction "P_P1") (pintype "passive"))
      (node (ref "U$11") (pin "P$1") (pinfunction "1_P$1") (pintype "passive"))
    )
    (net (code "171") (name "Net-(K43C-S)") (class "Default")
      (node (ref "K43") (pin "S2") (pinfunction "S_S2") (pintype "passive"))
      (node (ref "LED45") (pin "K") (pinfunction "C_K") (pintype "passive"))
    )
    (net (code "172") (name "Net-(K44A-2)") (class "Default")
      (node (ref "D44") (pin "A") (pinfunction "A_A") (pintype "passive"))
      (node (ref "K44") (pin "16") (pinfunction "2_16") (pintype "passive"))
      (node (ref "T44") (pin "3") (pinfunction "C_3") (pintype "passive"))
    )
    (net (code "173") (name "Net-(K44B-P)") (class "Default")
      (node (ref "K44") (pin "P1") (pinfunction "P_P1") (pintype "passive"))
      (node (ref "U$12") (pin "P$1") (pinfunction "1_P$1") (pintype "passive"))
    )
    (net (code "174") (name "Net-(K44C-S)") (class "Default")
      (node (ref "K44") (pin "S2") (pinfunction "S_S2") (pintype "passive"))
      (node (ref "LED46") (pin "K") (pinfunction "C_K") (pintype "passive"))
    )
    (net (code "175") (name "Net-(K45A-2)") (class "Default")
      (node (ref "D45") (pin "A") (pinfunction "A_A") (pintype "passive"))
      (node (ref "K45") (pin "16") (pinfunction "2_16") (pintype "passive"))
      (node (ref "T45") (pin "3") (pinfunction "C_3") (pintype "passive"))
    )
    (net (code "176") (name "Net-(K45B-P)") (class "Default")
      (node (ref "K45") (pin "P1") (pinfunction "P_P1") (pintype "passive"))
      (node (ref "U$13") (pin "P$1") (pinfunction "1_P$1") (pintype "passive"))
    )
    (net (code "177") (name "Net-(K45C-S)") (class "Default")
      (node (ref "K45") (pin "S2") (pinfunction "S_S2") (pintype "passive"))
      (node (ref "LED47") (pin "K") (pinfunction "C_K") (pintype "passive"))
    )
    (net (code "178") (name "Net-(K46A-2)") (class "Default")
      (node (ref "D46") (pin "A") (pinfunction "A_A") (pintype "passive"))
      (node (ref "K46") (pin "16") (pinfunction "2_16") (pintype "passive"))
      (node (ref "T46") (pin "3") (pinfunction "C_3") (pintype "passive"))
    )
    (net (code "179") (name "Net-(K46B-P)") (class "Default")
      (node (ref "K46") (pin "P1") (pinfunction "P_P1") (pintype "passive"))
      (node (ref "U$14") (pin "P$1") (pinfunction "1_P$1") (pintype "passive"))
    )
    (net (code "180") (name "Net-(K46C-S)") (class "Default")
      (node (ref "K46") (pin "S2") (pinfunction "S_S2") (pintype "passive"))
      (node (ref "LED48") (pin "K") (pinfunction "C_K") (pintype "passive"))
    )
    (net (code "181") (name "Net-(K47A-2)") (class "Default")
      (node (ref "D47") (pin "A") (pinfunction "A_A") (pintype "passive"))
      (node (ref "K47") (pin "16") (pinfunction "2_16") (pintype "passive"))
      (node (ref "T47") (pin "3") (pinfunction "C_3") (pintype "passive"))
    )
    (net (code "182") (name "Net-(K47B-P)") (class "Default")
      (node (ref "K47") (pin "P1") (pinfunction "P_P1") (pintype "passive"))
      (node (ref "U$15") (pin "P$1") (pinfunction "1_P$1") (pintype "passive"))
    )
    (net (code "183") (name "Net-(K47C-S)") (class "Default")
      (node (ref "K47") (pin "S2") (pinfunction "S_S2") (pintype "passive"))
      (node (ref "LED49") (pin "K") (pinfunction "C_K") (pintype "passive"))
    )
    (net (code "184") (name "Net-(K48A-2)") (class "Default")
      (node (ref "D48") (pin "A") (pinfunction "A_A") (pintype "passive"))
      (node (ref "K48") (pin "16") (pinfunction "2_16") (pintype "passive"))
      (node (ref "T48") (pin "3") (pinfunction "C_3") (pintype "passive"))
    )
    (net (code "185") (name "Net-(K48B-P)") (class "Default")
      (node (ref "K48") (pin "P1") (pinfunction "P_P1") (pintype "passive"))
      (node (ref "U$16") (pin "P$1") (pinfunction "1_P$1") (pintype "passive"))
    )
    (net (code "186") (name "Net-(K48C-S)") (class "Default")
      (node (ref "K48") (pin "S2") (pinfunction "S_S2") (pintype "passive"))
      (node (ref "LED50") (pin "K") (pinfunction "C_K") (pintype "passive"))
    )
    (net (code "187") (name "Net-(LED1-PadA)") (class "Default")
      (node (ref "LED1") (pin "A") (pinfunction "A_A") (pintype "passive"))
      (node (ref "R2") (pin "1") (pinfunction "1_1") (pintype "passive"))
    )
    (net (code "188") (name "Net-(LED2-PadA)") (class "Default")
      (node (ref "LED2") (pin "A") (pinfunction "A_A") (pintype "passive"))
      (node (ref "R6") (pin "1") (pinfunction "1_1") (pintype "passive"))
    )
    (net (code "189") (name "Net-(LED3-PadA)") (class "Default")
      (node (ref "LED3") (pin "A") (pinfunction "A_A") (pintype "passive"))
      (node (ref "R3") (pin "1") (pinfunction "1_1") (pintype "passive"))
    )
    (net (code "190") (name "Net-(LED4-PadC)") (class "Default")
      (node (ref "LED4") (pin "C") (pinfunction "C_C") (pintype "passive"))
      (node (ref "R4") (pin "2") (pinfunction "2_2") (pintype "passive"))
    )
    (net (code "191") (name "Net-(LED5-PadA)") (class "Default")
      (node (ref "LED5") (pin "A") (pinfunction "A_A") (pintype "passive"))
      (node (ref "R9") (pin "1") (pinfunction "1_1") (pintype "passive"))
    )
    (net (code "192") (name "Net-(LED6-PadA)") (class "Default")
      (node (ref "LED6") (pin "A") (pinfunction "A_A") (pintype "passive"))
      (node (ref "R11") (pin "1") (pinfunction "1_1") (pintype "passive"))
    )
    (net (code "193") (name "Net-(LED7-PadA)") (class "Default")
      (node (ref "LED7") (pin "A") (pinfunction "A_A") (pintype "passive"))
      (node (ref "R13") (pin "1") (pinfunction "1_1") (pintype "passive"))
    )
    (net (code "194") (name "Net-(LED8-PadA)") (class "Default")
      (node (ref "LED8") (pin "A") (pinfunction "A_A") (pintype "passive"))
      (node (ref "R15") (pin "1") (pinfunction "1_1") (pintype "passive"))
    )
    (net (code "195") (name "Net-(LED9-PadA)") (class "Default")
      (node (ref "LED9") (pin "A") (pinfunction "A_A") (pintype "passive"))
      (node (ref "R17") (pin "1") (pinfunction "1_1") (pintype "passive"))
    )
    (net (code "196") (name "Net-(LED10-PadA)") (class "Default")
      (node (ref "LED10") (pin "A") (pinfunction "A_A") (pintype "passive"))
      (node (ref "R19") (pin "1") (pinfunction "1_1") (pintype "passive"))
    )
    (net (code "197") (name "Net-(LED11-PadA)") (class "Default")
      (node (ref "LED11") (pin "A") (pinfunction "A_A") (pintype "passive"))
      (node (ref "R21") (pin "1") (pinfunction "1_1") (pintype "passive"))
    )
    (net (code "198") (name "Net-(LED14-PadA)") (class "Default")
      (node (ref "LED14") (pin "A") (pinfunction "A_A") (pintype "passive"))
      (node (ref "R27") (pin "1") (pinfunction "1_1") (pintype "passive"))
    )
    (net (code "199") (name "Net-(LED15-PadA)") (class "Default")
      (node (ref "LED15") (pin "A") (pinfunction "A_A") (pintype "passive"))
      (node (ref "R29") (pin "1") (pinfunction "1_1") (pintype "passive"))
    )
    (net (code "200") (name "Net-(LED18-PadA)") (class "Default")
      (node (ref "LED18") (pin "A") (pinfunction "A_A") (pintype "passive"))
      (node (ref "R35") (pin "1") (pinfunction "1_1") (pintype "passive"))
    )
    (net (code "201") (name "Net-(LED19-PadA)") (class "Default")
      (node (ref "LED19") (pin "A") (pinfunction "A_A") (pintype "passive"))
      (node (ref "R37") (pin "1") (pinfunction "1_1") (pintype "passive"))
    )
    (net (code "202") (name "Net-(LED20-PadA)") (class "Default")
      (node (ref "LED20") (pin "A") (pinfunction "A_A") (pintype "passive"))
      (node (ref "R39") (pin "1") (pinfunction "1_1") (pintype "passive"))
    )
    (net (code "203") (name "Net-(LED21-PadA)") (class "Default")
      (node (ref "LED21") (pin "A") (pinfunction "A_A") (pintype "passive"))
      (node (ref "R41") (pin "1") (pinfunction "1_1") (pintype "passive"))
    )
    (net (code "204") (name "Net-(LED22-PadA)") (class "Default")
      (node (ref "LED22") (pin "A") (pinfunction "A_A") (pintype "passive"))
      (node (ref "R43") (pin "1") (pinfunction "1_1") (pintype "passive"))
    )
    (net (code "205") (name "Net-(LED23-PadA)") (class "Default")
      (node (ref "LED23") (pin "A") (pinfunction "A_A") (pintype "passive"))
      (node (ref "R45") (pin "1") (pinfunction "1_1") (pintype "passive"))
    )
    (net (code "206") (name "Net-(LED24-PadA)") (class "Default")
      (node (ref "LED24") (pin "A") (pinfunction "A_A") (pintype "passive"))
      (node (ref "R47") (pin "1") (pinfunction "1_1") (pintype "passive"))
    )
    (net (code "207") (name "Net-(LED27-PadA)") (class "Default")
      (node (ref "LED27") (pin "A") (pinfunction "A_A") (pintype "passive"))
      (node (ref "R53") (pin "1") (pinfunction "1_1") (pintype "passive"))
    )
    (net (code "208") (name "Net-(LED28-PadA)") (class "Default")
      (node (ref "LED28") (pin "A") (pinfunction "A_A") (pintype "passive"))
      (node (ref "R55") (pin "1") (pinfunction "1_1") (pintype "passive"))
    )
    (net (code "209") (name "Net-(LED29-PadA)") (class "Default")
      (node (ref "LED29") (pin "A") (pinfunction "A_A") (pintype "passive"))
      (node (ref "R57") (pin "1") (pinfunction "1_1") (pintype "passive"))
    )
    (net (code "210") (name "Net-(LED30-PadA)") (class "Default")
      (node (ref "LED30") (pin "A") (pinfunction "A_A") (pintype "passive"))
      (node (ref "R59") (pin "1") (pinfunction "1_1") (pintype "passive"))
    )
    (net (code "211") (name "Net-(LED31-PadA)") (class "Default")
      (node (ref "LED31") (pin "A") (pinfunction "A_A") (pintype "passive"))
      (node (ref "R61") (pin "1") (pinfunction "1_1") (pintype "passive"))
    )
    (net (code "212") (name "Net-(LED32-PadA)") (class "Default")
      (node (ref "LED32") (pin "A") (pinfunction "A_A") (pintype "passive"))
      (node (ref "R63") (pin "1") (pinfunction "1_1") (pintype "passive"))
    )
    (net (code "213") (name "Net-(LED33-PadA)") (class "Default")
      (node (ref "LED33") (pin "A") (pinfunction "A_A") (pintype "passive"))
      (node (ref "R65") (pin "1") (pinfunction "1_1") (pintype "passive"))
    )
    (net (code "214") (name "Net-(LED34-PadA)") (class "Default")
      (node (ref "LED34") (pin "A") (pinfunction "A_A") (pintype "passive"))
      (node (ref "R67") (pin "1") (pinfunction "1_1") (pintype "passive"))
    )
    (net (code "215") (name "Net-(LED35-PadA)") (class "Default")
      (node (ref "LED35") (pin "A") (pinfunction "A_A") (pintype "passive"))
      (node (ref "R69") (pin "1") (pinfunction "1_1") (pintype "passive"))
    )
    (net (code "216") (name "Net-(LED36-PadA)") (class "Default")
      (node (ref "LED36") (pin "A") (pinfunction "A_A") (pintype "passive"))
      (node (ref "R71") (pin "1") (pinfunction "1_1") (pintype "passive"))
    )
    (net (code "217") (name "Net-(LED37-PadA)") (class "Default")
      (node (ref "LED37") (pin "A") (pinfunction "A_A") (pintype "passive"))
      (node (ref "R73") (pin "1") (pinfunction "1_1") (pintype "passive"))
    )
    (net (code "218") (name "Net-(LED38-PadA)") (class "Default")
      (node (ref "LED38") (pin "A") (pinfunction "A_A") (pintype "passive"))
      (node (ref "R75") (pin "1") (pinfunction "1_1") (pintype "passive"))
    )
    (net (code "219") (name "Net-(LED39-PadA)") (class "Default")
      (node (ref "LED39") (pin "A") (pinfunction "A_A") (pintype "passive"))
      (node (ref "R77") (pin "1") (pinfunction "1_1") (pintype "passive"))
    )
    (net (code "220") (name "Net-(LED40-PadA)") (class "Default")
      (node (ref "LED40") (pin "A") (pinfunction "A_A") (pintype "passive"))
      (node (ref "R79") (pin "1") (pinfunction "1_1") (pintype "passive"))
    )
    (net (code "221") (name "Net-(LED41-PadA)") (class "Default")
      (node (ref "LED41") (pin "A") (pinfunction "A_A") (pintype "passive"))
      (node (ref "R81") (pin "1") (pinfunction "1_1") (pintype "passive"))
    )
    (net (code "222") (name "Net-(LED42-PadA)") (class "Default")
      (node (ref "LED42") (pin "A") (pinfunction "A_A") (pintype "passive"))
      (node (ref "R83") (pin "1") (pinfunction "1_1") (pintype "passive"))
    )
    (net (code "223") (name "Net-(LED43-PadA)") (class "Default")
      (node (ref "LED43") (pin "A") (pinfunction "A_A") (pintype "passive"))
      (node (ref "R85") (pin "1") (pinfunction "1_1") (pintype "passive"))
    )
    (net (code "224") (name "Net-(LED44-PadA)") (class "Default")
      (node (ref "LED44") (pin "A") (pinfunction "A_A") (pintype "passive"))
      (node (ref "R87") (pin "1") (pinfunction "1_1") (pintype "passive"))
    )
    (net (code "225") (name "Net-(LED45-PadA)") (class "Default")
      (node (ref "LED45") (pin "A") (pinfunction "A_A") (pintype "passive"))
      (node (ref "R89") (pin "1") (pinfunction "1_1") (pintype "passive"))
    )
    (net (code "226") (name "Net-(LED46-PadA)") (class "Default")
      (node (ref "LED46") (pin "A") (pinfunction "A_A") (pintype "passive"))
      (node (ref "R91") (pin "1") (pinfunction "1_1") (pintype "passive"))
    )
    (net (code "227") (name "Net-(LED47-PadA)") (class "Default")
      (node (ref "LED47") (pin "A") (pinfunction "A_A") (pintype "passive"))
      (node (ref "R93") (pin "1") (pinfunction "1_1") (pintype "passive"))
    )
    (net (code "228") (name "Net-(LED48-PadA)") (class "Default")
      (node (ref "LED48") (pin "A") (pinfunction "A_A") (pintype "passive"))
      (node (ref "R95") (pin "1") (pinfunction "1_1") (pintype "passive"))
    )
    (net (code "229") (name "Net-(LED49-PadA)") (class "Default")
      (node (ref "LED49") (pin "A") (pinfunction "A_A") (pintype "passive"))
      (node (ref "R97") (pin "1") (pinfunction "1_1") (pintype "passive"))
    )
    (net (code "230") (name "Net-(LED50-PadA)") (class "Default")
      (node (ref "LED50") (pin "A") (pinfunction "A_A") (pintype "passive"))
      (node (ref "R99") (pin "1") (pinfunction "1_1") (pintype "passive"))
    )
    (net (code "231") (name "Net-(T1-B)") (class "Default")
      (node (ref "R7") (pin "1") (pinfunction "1_1") (pintype "passive"))
      (node (ref "T1") (pin "2") (pinfunction "B_2") (pintype "passive"))
    )
    (net (code "232") (name "Net-(T2-B)") (class "Default")
      (node (ref "R8") (pin "1") (pinfunction "1_1") (pintype "passive"))
      (node (ref "T2") (pin "2") (pinfunction "B_2") (pintype "passive"))
    )
    (net (code "233") (name "Net-(T3-B)") (class "Default")
      (node (ref "R10") (pin "1") (pinfunction "1_1") (pintype "passive"))
      (node (ref "T3") (pin "2") (pinfunction "B_2") (pintype "passive"))
    )
    (net (code "234") (name "Net-(T4-B)") (class "Default")
      (node (ref "R12") (pin "1") (pinfunction "1_1") (pintype "passive"))
      (node (ref "T4") (pin "2") (pinfunction "B_2") (pintype "passive"))
    )
    (net (code "235") (name "Net-(T5-B)") (class "Default")
      (node (ref "R14") (pin "1") (pinfunction "1_1") (pintype "passive"))
      (node (ref "T5") (pin "2") (pinfunction "B_2") (pintype "passive"))
    )
    (net (code "236") (name "Net-(T6-B)") (class "Default")
      (node (ref "R16") (pin "1") (pinfunction "1_1") (pintype "passive"))
      (node (ref "T6") (pin "2") (pinfunction "B_2") (pintype "passive"))
    )
    (net (code "237") (name "Net-(T7-B)") (class "Default")
      (node (ref "R18") (pin "1") (pinfunction "1_1") (pintype "passive"))
      (node (ref "T7") (pin "2") (pinfunction "B_2") (pintype "passive"))
    )
    (net (code "238") (name "Net-(T8-B)") (class "Default")
      (node (ref "R20") (pin "1") (pinfunction "1_1") (pintype "passive"))
      (node (ref "T8") (pin "2") (pinfunction "B_2") (pintype "passive"))
    )
    (net (code "239") (name "Net-(T9-B)") (class "Default")
      (node (ref "R22") (pin "1") (pinfunction "1_1") (pintype "passive"))
      (node (ref "T9") (pin "2") (pinfunction "B_2") (pintype "passive"))
    )
    (net (code "240") (name "Net-(T12-B)") (class "Default")
      (node (ref "R28") (pin "1") (pinfunction "1_1") (pintype "passive"))
      (node (ref "T12") (pin "2") (pinfunction "B_2") (pintype "passive"))
    )
    (net (code "241") (name "Net-(T13-B)") (class "Default")
      (node (ref "R30") (pin "1") (pinfunction "1_1") (pintype "passive"))
      (node (ref "T13") (pin "2") (pinfunction "B_2") (pintype "passive"))
    )
    (net (code "242") (name "Net-(T16-B)") (class "Default")
      (node (ref "R36") (pin "1") (pinfunction "1_1") (pintype "passive"))
      (node (ref "T16") (pin "2") (pinfunction "B_2") (pintype "passive"))
    )
    (net (code "243") (name "Net-(T17-B)") (class "Default")
      (node (ref "R38") (pin "1") (pinfunction "1_1") (pintype "passive"))
      (node (ref "T17") (pin "2") (pinfunction "B_2") (pintype "passive"))
    )
    (net (code "244") (name "Net-(T18-B)") (class "Default")
      (node (ref "R40") (pin "1") (pinfunction "1_1") (pintype "passive"))
      (node (ref "T18") (pin "2") (pinfunction "B_2") (pintype "passive"))
    )
    (net (code "245") (name "Net-(T19-B)") (class "Default")
      (node (ref "R42") (pin "1") (pinfunction "1_1") (pintype "passive"))
      (node (ref "T19") (pin "2") (pinfunction "B_2") (pintype "passive"))
    )
    (net (code "246") (name "Net-(T20-B)") (class "Default")
      (node (ref "R44") (pin "1") (pinfunction "1_1") (pintype "passive"))
      (node (ref "T20") (pin "2") (pinfunction "B_2") (pintype "passive"))
    )
    (net (code "247") (name "Net-(T21-B)") (class "Default")
      (node (ref "R46") (pin "1") (pinfunction "1_1") (pintype "passive"))
      (node (ref "T21") (pin "2") (pinfunction "B_2") (pintype "passive"))
    )
    (net (code "248") (name "Net-(T22-B)") (class "Default")
      (node (ref "R48") (pin "1") (pinfunction "1_1") (pintype "passive"))
      (node (ref "T22") (pin "2") (pinfunction "B_2") (pintype "passive"))
    )
    (net (code "249") (name "Net-(T25-B)") (class "Default")
      (node (ref "R54") (pin "1") (pinfunction "1_1") (pintype "passive"))
      (node (ref "T25") (pin "2") (pinfunction "B_2") (pintype "passive"))
    )
    (net (code "250") (name "Net-(T26-B)") (class "Default")
      (node (ref "R56") (pin "1") (pinfunction "1_1") (pintype "passive"))
      (node (ref "T26") (pin "2") (pinfunction "B_2") (pintype "passive"))
    )
    (net (code "251") (name "Net-(T27-B)") (class "Default")
      (node (ref "R58") (pin "1") (pinfunction "1_1") (pintype "passive"))
      (node (ref "T27") (pin "2") (pinfunction "B_2") (pintype "passive"))
    )
    (net (code "252") (name "Net-(T28-B)") (class "Default")
      (node (ref "R60") (pin "1") (pinfunction "1_1") (pintype "passive"))
      (node (ref "T28") (pin "2") (pinfunction "B_2") (pintype "passive"))
    )
    (net (code "253") (name "Net-(T29-B)") (class "Default")
      (node (ref "R62") (pin "1") (pinfunction "1_1") (pintype "passive"))
      (node (ref "T29") (pin "2") (pinfunction "B_2") (pintype "passive"))
    )
    (net (code "254") (name "Net-(T30-B)") (class "Default")
      (node (ref "R64") (pin "1") (pinfunction "1_1") (pintype "passive"))
      (node (ref "T30") (pin "2") (pinfunction "B_2") (pintype "passive"))
    )
    (net (code "255") (name "Net-(T31-B)") (class "Default")
      (node (ref "R66") (pin "1") (pinfunction "1_1") (pintype "passive"))
      (node (ref "T31") (pin "2") (pinfunction "B_2") (pintype "passive"))
    )
    (net (code "256") (name "Net-(T32-B)") (class "Default")
      (node (ref "R68") (pin "1") (pinfunction "1_1") (pintype "passive"))
      (node (ref "T32") (pin "2") (pinfunction "B_2") (pintype "passive"))
    )
    (net (code "257") (name "Net-(T33-B)") (class "Default")
      (node (ref "R70") (pin "1") (pinfunction "1_1") (pintype "passive"))
      (node (ref "T33") (pin "2") (pinfunction "B_2") (pintype "passive"))
    )
    (net (code "258") (name "Net-(T34-B)") (class "Default")
      (node (ref "R72") (pin "1") (pinfunction "1_1") (pintype "passive"))
      (node (ref "T34") (pin "2") (pinfunction "B_2") (pintype "passive"))
    )
    (net (code "259") (name "Net-(T35-B)") (class "Default")
      (node (ref "R74") (pin "1") (pinfunction "1_1") (pintype "passive"))
      (node (ref "T35") (pin "2") (pinfunction "B_2") (pintype "passive"))
    )
    (net (code "260") (name "Net-(T36-B)") (class "Default")
      (node (ref "R76") (pin "1") (pinfunction "1_1") (pintype "passive"))
      (node (ref "T36") (pin "2") (pinfunction "B_2") (pintype "passive"))
    )
    (net (code "261") (name "Net-(T37-B)") (class "Default")
      (node (ref "R78") (pin "1") (pinfunction "1_1") (pintype "passive"))
      (node (ref "T37") (pin "2") (pinfunction "B_2") (pintype "passive"))
    )
    (net (code "262") (name "Net-(T38-B)") (class "Default")
      (node (ref "R80") (pin "1") (pinfunction "1_1") (pintype "passive"))
      (node (ref "T38") (pin "2") (pinfunction "B_2") (pintype "passive"))
    )
    (net (code "263") (name "Net-(T39-B)") (class "Default")
      (node (ref "R82") (pin "1") (pinfunction "1_1") (pintype "passive"))
      (node (ref "T39") (pin "2") (pinfunction "B_2") (pintype "passive"))
    )
    (net (code "264") (name "Net-(T40-B)") (class "Default")
      (node (ref "R84") (pin "1") (pinfunction "1_1") (pintype "passive"))
      (node (ref "T40") (pin "2") (pinfunction "B_2") (pintype "passive"))
    )
    (net (code "265") (name "Net-(T41-B)") (class "Default")
      (node (ref "R86") (pin "1") (pinfunction "1_1") (pintype "passive"))
      (node (ref "T41") (pin "2") (pinfunction "B_2") (pintype "passive"))
    )
    (net (code "266") (name "Net-(T42-B)") (class "Default")
      (node (ref "R88") (pin "1") (pinfunction "1_1") (pintype "passive"))
      (node (ref "T42") (pin "2") (pinfunction "B_2") (pintype "passive"))
    )
    (net (code "267") (name "Net-(T43-B)") (class "Default")
      (node (ref "R90") (pin "1") (pinfunction "1_1") (pintype "passive"))
      (node (ref "T43") (pin "2") (pinfunction "B_2") (pintype "passive"))
    )
    (net (code "268") (name "Net-(T44-B)") (class "Default")
      (node (ref "R92") (pin "1") (pinfunction "1_1") (pintype "passive"))
      (node (ref "T44") (pin "2") (pinfunction "B_2") (pintype "passive"))
    )
    (net (code "269") (name "Net-(T45-B)") (class "Default")
      (node (ref "R94") (pin "1") (pinfunction "1_1") (pintype "passive"))
      (node (ref "T45") (pin "2") (pinfunction "B_2") (pintype "passive"))
    )
    (net (code "270") (name "Net-(T46-B)") (class "Default")
      (node (ref "R96") (pin "1") (pinfunction "1_1") (pintype "passive"))
      (node (ref "T46") (pin "2") (pinfunction "B_2") (pintype "passive"))
    )
    (net (code "271") (name "Net-(T47-B)") (class "Default")
      (node (ref "R98") (pin "1") (pinfunction "1_1") (pintype "passive"))
      (node (ref "T47") (pin "2") (pinfunction "B_2") (pintype "passive"))
    )
    (net (code "272") (name "Net-(T48-B)") (class "Default")
      (node (ref "R100") (pin "1") (pinfunction "1_1") (pintype "passive"))
      (node (ref "T48") (pin "2") (pinfunction "B_2") (pintype "passive"))
    )
    (net (code "273") (name "Net-(U1-BOOT0)") (class "Default")
      (node (ref "R1") (pin "2") (pinfunction "2_2") (pintype "passive"))
      (node (ref "U1") (pin "60") (pinfunction "BOOT0_60") (pintype "input"))
    )
    (net (code "274") (name "Net-(U1-PD0_OSC_IN)") (class "Default")
      (node (ref "C6") (pin "1") (pinfunction "1_1") (pintype "passive"))
      (node (ref "Q1") (pin "2") (pinfunction "2_2") (pintype "passive"))
      (node (ref "U1") (pin "5") (pinfunction "PD0_OSC_IN_5") (pintype "bidirectional"))
    )
    (net (code "275") (name "Net-(U1-PD1_OSC_OUT)") (class "Default")
      (node (ref "C7") (pin "1") (pinfunction "1_1") (pintype "passive"))
      (node (ref "Q1") (pin "1") (pinfunction "1_1") (pintype "passive"))
      (node (ref "U1") (pin "6") (pinfunction "PD1_OSC_OUT_6") (pintype "bidirectional"))
    )
    (net (code "276") (name "Net-(U1-PD2)") (class "Default")
      (node (ref "LED3") (pin "C") (pinfunction "C_C") (pintype "passive"))
      (node (ref "U1") (pin "54") (pinfunction "PD2_54") (pintype "bidirectional"))
    )
    (net (code "277") (name "Net-(U1-VDDA)") (class "Default")
      (node (ref "R23") (pin "1") (pinfunction "1_1") (pintype "passive"))
      (node (ref "U1") (pin "13") (pinfunction "VDDA_13") (pintype "power_in"))
    )
    (net (code "278") (name "Net-(U1-VSSA)") (class "Default")
      (node (ref "R24") (pin "1") (pinfunction "1_1") (pintype "passive"))
      (node (ref "U1") (pin "12") (pinfunction "VSSA_12") (pintype "passive"))
    )
    (net (code "279") (name "unconnected-(K1C-O-PadO2)") (class "Default")
      (node (ref "K1") (pin "O2") (pinfunction "O_O2") (pintype "passive"))
    )
    (net (code "280") (name "unconnected-(K2C-O-PadO2)") (class "Default")
      (node (ref "K2") (pin "O2") (pinfunction "O_O2") (pintype "passive"))
    )
    (net (code "281") (name "unconnected-(K3C-O-PadO2)") (class "Default")
      (node (ref "K3") (pin "O2") (pinfunction "O_O2") (pintype "passive"))
    )
    (net (code "282") (name "unconnected-(K4C-O-PadO2)") (class "Default")
      (node (ref "K4") (pin "O2") (pinfunction "O_O2") (pintype "passive"))
    )
    (net (code "283") (name "unconnected-(K5C-O-PadO2)") (class "Default")
      (node (ref "K5") (pin "O2") (pinfunction "O_O2") (pintype "passive"))
    )
    (net (code "284") (name "unconnected-(K6C-O-PadO2)") (class "Default")
      (node (ref "K6") (pin "O2") (pinfunction "O_O2") (pintype "passive"))
    )
    (net (code "285") (name "unconnected-(K7C-O-PadO2)") (class "Default")
      (node (ref "K7") (pin "O2") (pinfunction "O_O2") (pintype "passive"))
    )
    (net (code "286") (name "unconnected-(K8C-O-PadO2)") (class "Default")
      (node (ref "K8") (pin "O2") (pinfunction "O_O2") (pintype "passive"))
    )
    (net (code "287") (name "unconnected-(K9C-O-PadO2)") (class "Default")
      (node (ref "K9") (pin "O2") (pinfunction "O_O2") (pintype "passive"))
    )
    (net (code "288") (name "unconnected-(K12C-O-PadO2)") (class "Default")
      (node (ref "K12") (pin "O2") (pinfunction "O_O2") (pintype "passive"))
    )
    (net (code "289") (name "unconnected-(K13C-O-PadO2)") (class "Default")
      (node (ref "K13") (pin "O2") (pinfunction "O_O2") (pintype "passive"))
    )
    (net (code "290") (name "unconnected-(K16C-O-PadO2)") (class "Default")
      (node (ref "K16") (pin "O2") (pinfunction "O_O2") (pintype "passive"))
    )
    (net (code "291") (name "unconnected-(K17C-O-PadO2)") (class "Default")
      (node (ref "K17") (pin "O2") (pinfunction "O_O2") (pintype "passive"))
    )
    (net (code "292") (name "unconnected-(K18C-O-PadO2)") (class "Default")
      (node (ref "K18") (pin "O2") (pinfunction "O_O2") (pintype "passive"))
    )
    (net (code "293") (name "unconnected-(K19C-O-PadO2)") (class "Default")
      (node (ref "K19") (pin "O2") (pinfunction "O_O2") (pintype "passive"))
    )
    (net (code "294") (name "unconnected-(K20C-O-PadO2)") (class "Default")
      (node (ref "K20") (pin "O2") (pinfunction "O_O2") (pintype "passive"))
    )
    (net (code "295") (name "unconnected-(K21C-O-PadO2)") (class "Default")
      (node (ref "K21") (pin "O2") (pinfunction "O_O2") (pintype "passive"))
    )
    (net (code "296") (name "unconnected-(K22C-O-PadO2)") (class "Default")
      (node (ref "K22") (pin "O2") (pinfunction "O_O2") (pintype "passive"))
    )
    (net (code "297") (name "unconnected-(K25C-O-PadO2)") (class "Default")
      (node (ref "K25") (pin "O2") (pinfunction "O_O2") (pintype "passive"))
    )
    (net (code "298") (name "unconnected-(K26C-O-PadO2)") (class "Default")
      (node (ref "K26") (pin "O2") (pinfunction "O_O2") (pintype "passive"))
    )
    (net (code "299") (name "unconnected-(K27C-O-PadO2)") (class "Default")
      (node (ref "K27") (pin "O2") (pinfunction "O_O2") (pintype "passive"))
    )
    (net (code "300") (name "unconnected-(K28C-O-PadO2)") (class "Default")
      (node (ref "K28") (pin "O2") (pinfunction "O_O2") (pintype "passive"))
    )
    (net (code "301") (name "unconnected-(K29C-O-PadO2)") (class "Default")
      (node (ref "K29") (pin "O2") (pinfunction "O_O2") (pintype "passive"))
    )
    (net (code "302") (name "unconnected-(K30C-O-PadO2)") (class "Default")
      (node (ref "K30") (pin "O2") (pinfunction "O_O2") (pintype "passive"))
    )
    (net (code "303") (name "unconnected-(K31C-O-PadO2)") (class "Default")
      (node (ref "K31") (pin "O2") (pinfunction "O_O2") (pintype "passive"))
    )
    (net (code "304") (name "unconnected-(K32C-O-PadO2)") (class "Default")
      (node (ref "K32") (pin "O2") (pinfunction "O_O2") (pintype "passive"))
    )
    (net (code "305") (name "unconnected-(K33C-O-PadO2)") (class "Default")
      (node (ref "K33") (pin "O2") (pinfunction "O_O2") (pintype "passive"))
    )
    (net (code "306") (name "unconnected-(K34C-O-PadO2)") (class "Default")
      (node (ref "K34") (pin "O2") (pinfunction "O_O2") (pintype "passive"))
    )
    (net (code "307") (name "unconnected-(K35C-O-PadO2)") (class "Default")
      (node (ref "K35") (pin "O2") (pinfunction "O_O2") (pintype "passive"))
    )
    (net (code "308") (name "unconnected-(K36C-O-PadO2)") (class "Default")
      (node (ref "K36") (pin "O2") (pinfunction "O_O2") (pintype "passive"))
    )
    (net (code "309") (name "unconnected-(K37C-O-PadO2)") (class "Default")
      (node (ref "K37") (pin "O2") (pinfunction "O_O2") (pintype "passive"))
    )
    (net (code "310") (name "unconnected-(K38C-O-PadO2)") (class "Default")
      (node (ref "K38") (pin "O2") (pinfunction "O_O2") (pintype "passive"))
    )
    (net (code "311") (name "unconnected-(K39C-O-PadO2)") (class "Default")
      (node (ref "K39") (pin "O2") (pinfunction "O_O2") (pintype "passive"))
    )
    (net (code "312") (name "unconnected-(K40C-O-PadO2)") (class "Default")
      (node (ref "K40") (pin "O2") (pinfunction "O_O2") (pintype "passive"))
    )
    (net (code "313") (name "unconnected-(K41C-O-PadO2)") (class "Default")
      (node (ref "K41") (pin "O2") (pinfunction "O_O2") (pintype "passive"))
    )
    (net (code "314") (name "unconnected-(K42C-O-PadO2)") (class "Default")
      (node (ref "K42") (pin "O2") (pinfunction "O_O2") (pintype "passive"))
    )
    (net (code "315") (name "unconnected-(K43C-O-PadO2)") (class "Default")
      (node (ref "K43") (pin "O2") (pinfunction "O_O2") (pintype "passive"))
    )
    (net (code "316") (name "unconnected-(K44C-O-PadO2)") (class "Default")
      (node (ref "K44") (pin "O2") (pinfunction "O_O2") (pintype "passive"))
    )
    (net (code "317") (name "unconnected-(K45C-O-PadO2)") (class "Default")
      (node (ref "K45") (pin "O2") (pinfunction "O_O2") (pintype "passive"))
    )
    (net (code "318") (name "unconnected-(K46C-O-PadO2)") (class "Default")
      (node (ref "K46") (pin "O2") (pinfunction "O_O2") (pintype "passive"))
    )
    (net (code "319") (name "unconnected-(K47C-O-PadO2)") (class "Default")
      (node (ref "K47") (pin "O2") (pinfunction "O_O2") (pintype "passive"))
    )
    (net (code "320") (name "unconnected-(K48C-O-PadO2)") (class "Default")
      (node (ref "K48") (pin "O2") (pinfunction "O_O2") (pintype "passive"))
    )
    (net (code "321") (name "unconnected-(S2-Pad1)") (class "Default")
      (node (ref "S2") (pin "1") (pinfunction "1_1") (pintype "passive"))
    )
    (net (code "322") (name "unconnected-(S2-Pad3)") (class "Default")
      (node (ref "S2") (pin "3") (pinfunction "3_3") (pintype "passive"))
    )
  )
)
